# shimboard_revC_V5.net
KiCad netlist of a schematic drawn in EAGLE
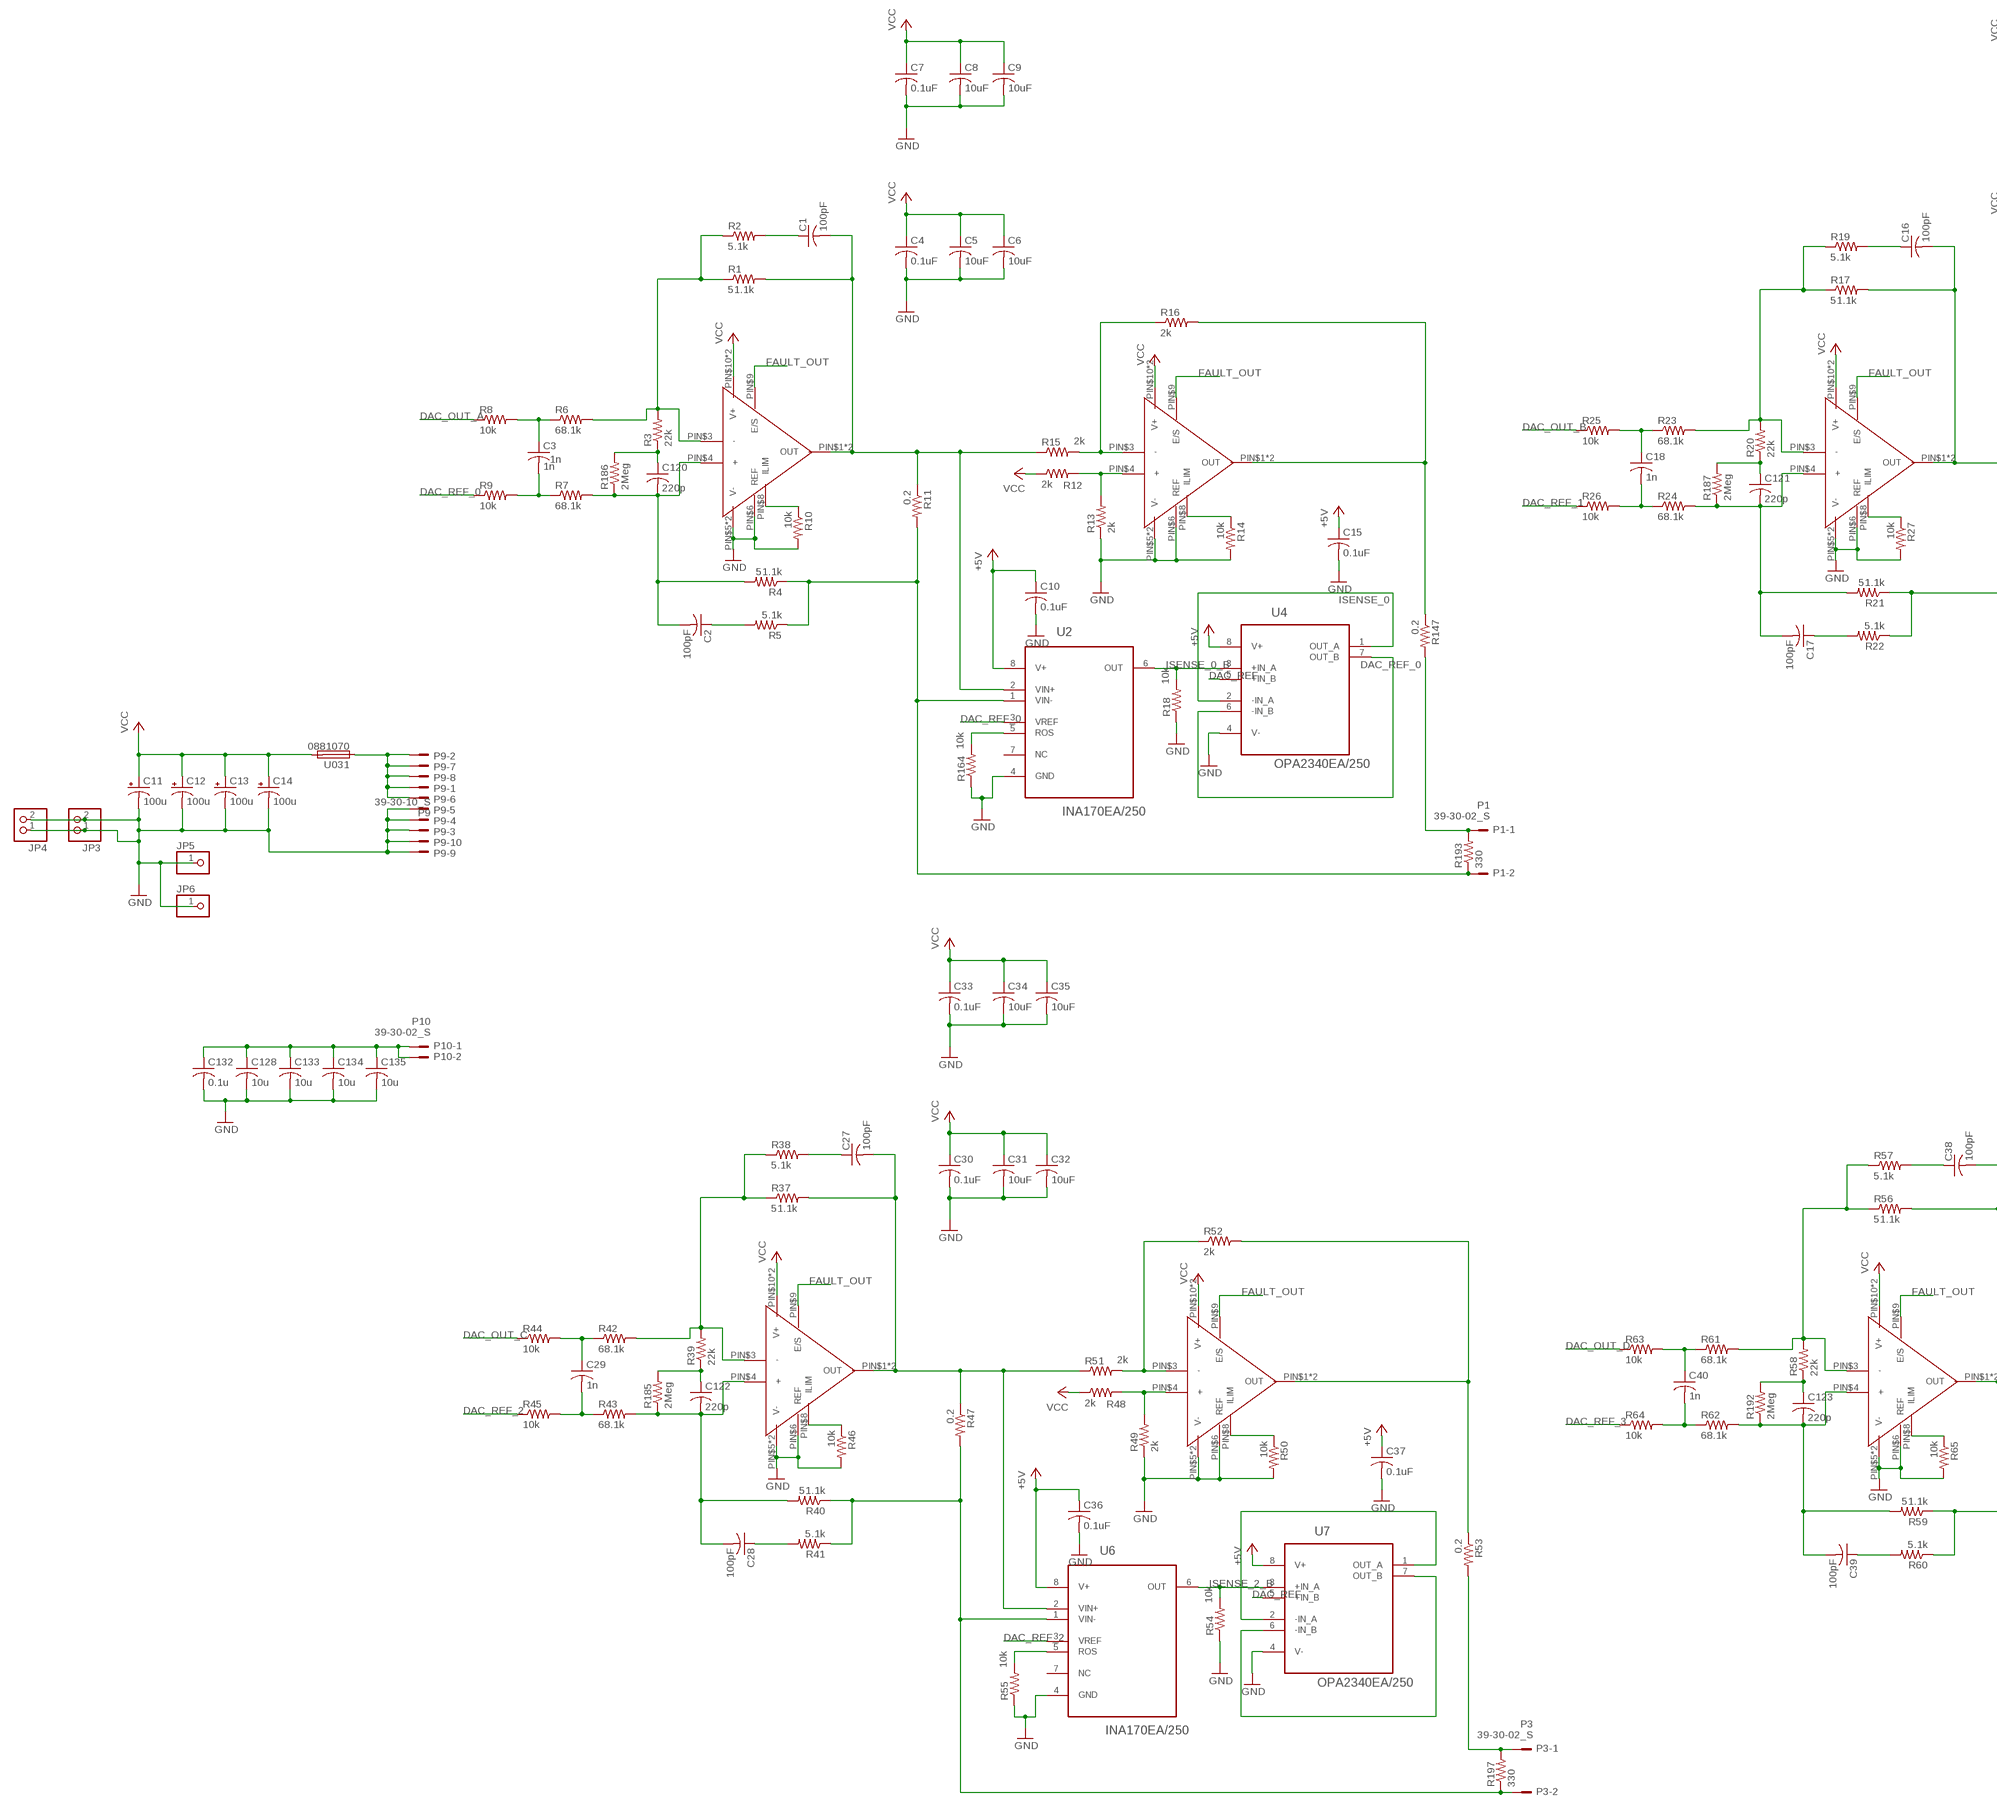
[diagram p0: schematic, sheet 1, part 1 of 3]
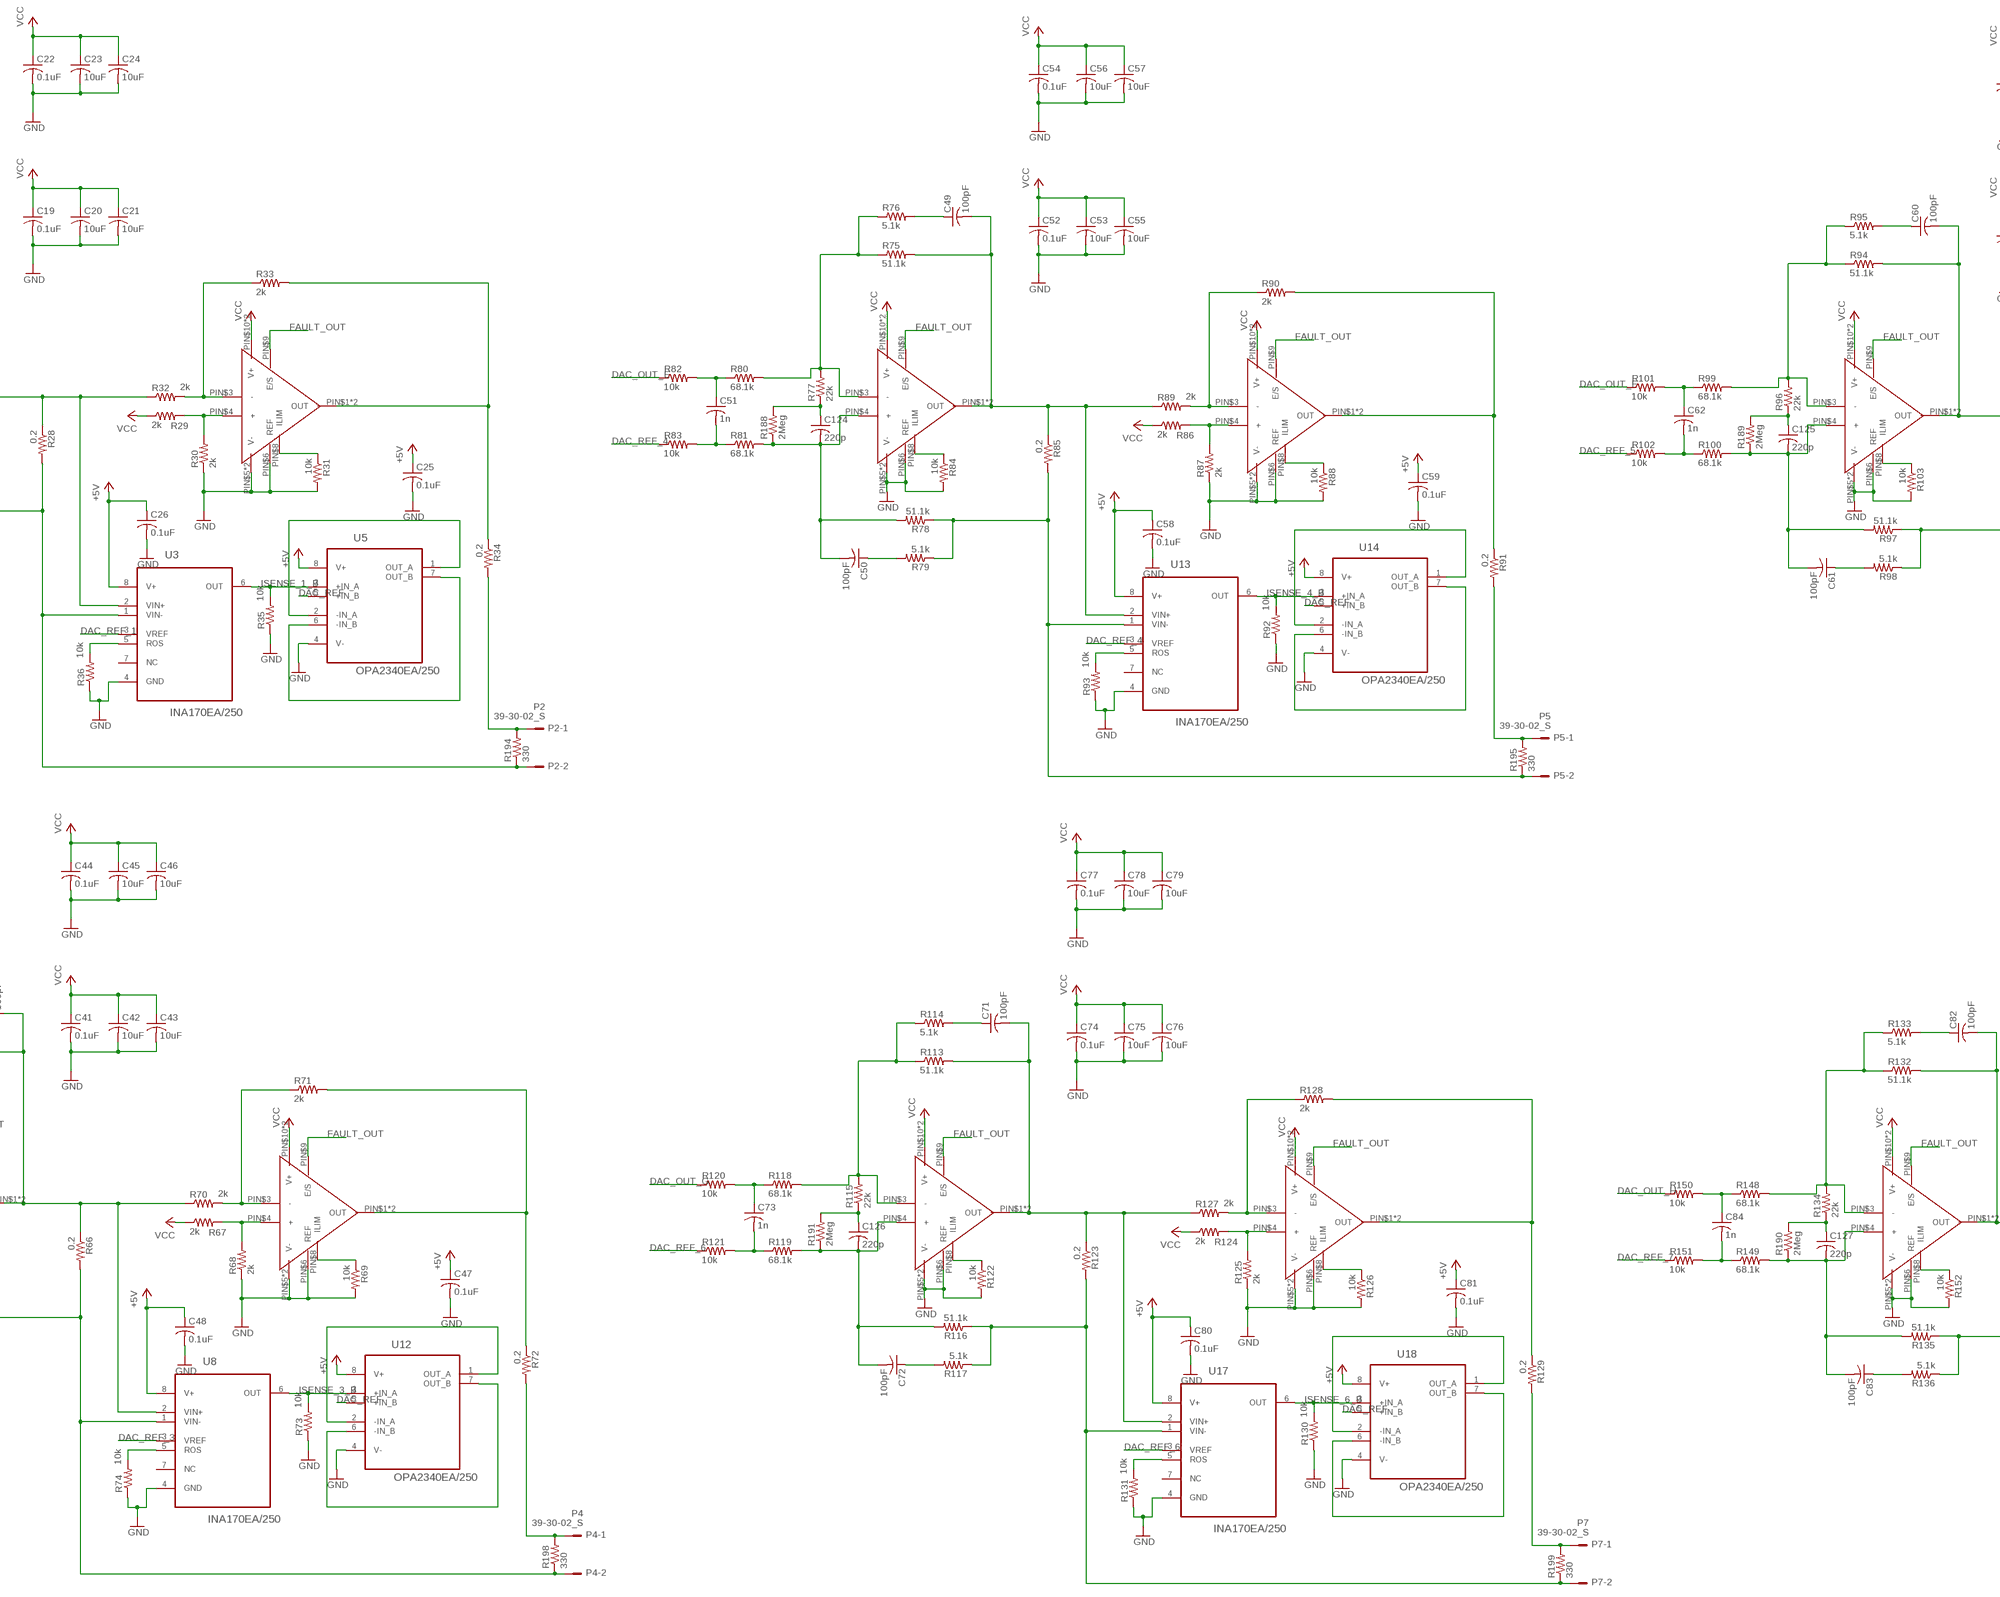
[diagram p1: schematic, sheet 1, part 2 of 3]
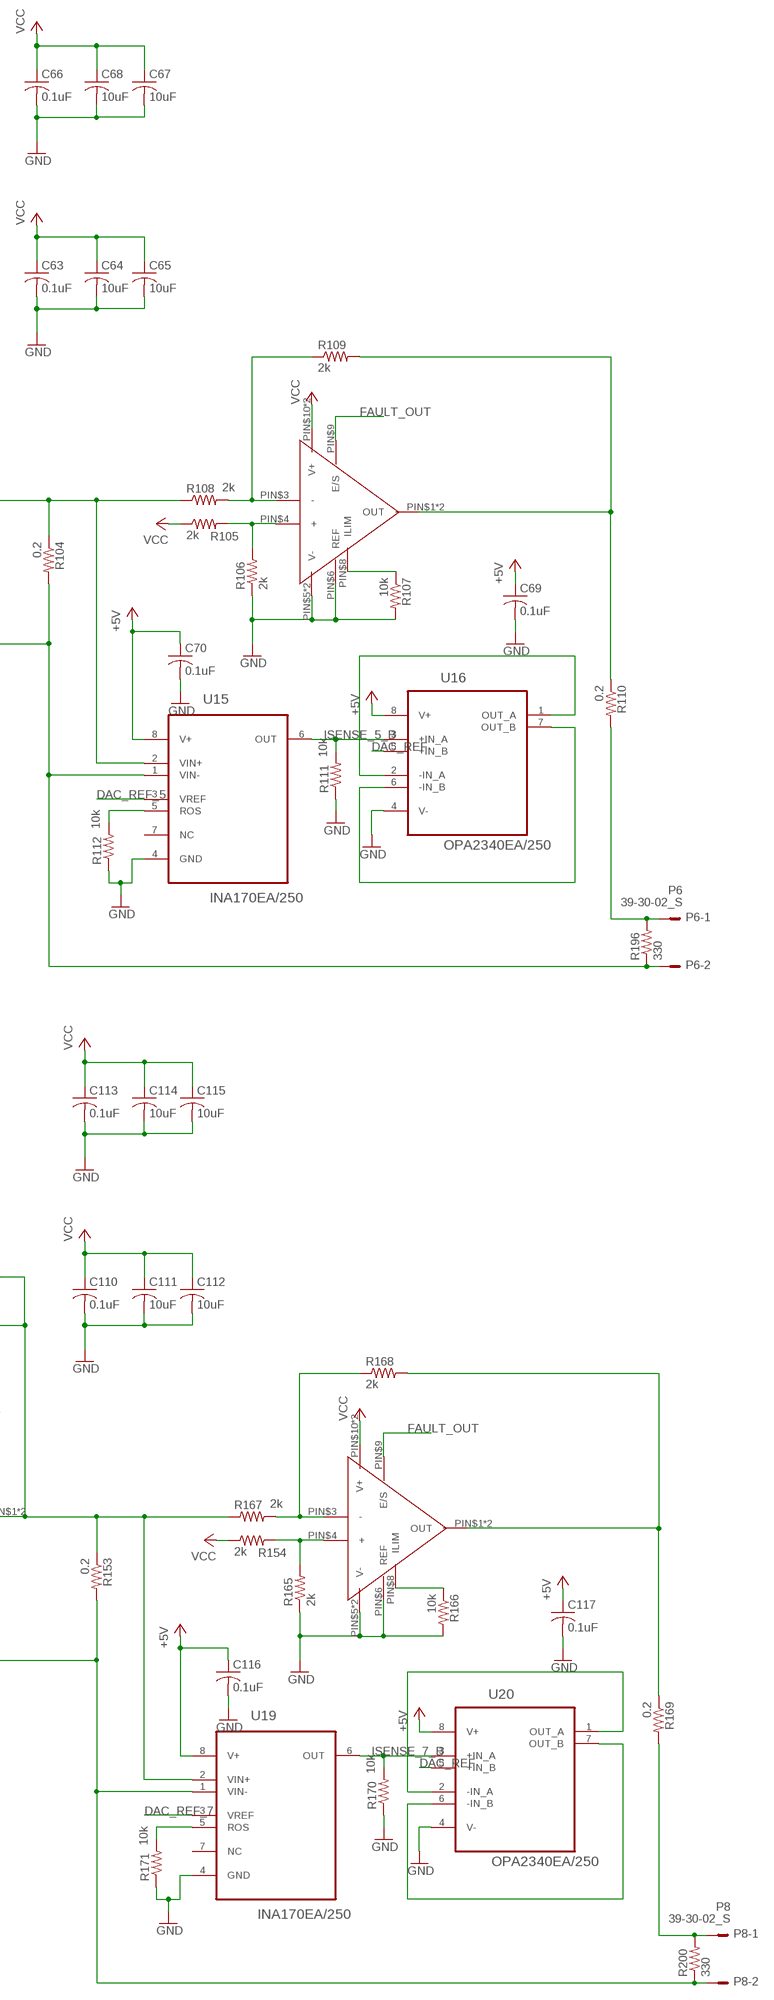
[diagram p2: schematic, sheet 1, part 3 of 3]
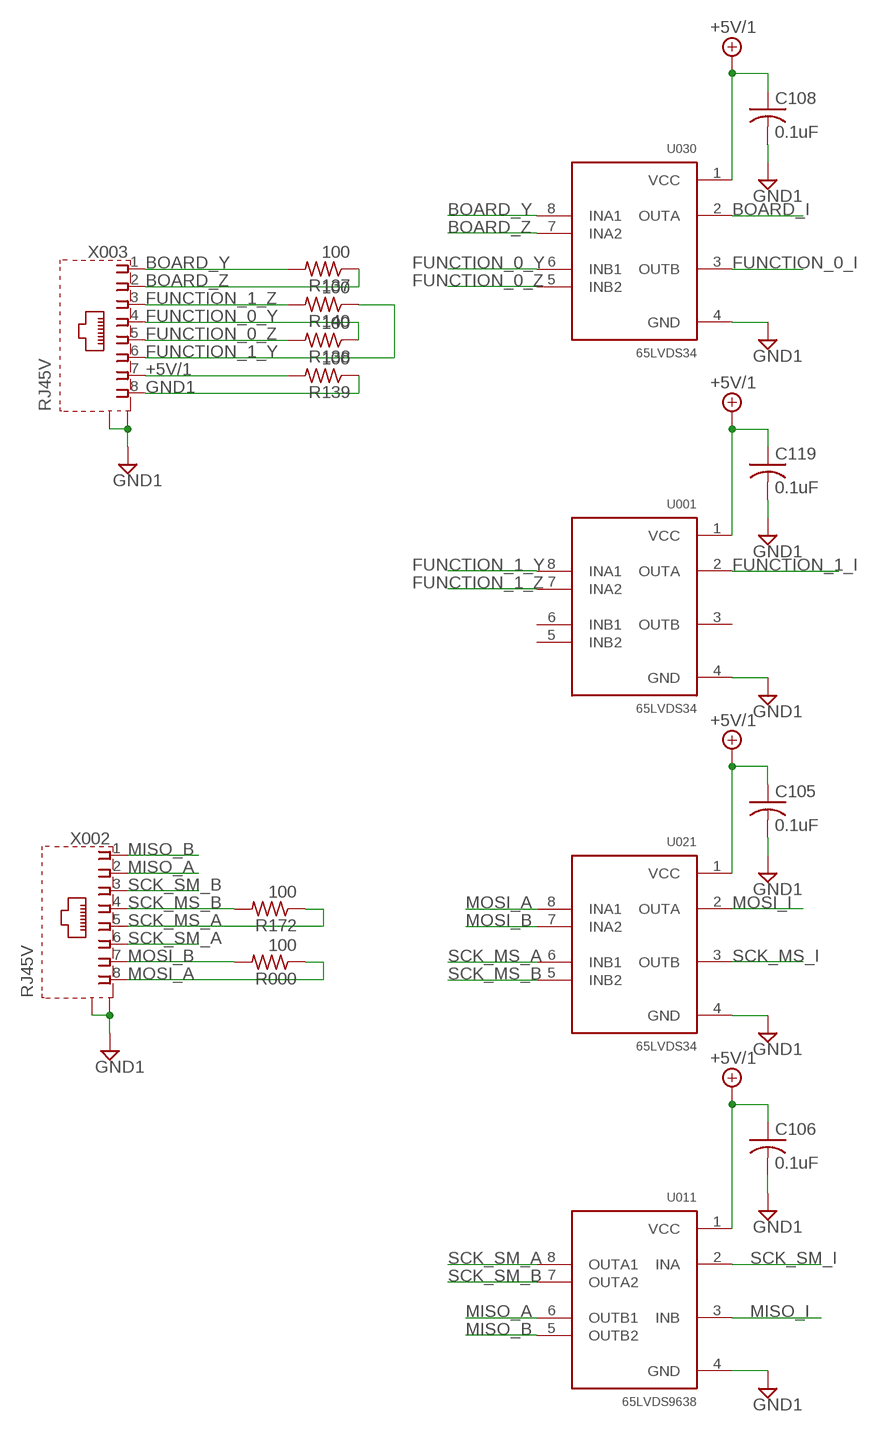
[diagram p3: schematic, sheet 2, part 1 of 2]
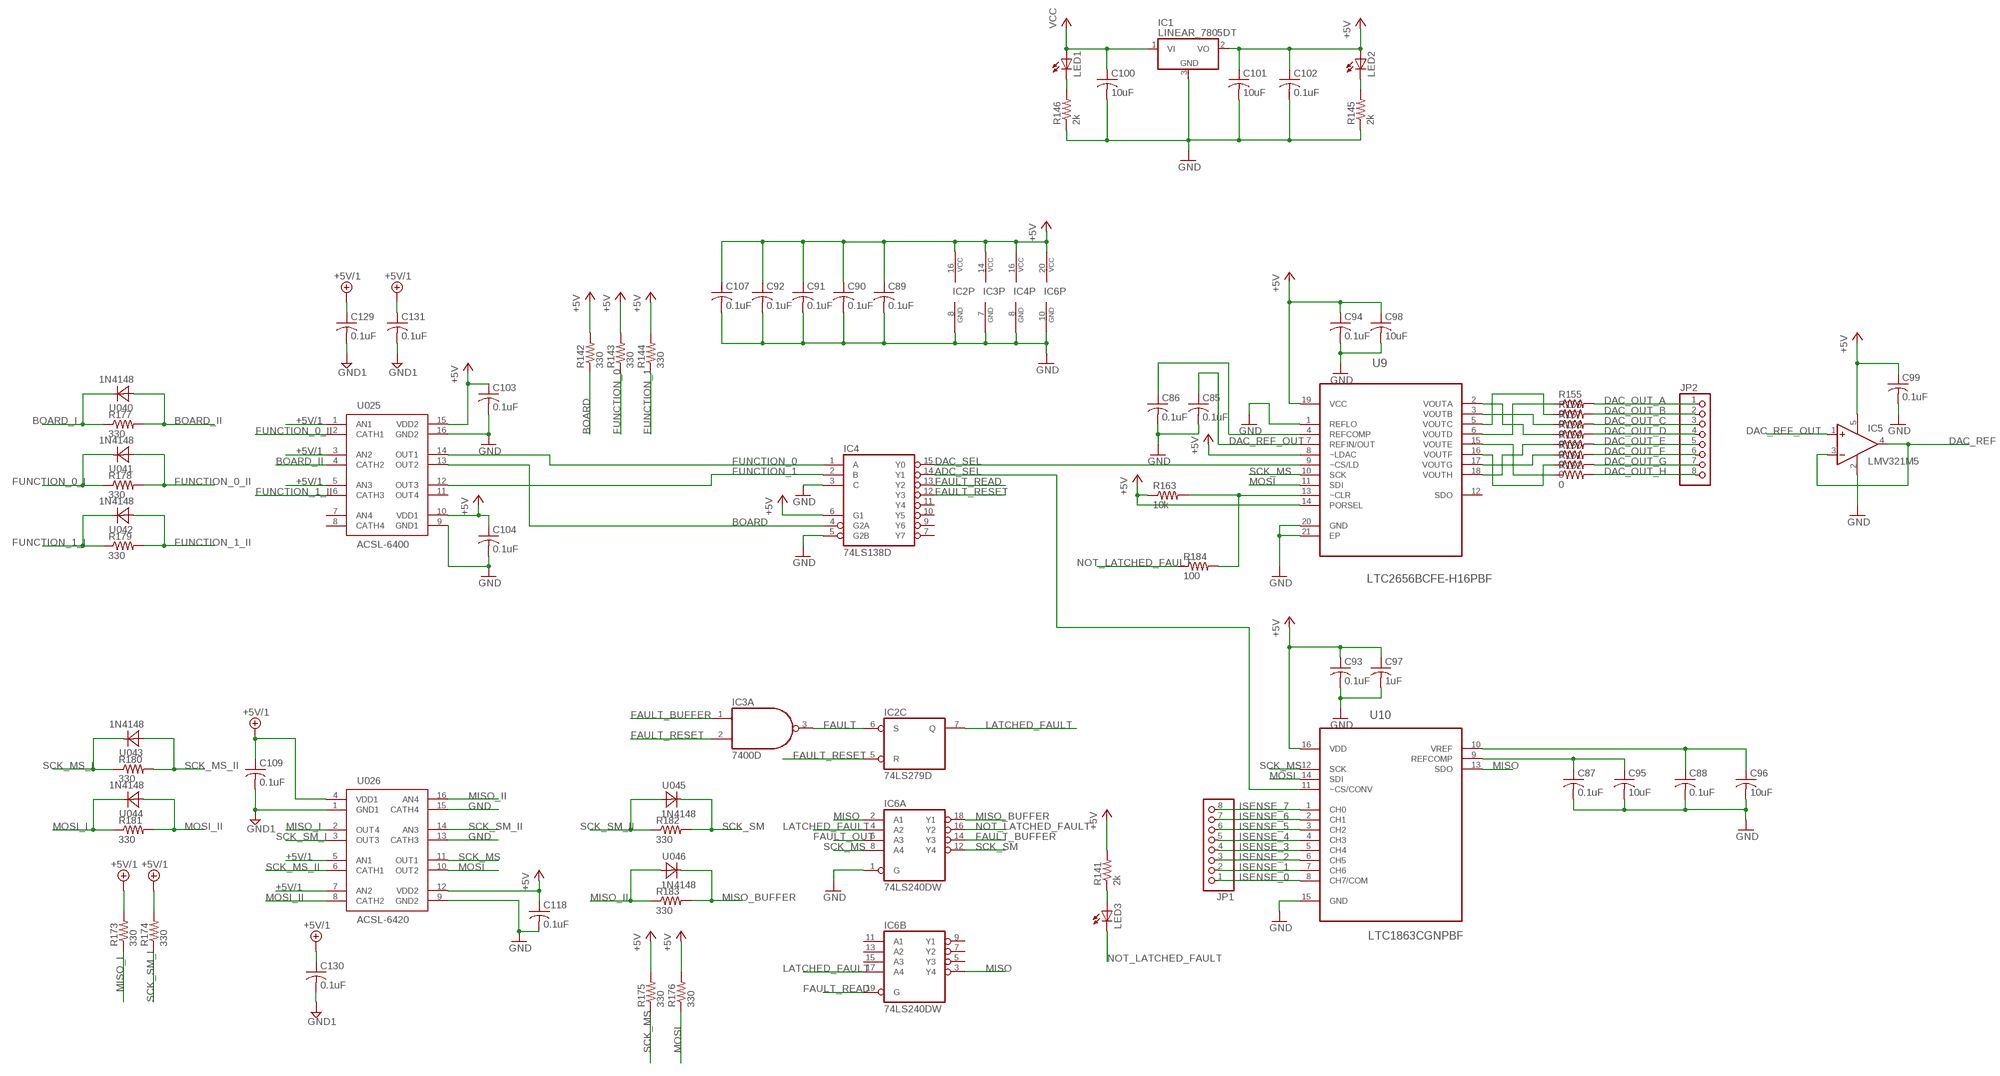
[diagram p4: schematic, sheet 2, part 2 of 2]

(export (version "E")
  (design (tool "Eeschema 10.0.6"))
  (components
    (comp (ref "C1")
      (value "100pF")
      (footprint "eagle-import:C0805")
      (libsource (lib "eagle-import") (part "C-USC0805"))
    )
    (comp (ref "C2")
      (value "100pF")
      (footprint "eagle-import:C0805")
      (libsource (lib "eagle-import") (part "C-USC0805"))
    )
    (comp (ref "C3")
      (value "1n")
      (footprint "eagle-import:C0805")
      (fields (field (name "SPICEPREFIX") "C") (field (name "SPICEPREFIX_1") "1n"))
      (libsource (lib "eagle-import") (part "C-USC0805"))
    )
    (comp (ref "C4")
      (value "0.1uF")
      (footprint "eagle-import:C0805")
      (libsource (lib "eagle-import") (part "C-USC0805"))
    )
    (comp (ref "C5")
      (value "10uF")
      (footprint "eagle-import:C1206")
      (libsource (lib "eagle-import") (part "C-USC1206"))
    )
    (comp (ref "C6")
      (value "10uF")
      (footprint "eagle-import:C1206")
      (libsource (lib "eagle-import") (part "C-USC1206"))
    )
    (comp (ref "C7")
      (value "0.1uF")
      (footprint "eagle-import:C0805")
      (libsource (lib "eagle-import") (part "C-USC0805"))
    )
    (comp (ref "C8")
      (value "10uF")
      (footprint "eagle-import:C1206")
      (libsource (lib "eagle-import") (part "C-USC1206"))
    )
    (comp (ref "C9")
      (value "10uF")
      (footprint "eagle-import:C1206")
      (libsource (lib "eagle-import") (part "C-USC1206"))
    )
    (comp (ref "C10")
      (value "0.1uF")
      (footprint "eagle-import:C0805")
      (libsource (lib "eagle-import") (part "C-USC0805"))
    )
    (comp (ref "C11")
      (value "100u")
      (footprint "eagle-import:D_7343-31W")
      (libsource (lib "eagle-import") (part "CPOL-USD/7343-31W"))
    )
    (comp (ref "C12")
      (value "100u")
      (footprint "eagle-import:D_7343-31W")
      (libsource (lib "eagle-import") (part "CPOL-USD/7343-31W"))
    )
    (comp (ref "C13")
      (value "100u")
      (footprint "eagle-import:D_7343-31W")
      (libsource (lib "eagle-import") (part "CPOL-USD/7343-31W"))
    )
    (comp (ref "C14")
      (value "100u")
      (footprint "eagle-import:D_7343-31W")
      (libsource (lib "eagle-import") (part "CPOL-USD/7343-31W"))
    )
    (comp (ref "C15")
      (value "0.1uF")
      (footprint "eagle-import:C0805")
      (libsource (lib "eagle-import") (part "C-USC0805"))
    )
    (comp (ref "C16")
      (value "100pF")
      (footprint "eagle-import:C0805")
      (libsource (lib "eagle-import") (part "C-USC0805"))
    )
    (comp (ref "C17")
      (value "100pF")
      (footprint "eagle-import:C0805")
      (libsource (lib "eagle-import") (part "C-USC0805"))
    )
    (comp (ref "C18")
      (value "1n")
      (footprint "eagle-import:C0805")
      (libsource (lib "eagle-import") (part "C-USC0805"))
    )
    (comp (ref "C19")
      (value "0.1uF")
      (footprint "eagle-import:C0805")
      (libsource (lib "eagle-import") (part "C-USC0805"))
    )
    (comp (ref "C20")
      (value "10uF")
      (footprint "eagle-import:C1206")
      (libsource (lib "eagle-import") (part "C-USC1206"))
    )
    (comp (ref "C21")
      (value "10uF")
      (footprint "eagle-import:C1206")
      (libsource (lib "eagle-import") (part "C-USC1206"))
    )
    (comp (ref "C22")
      (value "0.1uF")
      (footprint "eagle-import:C0805")
      (libsource (lib "eagle-import") (part "C-USC0805"))
    )
    (comp (ref "C23")
      (value "10uF")
      (footprint "eagle-import:C1206")
      (libsource (lib "eagle-import") (part "C-USC1206"))
    )
    (comp (ref "C24")
      (value "10uF")
      (footprint "eagle-import:C1206")
      (libsource (lib "eagle-import") (part "C-USC1206"))
    )
    (comp (ref "C25")
      (value "0.1uF")
      (footprint "eagle-import:C0805")
      (libsource (lib "eagle-import") (part "C-USC0805"))
    )
    (comp (ref "C26")
      (value "0.1uF")
      (footprint "eagle-import:C0805")
      (libsource (lib "eagle-import") (part "C-USC0805"))
    )
    (comp (ref "C27")
      (value "100pF")
      (footprint "eagle-import:C0805")
      (libsource (lib "eagle-import") (part "C-USC0805"))
    )
    (comp (ref "C28")
      (value "100pF")
      (footprint "eagle-import:C0805")
      (libsource (lib "eagle-import") (part "C-USC0805"))
    )
    (comp (ref "C29")
      (value "1n")
      (footprint "eagle-import:C0805")
      (libsource (lib "eagle-import") (part "C-USC0805"))
    )
    (comp (ref "C30")
      (value "0.1uF")
      (footprint "eagle-import:C0805")
      (libsource (lib "eagle-import") (part "C-USC0805"))
    )
    (comp (ref "C31")
      (value "10uF")
      (footprint "eagle-import:C1206")
      (libsource (lib "eagle-import") (part "C-USC1206"))
    )
    (comp (ref "C32")
      (value "10uF")
      (footprint "eagle-import:C1206")
      (libsource (lib "eagle-import") (part "C-USC1206"))
    )
    (comp (ref "C33")
      (value "0.1uF")
      (footprint "eagle-import:C0805")
      (libsource (lib "eagle-import") (part "C-USC0805"))
    )
    (comp (ref "C34")
      (value "10uF")
      (footprint "eagle-import:C1206")
      (libsource (lib "eagle-import") (part "C-USC1206"))
    )
    (comp (ref "C35")
      (value "10uF")
      (footprint "eagle-import:C1206")
      (libsource (lib "eagle-import") (part "C-USC1206"))
    )
    (comp (ref "C36")
      (value "0.1uF")
      (footprint "eagle-import:C0805")
      (libsource (lib "eagle-import") (part "C-USC0805"))
    )
    (comp (ref "C37")
      (value "0.1uF")
      (footprint "eagle-import:C0805")
      (libsource (lib "eagle-import") (part "C-USC0805"))
    )
    (comp (ref "C38")
      (value "100pF")
      (footprint "eagle-import:C0805")
      (libsource (lib "eagle-import") (part "C-USC0805"))
    )
    (comp (ref "C39")
      (value "100pF")
      (footprint "eagle-import:C0805")
      (libsource (lib "eagle-import") (part "C-USC0805"))
    )
    (comp (ref "C40")
      (value "1n")
      (footprint "eagle-import:C0805")
      (libsource (lib "eagle-import") (part "C-USC0805"))
    )
    (comp (ref "C41")
      (value "0.1uF")
      (footprint "eagle-import:C0805")
      (libsource (lib "eagle-import") (part "C-USC0805"))
    )
    (comp (ref "C42")
      (value "10uF")
      (footprint "eagle-import:C1206")
      (libsource (lib "eagle-import") (part "C-USC1206"))
    )
    (comp (ref "C43")
      (value "10uF")
      (footprint "eagle-import:C1206")
      (libsource (lib "eagle-import") (part "C-USC1206"))
    )
    (comp (ref "C44")
      (value "0.1uF")
      (footprint "eagle-import:C0805")
      (libsource (lib "eagle-import") (part "C-USC0805"))
    )
    (comp (ref "C45")
      (value "10uF")
      (footprint "eagle-import:C1206")
      (libsource (lib "eagle-import") (part "C-USC1206"))
    )
    (comp (ref "C46")
      (value "10uF")
      (footprint "eagle-import:C1206")
      (libsource (lib "eagle-import") (part "C-USC1206"))
    )
    (comp (ref "C47")
      (value "0.1uF")
      (footprint "eagle-import:C0805")
      (libsource (lib "eagle-import") (part "C-USC0805"))
    )
    (comp (ref "C48")
      (value "0.1uF")
      (footprint "eagle-import:C0805")
      (libsource (lib "eagle-import") (part "C-USC0805"))
    )
    (comp (ref "C49")
      (value "100pF")
      (footprint "eagle-import:C0805")
      (libsource (lib "eagle-import") (part "C-USC0805"))
    )
    (comp (ref "C50")
      (value "100pF")
      (footprint "eagle-import:C0805")
      (libsource (lib "eagle-import") (part "C-USC0805"))
    )
    (comp (ref "C51")
      (value "1n")
      (footprint "eagle-import:C0805")
      (libsource (lib "eagle-import") (part "C-USC0805"))
    )
    (comp (ref "C52")
      (value "0.1uF")
      (footprint "eagle-import:C0805")
      (libsource (lib "eagle-import") (part "C-USC0805"))
    )
    (comp (ref "C53")
      (value "10uF")
      (footprint "eagle-import:C1206")
      (libsource (lib "eagle-import") (part "C-USC1206"))
    )
    (comp (ref "C54")
      (value "0.1uF")
      (footprint "eagle-import:C0805")
      (libsource (lib "eagle-import") (part "C-USC0805"))
    )
    (comp (ref "C55")
      (value "10uF")
      (footprint "eagle-import:C1206")
      (libsource (lib "eagle-import") (part "C-USC1206"))
    )
    (comp (ref "C56")
      (value "10uF")
      (footprint "eagle-import:C1206")
      (libsource (lib "eagle-import") (part "C-USC1206"))
    )
    (comp (ref "C57")
      (value "10uF")
      (footprint "eagle-import:C1206")
      (libsource (lib "eagle-import") (part "C-USC1206"))
    )
    (comp (ref "C58")
      (value "0.1uF")
      (footprint "eagle-import:C0805")
      (libsource (lib "eagle-import") (part "C-USC0805"))
    )
    (comp (ref "C59")
      (value "0.1uF")
      (footprint "eagle-import:C0805")
      (libsource (lib "eagle-import") (part "C-USC0805"))
    )
    (comp (ref "C60")
      (value "100pF")
      (footprint "eagle-import:C0805")
      (libsource (lib "eagle-import") (part "C-USC0805"))
    )
    (comp (ref "C61")
      (value "100pF")
      (footprint "eagle-import:C0805")
      (libsource (lib "eagle-import") (part "C-USC0805"))
    )
    (comp (ref "C62")
      (value "1n")
      (footprint "eagle-import:C0805")
      (libsource (lib "eagle-import") (part "C-USC0805"))
    )
    (comp (ref "C63")
      (value "0.1uF")
      (footprint "eagle-import:C0805")
      (libsource (lib "eagle-import") (part "C-USC0805"))
    )
    (comp (ref "C64")
      (value "10uF")
      (footprint "eagle-import:C1206")
      (libsource (lib "eagle-import") (part "C-USC1206"))
    )
    (comp (ref "C65")
      (value "10uF")
      (footprint "eagle-import:C1206")
      (libsource (lib "eagle-import") (part "C-USC1206"))
    )
    (comp (ref "C66")
      (value "0.1uF")
      (footprint "eagle-import:C0805")
      (libsource (lib "eagle-import") (part "C-USC0805"))
    )
    (comp (ref "C67")
      (value "10uF")
      (footprint "eagle-import:C1206")
      (libsource (lib "eagle-import") (part "C-USC1206"))
    )
    (comp (ref "C68")
      (value "10uF")
      (footprint "eagle-import:C1206")
      (libsource (lib "eagle-import") (part "C-USC1206"))
    )
    (comp (ref "C69")
      (value "0.1uF")
      (footprint "eagle-import:C0805")
      (libsource (lib "eagle-import") (part "C-USC0805"))
    )
    (comp (ref "C70")
      (value "0.1uF")
      (footprint "eagle-import:C0805")
      (libsource (lib "eagle-import") (part "C-USC0805"))
    )
    (comp (ref "C71")
      (value "100pF")
      (footprint "eagle-import:C0805")
      (libsource (lib "eagle-import") (part "C-USC0805"))
    )
    (comp (ref "C72")
      (value "100pF")
      (footprint "eagle-import:C0805")
      (libsource (lib "eagle-import") (part "C-USC0805"))
    )
    (comp (ref "C73")
      (value "1n")
      (footprint "eagle-import:C0805")
      (libsource (lib "eagle-import") (part "C-USC0805"))
    )
    (comp (ref "C74")
      (value "0.1uF")
      (footprint "eagle-import:C0805")
      (libsource (lib "eagle-import") (part "C-USC0805"))
    )
    (comp (ref "C75")
      (value "10uF")
      (footprint "eagle-import:C1206")
      (libsource (lib "eagle-import") (part "C-USC1206"))
    )
    (comp (ref "C76")
      (value "10uF")
      (footprint "eagle-import:C1206")
      (libsource (lib "eagle-import") (part "C-USC1206"))
    )
    (comp (ref "C77")
      (value "0.1uF")
      (footprint "eagle-import:C0805")
      (libsource (lib "eagle-import") (part "C-USC0805"))
    )
    (comp (ref "C78")
      (value "10uF")
      (footprint "eagle-import:C1206")
      (libsource (lib "eagle-import") (part "C-USC1206"))
    )
    (comp (ref "C79")
      (value "10uF")
      (footprint "eagle-import:C1206")
      (libsource (lib "eagle-import") (part "C-USC1206"))
    )
    (comp (ref "C80")
      (value "0.1uF")
      (footprint "eagle-import:C0805")
      (libsource (lib "eagle-import") (part "C-USC0805"))
    )
    (comp (ref "C81")
      (value "0.1uF")
      (footprint "eagle-import:C0805")
      (libsource (lib "eagle-import") (part "C-USC0805"))
    )
    (comp (ref "C82")
      (value "100pF")
      (footprint "eagle-import:C0805")
      (libsource (lib "eagle-import") (part "C-USC0805"))
    )
    (comp (ref "C83")
      (value "100pF")
      (footprint "eagle-import:C0805")
      (libsource (lib "eagle-import") (part "C-USC0805"))
    )
    (comp (ref "C84")
      (value "1n")
      (footprint "eagle-import:C0805")
      (libsource (lib "eagle-import") (part "C-USC0805"))
    )
    (comp (ref "C110")
      (value "0.1uF")
      (footprint "eagle-import:C0805")
      (libsource (lib "eagle-import") (part "C-USC0805"))
    )
    (comp (ref "C111")
      (value "10uF")
      (footprint "eagle-import:C1206")
      (libsource (lib "eagle-import") (part "C-USC1206"))
    )
    (comp (ref "C112")
      (value "10uF")
      (footprint "eagle-import:C1206")
      (libsource (lib "eagle-import") (part "C-USC1206"))
    )
    (comp (ref "C113")
      (value "0.1uF")
      (footprint "eagle-import:C0805")
      (libsource (lib "eagle-import") (part "C-USC0805"))
    )
    (comp (ref "C114")
      (value "10uF")
      (footprint "eagle-import:C1206")
      (libsource (lib "eagle-import") (part "C-USC1206"))
    )
    (comp (ref "C115")
      (value "10uF")
      (footprint "eagle-import:C1206")
      (libsource (lib "eagle-import") (part "C-USC1206"))
    )
    (comp (ref "C116")
      (value "0.1uF")
      (footprint "eagle-import:C0805")
      (libsource (lib "eagle-import") (part "C-USC0805"))
    )
    (comp (ref "C117")
      (value "0.1uF")
      (footprint "eagle-import:C0805")
      (libsource (lib "eagle-import") (part "C-USC0805"))
    )
    (comp (ref "C120")
      (value "220p")
      (footprint "eagle-import:C0805")
      (libsource (lib "eagle-import") (part "C-USC0805"))
    )
    (comp (ref "C121")
      (value "220p")
      (footprint "eagle-import:C0805")
      (libsource (lib "eagle-import") (part "C-USC0805"))
    )
    (comp (ref "C122")
      (value "220p")
      (footprint "eagle-import:C0805")
      (libsource (lib "eagle-import") (part "C-USC0805"))
    )
    (comp (ref "C123")
      (value "220p")
      (footprint "eagle-import:C0805")
      (libsource (lib "eagle-import") (part "C-USC0805"))
    )
    (comp (ref "C124")
      (value "220p")
      (footprint "eagle-import:C0805")
      (libsource (lib "eagle-import") (part "C-USC0805"))
    )
    (comp (ref "C125")
      (value "220p")
      (footprint "eagle-import:C0805")
      (libsource (lib "eagle-import") (part "C-USC0805"))
    )
    (comp (ref "C126")
      (value "220p")
      (footprint "eagle-import:C0805")
      (libsource (lib "eagle-import") (part "C-USC0805"))
    )
    (comp (ref "C127")
      (value "220p")
      (footprint "eagle-import:C0805")
      (libsource (lib "eagle-import") (part "C-USC0805"))
    )
    (comp (ref "C128")
      (value "10u")
      (footprint "eagle-import:C1206")
      (libsource (lib "eagle-import") (part "C-USC1206"))
    )
    (comp (ref "C132")
      (value "0.1u")
      (footprint "eagle-import:C0805")
      (libsource (lib "eagle-import") (part "C-USC0805"))
    )
    (comp (ref "C133")
      (value "10u")
      (footprint "eagle-import:C1206")
      (libsource (lib "eagle-import") (part "C-USC1206"))
    )
    (comp (ref "C134")
      (value "10u")
      (footprint "eagle-import:C1206")
      (libsource (lib "eagle-import") (part "C-USC1206"))
    )
    (comp (ref "C135")
      (value "10u")
      (footprint "eagle-import:C1206")
      (libsource (lib "eagle-import") (part "C-USC1206"))
    )
    (comp (ref "JP3")
      (value "PINHD-1X2")
      (footprint "eagle-import:1X02")
      (libsource (lib "eagle-import") (part "PINHD-1X2"))
    )
    (comp (ref "JP4")
      (value "PINHD-1X2")
      (footprint "eagle-import:1X02")
      (libsource (lib "eagle-import") (part "PINHD-1X2"))
    )
    (comp (ref "JP5")
      (value "PINHD-1X1")
      (footprint "eagle-import:1X01")
      (libsource (lib "eagle-import") (part "PINHD-1X1"))
    )
    (comp (ref "JP6")
      (value "PINHD-1X1")
      (footprint "eagle-import:1X01")
      (libsource (lib "eagle-import") (part "PINHD-1X1"))
    )
    (comp (ref "P1")
      (value "39-30-02_S")
      (footprint "eagle-import:39-30-_02_")
      (libsource (lib "eagle-import") (part "39-30-?02?_S"))
    )
    (comp (ref "P2")
      (value "39-30-02_S")
      (footprint "eagle-import:39-30-_02_")
      (libsource (lib "eagle-import") (part "39-30-?02?_S"))
    )
    (comp (ref "P3")
      (value "39-30-02_S")
      (footprint "eagle-import:39-30-_02_")
      (libsource (lib "eagle-import") (part "39-30-?02?_S"))
    )
    (comp (ref "P4")
      (value "39-30-02_S")
      (footprint "eagle-import:39-30-_02_")
      (libsource (lib "eagle-import") (part "39-30-?02?_S"))
    )
    (comp (ref "P5")
      (value "39-30-02_S")
      (footprint "eagle-import:39-30-_02_")
      (libsource (lib "eagle-import") (part "39-30-?02?_S"))
    )
    (comp (ref "P6")
      (value "39-30-02_S")
      (footprint "eagle-import:39-30-_02_")
      (libsource (lib "eagle-import") (part "39-30-?02?_S"))
    )
    (comp (ref "P7")
      (value "39-30-02_S")
      (footprint "eagle-import:39-30-_02_")
      (libsource (lib "eagle-import") (part "39-30-?02?_S"))
    )
    (comp (ref "P8")
      (value "39-30-02_S")
      (footprint "eagle-import:39-30-_02_")
      (libsource (lib "eagle-import") (part "39-30-?02?_S"))
    )
    (comp (ref "P9")
      (value "39-30-10_S")
      (footprint "eagle-import:39-30-_10_")
      (libsource (lib "eagle-import") (part "39-30-?10?_S"))
    )
    (comp (ref "P10")
      (value "39-30-02_S")
      (footprint "eagle-import:39-30-_02_")
      (libsource (lib "eagle-import") (part "39-30-?02?_S"))
    )
    (comp (ref "R1")
      (value "51.1k")
      (footprint "eagle-import:R0805")
      (libsource (lib "eagle-import") (part "R-US_R0805"))
    )
    (comp (ref "R2")
      (value "5.1k")
      (footprint "eagle-import:R0805")
      (libsource (lib "eagle-import") (part "R-US_R0805"))
    )
    (comp (ref "R3")
      (value "22k")
      (footprint "eagle-import:R0805")
      (libsource (lib "eagle-import") (part "R-US_R0805"))
    )
    (comp (ref "R4")
      (value "51.1k")
      (footprint "eagle-import:R0805")
      (libsource (lib "eagle-import") (part "R-US_R0805"))
    )
    (comp (ref "R5")
      (value "5.1k")
      (footprint "eagle-import:R0805")
      (libsource (lib "eagle-import") (part "R-US_R0805"))
    )
    (comp (ref "R6")
      (value "68.1k")
      (footprint "eagle-import:R0805")
      (libsource (lib "eagle-import") (part "R-US_R0805"))
    )
    (comp (ref "R7")
      (value "68.1k")
      (footprint "eagle-import:R0805")
      (libsource (lib "eagle-import") (part "R-US_R0805"))
    )
    (comp (ref "R8")
      (value "10k")
      (footprint "eagle-import:R0805")
      (libsource (lib "eagle-import") (part "R-US_R0805"))
    )
    (comp (ref "R9")
      (value "10k")
      (footprint "eagle-import:R0805")
      (libsource (lib "eagle-import") (part "R-US_R0805"))
    )
    (comp (ref "R10")
      (value "10k")
      (footprint "eagle-import:R0805")
      (libsource (lib "eagle-import") (part "R-US_R0805"))
    )
    (comp (ref "R11")
      (value "0.2")
      (footprint "eagle-import:R4527")
      (libsource (lib "eagle-import") (part "R-US_R4527"))
    )
    (comp (ref "R12")
      (value "2k")
      (footprint "eagle-import:M0805")
      (libsource (lib "eagle-import") (part "R-US_M0805"))
    )
    (comp (ref "R13")
      (value "2k")
      (footprint "eagle-import:R0805")
      (libsource (lib "eagle-import") (part "R-US_R0805"))
    )
    (comp (ref "R14")
      (value "10k")
      (footprint "eagle-import:R0805")
      (libsource (lib "eagle-import") (part "R-US_R0805"))
    )
    (comp (ref "R15")
      (value "2k")
      (footprint "eagle-import:R0805")
      (libsource (lib "eagle-import") (part "R-US_R0805"))
    )
    (comp (ref "R16")
      (value "2k")
      (footprint "eagle-import:R0805")
      (libsource (lib "eagle-import") (part "R-US_R0805"))
    )
    (comp (ref "R17")
      (value "51.1k")
      (footprint "eagle-import:R0805")
      (libsource (lib "eagle-import") (part "R-US_R0805"))
    )
    (comp (ref "R18")
      (value "10k")
      (footprint "eagle-import:R0805")
      (libsource (lib "eagle-import") (part "R-US_R0805"))
    )
    (comp (ref "R19")
      (value "5.1k")
      (footprint "eagle-import:R0805")
      (libsource (lib "eagle-import") (part "R-US_R0805"))
    )
    (comp (ref "R20")
      (value "22k")
      (footprint "eagle-import:R0805")
      (libsource (lib "eagle-import") (part "R-US_R0805"))
    )
    (comp (ref "R21")
      (value "51.1k")
      (footprint "eagle-import:R0805")
      (libsource (lib "eagle-import") (part "R-US_R0805"))
    )
    (comp (ref "R22")
      (value "5.1k")
      (footprint "eagle-import:R0805")
      (libsource (lib "eagle-import") (part "R-US_R0805"))
    )
    (comp (ref "R23")
      (value "68.1k")
      (footprint "eagle-import:R0805")
      (libsource (lib "eagle-import") (part "R-US_R0805"))
    )
    (comp (ref "R24")
      (value "68.1k")
      (footprint "eagle-import:R0805")
      (libsource (lib "eagle-import") (part "R-US_R0805"))
    )
    (comp (ref "R25")
      (value "10k")
      (footprint "eagle-import:R0805")
      (libsource (lib "eagle-import") (part "R-US_R0805"))
    )
    (comp (ref "R26")
      (value "10k")
      (footprint "eagle-import:R0805")
      (libsource (lib "eagle-import") (part "R-US_R0805"))
    )
    (comp (ref "R27")
      (value "10k")
      (footprint "eagle-import:R0805")
      (libsource (lib "eagle-import") (part "R-US_R0805"))
    )
    (comp (ref "R28")
      (value "0.2")
      (footprint "eagle-import:R4527")
      (libsource (lib "eagle-import") (part "R-US_R4527"))
    )
    (comp (ref "R29")
      (value "2k")
      (footprint "eagle-import:M0805")
      (libsource (lib "eagle-import") (part "R-US_M0805"))
    )
    (comp (ref "R30")
      (value "2k")
      (footprint "eagle-import:R0805")
      (libsource (lib "eagle-import") (part "R-US_R0805"))
    )
    (comp (ref "R31")
      (value "10k")
      (footprint "eagle-import:R0805")
      (libsource (lib "eagle-import") (part "R-US_R0805"))
    )
    (comp (ref "R32")
      (value "2k")
      (footprint "eagle-import:R0805")
      (libsource (lib "eagle-import") (part "R-US_R0805"))
    )
    (comp (ref "R33")
      (value "2k")
      (footprint "eagle-import:R0805")
      (libsource (lib "eagle-import") (part "R-US_R0805"))
    )
    (comp (ref "R34")
      (value "0.2")
      (footprint "eagle-import:R4527")
      (libsource (lib "eagle-import") (part "R-US_R4527"))
    )
    (comp (ref "R35")
      (value "10k")
      (footprint "eagle-import:R0805")
      (libsource (lib "eagle-import") (part "R-US_R0805"))
    )
    (comp (ref "R36")
      (value "10k")
      (footprint "eagle-import:R0805")
      (libsource (lib "eagle-import") (part "R-US_R0805"))
    )
    (comp (ref "R37")
      (value "51.1k")
      (footprint "eagle-import:R0805")
      (libsource (lib "eagle-import") (part "R-US_R0805"))
    )
    (comp (ref "R38")
      (value "5.1k")
      (footprint "eagle-import:R0805")
      (libsource (lib "eagle-import") (part "R-US_R0805"))
    )
    (comp (ref "R39")
      (value "22k")
      (footprint "eagle-import:R0805")
      (libsource (lib "eagle-import") (part "R-US_R0805"))
    )
    (comp (ref "R40")
      (value "51.1k")
      (footprint "eagle-import:R0805")
      (libsource (lib "eagle-import") (part "R-US_R0805"))
    )
    (comp (ref "R41")
      (value "5.1k")
      (footprint "eagle-import:R0805")
      (libsource (lib "eagle-import") (part "R-US_R0805"))
    )
    (comp (ref "R42")
      (value "68.1k")
      (footprint "eagle-import:R0805")
      (libsource (lib "eagle-import") (part "R-US_R0805"))
    )
    (comp (ref "R43")
      (value "68.1k")
      (footprint "eagle-import:R0805")
      (libsource (lib "eagle-import") (part "R-US_R0805"))
    )
    (comp (ref "R44")
      (value "10k")
      (footprint "eagle-import:R0805")
      (libsource (lib "eagle-import") (part "R-US_R0805"))
    )
    (comp (ref "R45")
      (value "10k")
      (footprint "eagle-import:R0805")
      (libsource (lib "eagle-import") (part "R-US_R0805"))
    )
    (comp (ref "R46")
      (value "10k")
      (footprint "eagle-import:R0805")
      (libsource (lib "eagle-import") (part "R-US_R0805"))
    )
    (comp (ref "R47")
      (value "0.2")
      (footprint "eagle-import:R4527")
      (libsource (lib "eagle-import") (part "R-US_R4527"))
    )
    (comp (ref "R48")
      (value "2k")
      (footprint "eagle-import:M0805")
      (libsource (lib "eagle-import") (part "R-US_M0805"))
    )
    (comp (ref "R49")
      (value "2k")
      (footprint "eagle-import:R0805")
      (libsource (lib "eagle-import") (part "R-US_R0805"))
    )
    (comp (ref "R50")
      (value "10k")
      (footprint "eagle-import:R0805")
      (libsource (lib "eagle-import") (part "R-US_R0805"))
    )
    (comp (ref "R51")
      (value "2k")
      (footprint "eagle-import:R0805")
      (libsource (lib "eagle-import") (part "R-US_R0805"))
    )
    (comp (ref "R52")
      (value "2k")
      (footprint "eagle-import:R0805")
      (libsource (lib "eagle-import") (part "R-US_R0805"))
    )
    (comp (ref "R53")
      (value "0.2")
      (footprint "eagle-import:R4527")
      (libsource (lib "eagle-import") (part "R-US_R4527"))
    )
    (comp (ref "R54")
      (value "10k")
      (footprint "eagle-import:R0805")
      (libsource (lib "eagle-import") (part "R-US_R0805"))
    )
    (comp (ref "R55")
      (value "10k")
      (footprint "eagle-import:R0805")
      (libsource (lib "eagle-import") (part "R-US_R0805"))
    )
    (comp (ref "R56")
      (value "51.1k")
      (footprint "eagle-import:R0805")
      (libsource (lib "eagle-import") (part "R-US_R0805"))
    )
    (comp (ref "R57")
      (value "5.1k")
      (footprint "eagle-import:R0805")
      (libsource (lib "eagle-import") (part "R-US_R0805"))
    )
    (comp (ref "R58")
      (value "22k")
      (footprint "eagle-import:R0805")
      (libsource (lib "eagle-import") (part "R-US_R0805"))
    )
    (comp (ref "R59")
      (value "51.1k")
      (footprint "eagle-import:R0805")
      (libsource (lib "eagle-import") (part "R-US_R0805"))
    )
    (comp (ref "R60")
      (value "5.1k")
      (footprint "eagle-import:R0805")
      (libsource (lib "eagle-import") (part "R-US_R0805"))
    )
    (comp (ref "R61")
      (value "68.1k")
      (footprint "eagle-import:R0805")
      (libsource (lib "eagle-import") (part "R-US_R0805"))
    )
    (comp (ref "R62")
      (value "68.1k")
      (footprint "eagle-import:R0805")
      (libsource (lib "eagle-import") (part "R-US_R0805"))
    )
    (comp (ref "R63")
      (value "10k")
      (footprint "eagle-import:R0805")
      (libsource (lib "eagle-import") (part "R-US_R0805"))
    )
    (comp (ref "R64")
      (value "10k")
      (footprint "eagle-import:R0805")
      (libsource (lib "eagle-import") (part "R-US_R0805"))
    )
    (comp (ref "R65")
      (value "10k")
      (footprint "eagle-import:R0805")
      (libsource (lib "eagle-import") (part "R-US_R0805"))
    )
    (comp (ref "R66")
      (value "0.2")
      (footprint "eagle-import:R4527")
      (libsource (lib "eagle-import") (part "R-US_R4527"))
    )
    (comp (ref "R67")
      (value "2k")
      (footprint "eagle-import:M0805")
      (libsource (lib "eagle-import") (part "R-US_M0805"))
    )
    (comp (ref "R68")
      (value "2k")
      (footprint "eagle-import:R0805")
      (libsource (lib "eagle-import") (part "R-US_R0805"))
    )
    (comp (ref "R69")
      (value "10k")
      (footprint "eagle-import:R0805")
      (libsource (lib "eagle-import") (part "R-US_R0805"))
    )
    (comp (ref "R70")
      (value "2k")
      (footprint "eagle-import:R0805")
      (libsource (lib "eagle-import") (part "R-US_R0805"))
    )
    (comp (ref "R71")
      (value "2k")
      (footprint "eagle-import:R0805")
      (libsource (lib "eagle-import") (part "R-US_R0805"))
    )
    (comp (ref "R72")
      (value "0.2")
      (footprint "eagle-import:R4527")
      (libsource (lib "eagle-import") (part "R-US_R4527"))
    )
    (comp (ref "R73")
      (value "10k")
      (footprint "eagle-import:R0805")
      (libsource (lib "eagle-import") (part "R-US_R0805"))
    )
    (comp (ref "R74")
      (value "10k")
      (footprint "eagle-import:R0805")
      (libsource (lib "eagle-import") (part "R-US_R0805"))
    )
    (comp (ref "R75")
      (value "51.1k")
      (footprint "eagle-import:R0805")
      (libsource (lib "eagle-import") (part "R-US_R0805"))
    )
    (comp (ref "R76")
      (value "5.1k")
      (footprint "eagle-import:R0805")
      (libsource (lib "eagle-import") (part "R-US_R0805"))
    )
    (comp (ref "R77")
      (value "22k")
      (footprint "eagle-import:R0805")
      (libsource (lib "eagle-import") (part "R-US_R0805"))
    )
    (comp (ref "R78")
      (value "51.1k")
      (footprint "eagle-import:R0805")
      (libsource (lib "eagle-import") (part "R-US_R0805"))
    )
    (comp (ref "R79")
      (value "5.1k")
      (footprint "eagle-import:R0805")
      (libsource (lib "eagle-import") (part "R-US_R0805"))
    )
    (comp (ref "R80")
      (value "68.1k")
      (footprint "eagle-import:R0805")
      (libsource (lib "eagle-import") (part "R-US_R0805"))
    )
    (comp (ref "R81")
      (value "68.1k")
      (footprint "eagle-import:R0805")
      (libsource (lib "eagle-import") (part "R-US_R0805"))
    )
    (comp (ref "R82")
      (value "10k")
      (footprint "eagle-import:R0805")
      (libsource (lib "eagle-import") (part "R-US_R0805"))
    )
    (comp (ref "R83")
      (value "10k")
      (footprint "eagle-import:R0805")
      (libsource (lib "eagle-import") (part "R-US_R0805"))
    )
    (comp (ref "R84")
      (value "10k")
      (footprint "eagle-import:R0805")
      (libsource (lib "eagle-import") (part "R-US_R0805"))
    )
    (comp (ref "R85")
      (value "0.2")
      (footprint "eagle-import:R4527")
      (libsource (lib "eagle-import") (part "R-US_R4527"))
    )
    (comp (ref "R86")
      (value "2k")
      (footprint "eagle-import:M0805")
      (libsource (lib "eagle-import") (part "R-US_M0805"))
    )
    (comp (ref "R87")
      (value "2k")
      (footprint "eagle-import:R0805")
      (libsource (lib "eagle-import") (part "R-US_R0805"))
    )
    (comp (ref "R88")
      (value "10k")
      (footprint "eagle-import:R0805")
      (libsource (lib "eagle-import") (part "R-US_R0805"))
    )
    (comp (ref "R89")
      (value "2k")
      (footprint "eagle-import:R0805")
      (libsource (lib "eagle-import") (part "R-US_R0805"))
    )
    (comp (ref "R90")
      (value "2k")
      (footprint "eagle-import:R0805")
      (libsource (lib "eagle-import") (part "R-US_R0805"))
    )
    (comp (ref "R91")
      (value "0.2")
      (footprint "eagle-import:R4527")
      (libsource (lib "eagle-import") (part "R-US_R4527"))
    )
    (comp (ref "R92")
      (value "10k")
      (footprint "eagle-import:R0805")
      (libsource (lib "eagle-import") (part "R-US_R0805"))
    )
    (comp (ref "R93")
      (value "10k")
      (footprint "eagle-import:R0805")
      (libsource (lib "eagle-import") (part "R-US_R0805"))
    )
    (comp (ref "R94")
      (value "51.1k")
      (footprint "eagle-import:R0805")
      (libsource (lib "eagle-import") (part "R-US_R0805"))
    )
    (comp (ref "R95")
      (value "5.1k")
      (footprint "eagle-import:R0805")
      (libsource (lib "eagle-import") (part "R-US_R0805"))
    )
    (comp (ref "R96")
      (value "22k")
      (footprint "eagle-import:R0805")
      (libsource (lib "eagle-import") (part "R-US_R0805"))
    )
    (comp (ref "R97")
      (value "51.1k")
      (footprint "eagle-import:R0805")
      (libsource (lib "eagle-import") (part "R-US_R0805"))
    )
    (comp (ref "R98")
      (value "5.1k")
      (footprint "eagle-import:R0805")
      (libsource (lib "eagle-import") (part "R-US_R0805"))
    )
    (comp (ref "R99")
      (value "68.1k")
      (footprint "eagle-import:R0805")
      (libsource (lib "eagle-import") (part "R-US_R0805"))
    )
    (comp (ref "R100")
      (value "68.1k")
      (footprint "eagle-import:R0805")
      (libsource (lib "eagle-import") (part "R-US_R0805"))
    )
    (comp (ref "R101")
      (value "10k")
      (footprint "eagle-import:R0805")
      (libsource (lib "eagle-import") (part "R-US_R0805"))
    )
    (comp (ref "R102")
      (value "10k")
      (footprint "eagle-import:R0805")
      (libsource (lib "eagle-import") (part "R-US_R0805"))
    )
    (comp (ref "R103")
      (value "10k")
      (footprint "eagle-import:R0805")
      (libsource (lib "eagle-import") (part "R-US_R0805"))
    )
    (comp (ref "R104")
      (value "0.2")
      (footprint "eagle-import:R4527")
      (libsource (lib "eagle-import") (part "R-US_R4527"))
    )
    (comp (ref "R105")
      (value "2k")
      (footprint "eagle-import:M0805")
      (libsource (lib "eagle-import") (part "R-US_M0805"))
    )
    (comp (ref "R106")
      (value "2k")
      (footprint "eagle-import:R0805")
      (libsource (lib "eagle-import") (part "R-US_R0805"))
    )
    (comp (ref "R107")
      (value "10k")
      (footprint "eagle-import:R0805")
      (libsource (lib "eagle-import") (part "R-US_R0805"))
    )
    (comp (ref "R108")
      (value "2k")
      (footprint "eagle-import:R0805")
      (libsource (lib "eagle-import") (part "R-US_R0805"))
    )
    (comp (ref "R109")
      (value "2k")
      (footprint "eagle-import:R0805")
      (libsource (lib "eagle-import") (part "R-US_R0805"))
    )
    (comp (ref "R110")
      (value "0.2")
      (footprint "eagle-import:R4527")
      (libsource (lib "eagle-import") (part "R-US_R4527"))
    )
    (comp (ref "R111")
      (value "10k")
      (footprint "eagle-import:R0805")
      (libsource (lib "eagle-import") (part "R-US_R0805"))
    )
    (comp (ref "R112")
      (value "10k")
      (footprint "eagle-import:R0805")
      (libsource (lib "eagle-import") (part "R-US_R0805"))
    )
    (comp (ref "R113")
      (value "51.1k")
      (footprint "eagle-import:R0805")
      (libsource (lib "eagle-import") (part "R-US_R0805"))
    )
    (comp (ref "R114")
      (value "5.1k")
      (footprint "eagle-import:R0805")
      (libsource (lib "eagle-import") (part "R-US_R0805"))
    )
    (comp (ref "R115")
      (value "22k")
      (footprint "eagle-import:R0805")
      (libsource (lib "eagle-import") (part "R-US_R0805"))
    )
    (comp (ref "R116")
      (value "51.1k")
      (footprint "eagle-import:R0805")
      (libsource (lib "eagle-import") (part "R-US_R0805"))
    )
    (comp (ref "R117")
      (value "5.1k")
      (footprint "eagle-import:R0805")
      (libsource (lib "eagle-import") (part "R-US_R0805"))
    )
    (comp (ref "R118")
      (value "68.1k")
      (footprint "eagle-import:R0805")
      (libsource (lib "eagle-import") (part "R-US_R0805"))
    )
    (comp (ref "R119")
      (value "68.1k")
      (footprint "eagle-import:R0805")
      (libsource (lib "eagle-import") (part "R-US_R0805"))
    )
    (comp (ref "R120")
      (value "10k")
      (footprint "eagle-import:R0805")
      (libsource (lib "eagle-import") (part "R-US_R0805"))
    )
    (comp (ref "R121")
      (value "10k")
      (footprint "eagle-import:R0805")
      (libsource (lib "eagle-import") (part "R-US_R0805"))
    )
    (comp (ref "R122")
      (value "10k")
      (footprint "eagle-import:R0805")
      (libsource (lib "eagle-import") (part "R-US_R0805"))
    )
    (comp (ref "R123")
      (value "0.2")
      (footprint "eagle-import:R4527")
      (libsource (lib "eagle-import") (part "R-US_R4527"))
    )
    (comp (ref "R124")
      (value "2k")
      (footprint "eagle-import:M0805")
      (libsource (lib "eagle-import") (part "R-US_M0805"))
    )
    (comp (ref "R125")
      (value "2k")
      (footprint "eagle-import:R0805")
      (libsource (lib "eagle-import") (part "R-US_R0805"))
    )
    (comp (ref "R126")
      (value "10k")
      (footprint "eagle-import:R0805")
      (libsource (lib "eagle-import") (part "R-US_R0805"))
    )
    (comp (ref "R127")
      (value "2k")
      (footprint "eagle-import:R0805")
      (libsource (lib "eagle-import") (part "R-US_R0805"))
    )
    (comp (ref "R128")
      (value "2k")
      (footprint "eagle-import:R0805")
      (libsource (lib "eagle-import") (part "R-US_R0805"))
    )
    (comp (ref "R129")
      (value "0.2")
      (footprint "eagle-import:R4527")
      (libsource (lib "eagle-import") (part "R-US_R4527"))
    )
    (comp (ref "R130")
      (value "10k")
      (footprint "eagle-import:R0805")
      (libsource (lib "eagle-import") (part "R-US_R0805"))
    )
    (comp (ref "R131")
      (value "10k")
      (footprint "eagle-import:R0805")
      (libsource (lib "eagle-import") (part "R-US_R0805"))
    )
    (comp (ref "R132")
      (value "51.1k")
      (footprint "eagle-import:R0805")
      (libsource (lib "eagle-import") (part "R-US_R0805"))
    )
    (comp (ref "R133")
      (value "5.1k")
      (footprint "eagle-import:R0805")
      (libsource (lib "eagle-import") (part "R-US_R0805"))
    )
    (comp (ref "R134")
      (value "22k")
      (footprint "eagle-import:R0805")
      (libsource (lib "eagle-import") (part "R-US_R0805"))
    )
    (comp (ref "R135")
      (value "51.1k")
      (footprint "eagle-import:R0805")
      (libsource (lib "eagle-import") (part "R-US_R0805"))
    )
    (comp (ref "R136")
      (value "5.1k")
      (footprint "eagle-import:R0805")
      (libsource (lib "eagle-import") (part "R-US_R0805"))
    )
    (comp (ref "R147")
      (value "0.2")
      (footprint "eagle-import:R4527")
      (libsource (lib "eagle-import") (part "R-US_R4527"))
    )
    (comp (ref "R148")
      (value "68.1k")
      (footprint "eagle-import:R0805")
      (libsource (lib "eagle-import") (part "R-US_R0805"))
    )
    (comp (ref "R149")
      (value "68.1k")
      (footprint "eagle-import:R0805")
      (libsource (lib "eagle-import") (part "R-US_R0805"))
    )
    (comp (ref "R150")
      (value "10k")
      (footprint "eagle-import:R0805")
      (libsource (lib "eagle-import") (part "R-US_R0805"))
    )
    (comp (ref "R151")
      (value "10k")
      (footprint "eagle-import:R0805")
      (libsource (lib "eagle-import") (part "R-US_R0805"))
    )
    (comp (ref "R152")
      (value "10k")
      (footprint "eagle-import:R0805")
      (libsource (lib "eagle-import") (part "R-US_R0805"))
    )
    (comp (ref "R153")
      (value "0.2")
      (footprint "eagle-import:R4527")
      (libsource (lib "eagle-import") (part "R-US_R4527"))
    )
    (comp (ref "R154")
      (value "2k")
      (footprint "eagle-import:M0805")
      (libsource (lib "eagle-import") (part "R-US_M0805"))
    )
    (comp (ref "R164")
      (value "10k")
      (footprint "eagle-import:R0805")
      (libsource (lib "eagle-import") (part "R-US_R0805"))
    )
    (comp (ref "R165")
      (value "2k")
      (footprint "eagle-import:R0805")
      (libsource (lib "eagle-import") (part "R-US_R0805"))
    )
    (comp (ref "R166")
      (value "10k")
      (footprint "eagle-import:R0805")
      (libsource (lib "eagle-import") (part "R-US_R0805"))
    )
    (comp (ref "R167")
      (value "2k")
      (footprint "eagle-import:R0805")
      (libsource (lib "eagle-import") (part "R-US_R0805"))
    )
    (comp (ref "R168")
      (value "2k")
      (footprint "eagle-import:R0805")
      (libsource (lib "eagle-import") (part "R-US_R0805"))
    )
    (comp (ref "R169")
      (value "0.2")
      (footprint "eagle-import:R4527")
      (libsource (lib "eagle-import") (part "R-US_R4527"))
    )
    (comp (ref "R170")
      (value "10k")
      (footprint "eagle-import:R0805")
      (libsource (lib "eagle-import") (part "R-US_R0805"))
    )
    (comp (ref "R171")
      (value "10k")
      (footprint "eagle-import:R0805")
      (libsource (lib "eagle-import") (part "R-US_R0805"))
    )
    (comp (ref "R185")
      (value "2Meg")
      (footprint "eagle-import:R0805")
      (libsource (lib "eagle-import") (part "R-US_R0805"))
    )
    (comp (ref "R186")
      (value "2Meg")
      (footprint "eagle-import:R0805")
      (libsource (lib "eagle-import") (part "R-US_R0805"))
    )
    (comp (ref "R187")
      (value "2Meg")
      (footprint "eagle-import:R0805")
      (libsource (lib "eagle-import") (part "R-US_R0805"))
    )
    (comp (ref "R188")
      (value "2Meg")
      (footprint "eagle-import:R0805")
      (libsource (lib "eagle-import") (part "R-US_R0805"))
    )
    (comp (ref "R189")
      (value "2Meg")
      (footprint "eagle-import:R0805")
      (libsource (lib "eagle-import") (part "R-US_R0805"))
    )
    (comp (ref "R190")
      (value "2Meg")
      (footprint "eagle-import:R0805")
      (libsource (lib "eagle-import") (part "R-US_R0805"))
    )
    (comp (ref "R191")
      (value "2Meg")
      (footprint "eagle-import:R0805")
      (libsource (lib "eagle-import") (part "R-US_R0805"))
    )
    (comp (ref "R192")
      (value "2Meg")
      (footprint "eagle-import:R0805")
      (libsource (lib "eagle-import") (part "R-US_R0805"))
    )
    (comp (ref "R193")
      (value "330")
      (footprint "eagle-import:R2512")
      (libsource (lib "eagle-import") (part "R-US_R2512"))
    )
    (comp (ref "R194")
      (value "330")
      (footprint "eagle-import:R2512")
      (libsource (lib "eagle-import") (part "R-US_R2512"))
    )
    (comp (ref "R195")
      (value "330")
      (footprint "eagle-import:R2512")
      (libsource (lib "eagle-import") (part "R-US_R2512"))
    )
    (comp (ref "R196")
      (value "330")
      (footprint "eagle-import:R2512")
      (libsource (lib "eagle-import") (part "R-US_R2512"))
    )
    (comp (ref "R197")
      (value "330")
      (footprint "eagle-import:R2512")
      (libsource (lib "eagle-import") (part "R-US_R2512"))
    )
    (comp (ref "R198")
      (value "330")
      (footprint "eagle-import:R2512")
      (libsource (lib "eagle-import") (part "R-US_R2512"))
    )
    (comp (ref "R199")
      (value "330")
      (footprint "eagle-import:R2512")
      (libsource (lib "eagle-import") (part "R-US_R2512"))
    )
    (comp (ref "R200")
      (value "330")
      (footprint "eagle-import:R2512")
      (libsource (lib "eagle-import") (part "R-US_R2512"))
    )
    (comp (ref "U$1")
      (value "OPA549_HS677NOHS")
      (footprint "eagle-import:OPA549")
      (libsource (lib "eagle-import") (part "OPA549_HS677NOHS"))
    )
    (comp (ref "U$2")
      (value "OPA549_HS677NOHS")
      (footprint "eagle-import:OPA549")
      (libsource (lib "eagle-import") (part "OPA549_HS677NOHS"))
    )
    (comp (ref "U$3")
      (value "OPA549_HS677NOHS")
      (footprint "eagle-import:OPA549")
      (libsource (lib "eagle-import") (part "OPA549_HS677NOHS"))
    )
    (comp (ref "U$4")
      (value "OPA549_HS677NOHS")
      (footprint "eagle-import:OPA549")
      (libsource (lib "eagle-import") (part "OPA549_HS677NOHS"))
    )
    (comp (ref "U$5")
      (value "OPA549_HS677NOHS")
      (footprint "eagle-import:OPA549")
      (libsource (lib "eagle-import") (part "OPA549_HS677NOHS"))
    )
    (comp (ref "U$6")
      (value "OPA549_HS677NOHS")
      (footprint "eagle-import:OPA549")
      (libsource (lib "eagle-import") (part "OPA549_HS677NOHS"))
    )
    (comp (ref "U$7")
      (value "OPA549_HS677NOHS")
      (footprint "eagle-import:OPA549")
      (libsource (lib "eagle-import") (part "OPA549_HS677NOHS"))
    )
    (comp (ref "U$8")
      (value "OPA549_HS677NOHS")
      (footprint "eagle-import:OPA549")
      (libsource (lib "eagle-import") (part "OPA549_HS677NOHS"))
    )
    (comp (ref "U$9")
      (value "OPA549_HS677NOHS")
      (footprint "eagle-import:OPA549")
      (libsource (lib "eagle-import") (part "OPA549_HS677NOHS"))
    )
    (comp (ref "U$10")
      (value "OPA549_HS677NOHS")
      (footprint "eagle-import:OPA549")
      (libsource (lib "eagle-import") (part "OPA549_HS677NOHS"))
    )
    (comp (ref "U$11")
      (value "OPA549_HS677NOHS")
      (footprint "eagle-import:OPA549")
      (libsource (lib "eagle-import") (part "OPA549_HS677NOHS"))
    )
    (comp (ref "U$12")
      (value "OPA549_HS677NOHS")
      (footprint "eagle-import:OPA549")
      (libsource (lib "eagle-import") (part "OPA549_HS677NOHS"))
    )
    (comp (ref "U$13")
      (value "OPA549_HS677NOHS")
      (footprint "eagle-import:OPA549")
      (libsource (lib "eagle-import") (part "OPA549_HS677NOHS"))
    )
    (comp (ref "U$14")
      (value "OPA549_HS677NOHS")
      (footprint "eagle-import:OPA549")
      (libsource (lib "eagle-import") (part "OPA549_HS677NOHS"))
    )
    (comp (ref "U$15")
      (value "OPA549_HS677NOHS")
      (footprint "eagle-import:OPA549")
      (libsource (lib "eagle-import") (part "OPA549_HS677NOHS"))
    )
    (comp (ref "U$16")
      (value "OPA549_HS677NOHS")
      (footprint "eagle-import:OPA549")
      (libsource (lib "eagle-import") (part "OPA549_HS677NOHS"))
    )
    (comp (ref "U2")
      (value "INA170EA/250")
      (footprint "eagle-import:SOP65P490X110-8N")
      (libsource (lib "eagle-import") (part "INA170EA/250"))
    )
    (comp (ref "U3")
      (value "INA170EA/250")
      (footprint "eagle-import:SOP65P490X110-8N")
      (libsource (lib "eagle-import") (part "INA170EA/250"))
    )
    (comp (ref "U4")
      (value "OPA2340EA/250")
      (footprint "eagle-import:SOP65P490X110-8N")
      (libsource (lib "eagle-import") (part "OPA2340EA/250"))
    )
    (comp (ref "U5")
      (value "OPA2340EA/250")
      (footprint "eagle-import:SOP65P490X110-8N")
      (libsource (lib "eagle-import") (part "OPA2340EA/250"))
    )
    (comp (ref "U6")
      (value "INA170EA/250")
      (footprint "eagle-import:SOP65P490X110-8N")
      (libsource (lib "eagle-import") (part "INA170EA/250"))
    )
    (comp (ref "U7")
      (value "OPA2340EA/250")
      (footprint "eagle-import:SOP65P490X110-8N")
      (libsource (lib "eagle-import") (part "OPA2340EA/250"))
    )
    (comp (ref "U8")
      (value "INA170EA/250")
      (footprint "eagle-import:SOP65P490X110-8N")
      (libsource (lib "eagle-import") (part "INA170EA/250"))
    )
    (comp (ref "U12")
      (value "OPA2340EA/250")
      (footprint "eagle-import:SOP65P490X110-8N")
      (libsource (lib "eagle-import") (part "OPA2340EA/250"))
    )
    (comp (ref "U13")
      (value "INA170EA/250")
      (footprint "eagle-import:SOP65P490X110-8N")
      (libsource (lib "eagle-import") (part "INA170EA/250"))
    )
    (comp (ref "U14")
      (value "OPA2340EA/250")
      (footprint "eagle-import:SOP65P490X110-8N")
      (libsource (lib "eagle-import") (part "OPA2340EA/250"))
    )
    (comp (ref "U15")
      (value "INA170EA/250")
      (footprint "eagle-import:SOP65P490X110-8N")
      (libsource (lib "eagle-import") (part "INA170EA/250"))
    )
    (comp (ref "U16")
      (value "OPA2340EA/250")
      (footprint "eagle-import:SOP65P490X110-8N")
      (libsource (lib "eagle-import") (part "OPA2340EA/250"))
    )
    (comp (ref "U17")
      (value "INA170EA/250")
      (footprint "eagle-import:SOP65P490X110-8N")
      (libsource (lib "eagle-import") (part "INA170EA/250"))
    )
    (comp (ref "U18")
      (value "OPA2340EA/250")
      (footprint "eagle-import:SOP65P490X110-8N")
      (libsource (lib "eagle-import") (part "OPA2340EA/250"))
    )
    (comp (ref "U19")
      (value "INA170EA/250")
      (footprint "eagle-import:SOP65P490X110-8N")
      (libsource (lib "eagle-import") (part "INA170EA/250"))
    )
    (comp (ref "U20")
      (value "OPA2340EA/250")
      (footprint "eagle-import:SOP65P490X110-8N")
      (libsource (lib "eagle-import") (part "OPA2340EA/250"))
    )
    (comp (ref "U031")
      (value "0881070")
      (footprint "eagle-import:881")
      (libsource (lib "eagle-import") (part "0881070"))
    )
    (comp (ref "C85")
      (value "0.1uF")
      (footprint "eagle-import:C0603")
      (libsource (lib "eagle-import") (part "C-USC0603"))
    )
    (comp (ref "C86")
      (value "0.1uF")
      (footprint "eagle-import:C0603")
      (libsource (lib "eagle-import") (part "C-USC0603"))
    )
    (comp (ref "C87")
      (value "0.1uF")
      (footprint "eagle-import:C0603")
      (libsource (lib "eagle-import") (part "C-USC0603"))
    )
    (comp (ref "C88")
      (value "0.1uF")
      (footprint "eagle-import:C0603")
      (libsource (lib "eagle-import") (part "C-USC0603"))
    )
    (comp (ref "C89")
      (value "0.1uF")
      (footprint "eagle-import:C0603")
      (libsource (lib "eagle-import") (part "C-USC0603"))
    )
    (comp (ref "C90")
      (value "0.1uF")
      (footprint "eagle-import:C0603")
      (libsource (lib "eagle-import") (part "C-USC0603"))
    )
    (comp (ref "C91")
      (value "0.1uF")
      (footprint "eagle-import:C0603")
      (libsource (lib "eagle-import") (part "C-USC0603"))
    )
    (comp (ref "C92")
      (value "0.1uF")
      (footprint "eagle-import:C0603")
      (libsource (lib "eagle-import") (part "C-USC0603"))
    )
    (comp (ref "C93")
      (value "0.1uF")
      (footprint "eagle-import:C0603")
      (libsource (lib "eagle-import") (part "C-USC0603"))
    )
    (comp (ref "C94")
      (value "0.1uF")
      (footprint "eagle-import:C0603")
      (libsource (lib "eagle-import") (part "C-USC0603"))
    )
    (comp (ref "C95")
      (value "10uF")
      (footprint "eagle-import:C1206")
      (libsource (lib "eagle-import") (part "C-USC1206"))
    )
    (comp (ref "C96")
      (value "10uF")
      (footprint "eagle-import:C1206")
      (libsource (lib "eagle-import") (part "C-USC1206"))
    )
    (comp (ref "C97")
      (value "1uF")
      (footprint "eagle-import:C0603")
      (libsource (lib "eagle-import") (part "C-USC0603"))
    )
    (comp (ref "C98")
      (value "10uF")
      (footprint "eagle-import:C1206")
      (libsource (lib "eagle-import") (part "C-USC1206"))
    )
    (comp (ref "C99")
      (value "0.1uF")
      (footprint "eagle-import:C0603")
      (libsource (lib "eagle-import") (part "C-USC0603"))
    )
    (comp (ref "C100")
      (value "10uF")
      (footprint "eagle-import:C1206")
      (libsource (lib "eagle-import") (part "C-USC1206"))
    )
    (comp (ref "C101")
      (value "10uF")
      (footprint "eagle-import:C1206")
      (libsource (lib "eagle-import") (part "C-USC1206"))
    )
    (comp (ref "C102")
      (value "0.1uF")
      (footprint "eagle-import:C0603")
      (libsource (lib "eagle-import") (part "C-USC0603"))
    )
    (comp (ref "C103")
      (value "0.1uF")
      (footprint "eagle-import:C0603")
      (libsource (lib "eagle-import") (part "C-USC0603"))
    )
    (comp (ref "C104")
      (value "0.1uF")
      (footprint "eagle-import:C0603")
      (libsource (lib "eagle-import") (part "C-USC0603"))
    )
    (comp (ref "C105")
      (value "0.1uF")
      (footprint "eagle-import:C0603")
      (libsource (lib "eagle-import") (part "C-USC0603"))
    )
    (comp (ref "C106")
      (value "0.1uF")
      (footprint "eagle-import:C0603")
      (libsource (lib "eagle-import") (part "C-USC0603"))
    )
    (comp (ref "C107")
      (value "0.1uF")
      (footprint "eagle-import:C0603")
      (libsource (lib "eagle-import") (part "C-USC0603"))
    )
    (comp (ref "C108")
      (value "0.1uF")
      (footprint "eagle-import:C0603")
      (libsource (lib "eagle-import") (part "C-USC0603"))
    )
    (comp (ref "C109")
      (value "0.1uF")
      (footprint "eagle-import:C0603")
      (libsource (lib "eagle-import") (part "C-USC0603"))
    )
    (comp (ref "C118")
      (value "0.1uF")
      (footprint "eagle-import:C0603")
      (libsource (lib "eagle-import") (part "C-USC0603"))
    )
    (comp (ref "C119")
      (value "0.1uF")
      (footprint "eagle-import:C0603")
      (libsource (lib "eagle-import") (part "C-USC0603"))
    )
    (comp (ref "C129")
      (value "0.1uF")
      (footprint "eagle-import:C0603")
      (libsource (lib "eagle-import") (part "C-USC0603"))
    )
    (comp (ref "C130")
      (value "0.1uF")
      (footprint "eagle-import:C0603")
      (libsource (lib "eagle-import") (part "C-USC0603"))
    )
    (comp (ref "C131")
      (value "0.1uF")
      (footprint "eagle-import:C0603")
      (libsource (lib "eagle-import") (part "C-USC0603"))
    )
    (comp (ref "IC1")
      (value "LINEAR_7805DT")
      (footprint "eagle-import:LINEAR_TO252")
      (libsource (lib "eagle-import") (part "LINEAR_78DT05"))
    )
    (comp (ref "IC2")
      (value "74LS279D")
      (footprint "eagle-import:SO16")
      (libsource (lib "eagle-import") (part "74279DLS"))
    )
    (comp (ref "IC3")
      (value "7400D")
      (footprint "eagle-import:SO14")
      (libsource (lib "eagle-import") (part "7400D"))
    )
    (comp (ref "IC4")
      (value "74LS138D")
      (footprint "eagle-import:SO16")
      (libsource (lib "eagle-import") (part "74138DLS"))
    )
    (comp (ref "IC5")
      (value "LMV321M5")
      (footprint "eagle-import:SOT23-5")
      (libsource (lib "eagle-import") (part "LMV321?M5"))
    )
    (comp (ref "IC6")
      (value "74LS240DW")
      (footprint "eagle-import:SO20W")
      (libsource (lib "eagle-import") (part "74240DWLS"))
    )
    (comp (ref "JP1")
      (value "PINHD-1X8")
      (footprint "eagle-import:1X08")
      (libsource (lib "eagle-import") (part "PINHD-1X8"))
    )
    (comp (ref "JP2")
      (value "PINHD-1X8")
      (footprint "eagle-import:1X08")
      (libsource (lib "eagle-import") (part "PINHD-1X8"))
    )
    (comp (ref "LED1")
      (value "LEDCHIPLED_0805")
      (footprint "eagle-import:CHIPLED_0805")
      (libsource (lib "eagle-import") (part "LEDCHIPLED_0805"))
    )
    (comp (ref "LED2")
      (value "LEDCHIPLED_0805")
      (footprint "eagle-import:CHIPLED_0805")
      (libsource (lib "eagle-import") (part "LEDCHIPLED_0805"))
    )
    (comp (ref "LED3")
      (value "LEDCHIPLED_0805")
      (footprint "eagle-import:CHIPLED_0805")
      (libsource (lib "eagle-import") (part "LEDCHIPLED_0805"))
    )
    (comp (ref "R000")
      (value "100")
      (footprint "eagle-import:R0805")
      (fields (field (name "SPICEPREFIX") "100"))
      (libsource (lib "eagle-import") (part "R-US_R0805"))
    )
    (comp (ref "R137")
      (value "100")
      (footprint "eagle-import:R0805")
      (fields (field (name "SPICEPREFIX") "100"))
      (libsource (lib "eagle-import") (part "R-US_R0805"))
    )
    (comp (ref "R138")
      (value "100")
      (footprint "eagle-import:R0805")
      (fields (field (name "SPICEPREFIX") "100"))
      (libsource (lib "eagle-import") (part "R-US_R0805"))
    )
    (comp (ref "R139")
      (value "100")
      (footprint "eagle-import:R0805")
      (fields (field (name "SPICEPREFIX") "100"))
      (libsource (lib "eagle-import") (part "R-US_R0805"))
    )
    (comp (ref "R140")
      (value "100")
      (footprint "eagle-import:R0805")
      (fields (field (name "SPICEPREFIX") "100"))
      (libsource (lib "eagle-import") (part "R-US_R0805"))
    )
    (comp (ref "R141")
      (value "2k")
      (footprint "eagle-import:R0805")
      (fields (field (name "SPICEPREFIX") "2k"))
      (libsource (lib "eagle-import") (part "R-US_R0805"))
    )
    (comp (ref "R142")
      (value "330")
      (footprint "eagle-import:R0805")
      (fields (field (name "SPICEPREFIX") "330"))
      (libsource (lib "eagle-import") (part "R-US_R0805"))
    )
    (comp (ref "R143")
      (value "330")
      (footprint "eagle-import:R0805")
      (fields (field (name "SPICEPREFIX") "330"))
      (libsource (lib "eagle-import") (part "R-US_R0805"))
    )
    (comp (ref "R144")
      (value "330")
      (footprint "eagle-import:R0805")
      (fields (field (name "SPICEPREFIX") "330"))
      (libsource (lib "eagle-import") (part "R-US_R0805"))
    )
    (comp (ref "R145")
      (value "2k")
      (footprint "eagle-import:R0805")
      (libsource (lib "eagle-import") (part "R-US_R0805"))
    )
    (comp (ref "R146")
      (value "2k")
      (footprint "eagle-import:R0805")
      (libsource (lib "eagle-import") (part "R-US_R0805"))
    )
    (comp (ref "R155")
      (value "0")
      (footprint "eagle-import:R0603")
      (libsource (lib "eagle-import") (part "R-US_R0603"))
    )
    (comp (ref "R156")
      (value "0")
      (footprint "eagle-import:R0603")
      (libsource (lib "eagle-import") (part "R-US_R0603"))
    )
    (comp (ref "R157")
      (value "0")
      (footprint "eagle-import:R0603")
      (libsource (lib "eagle-import") (part "R-US_R0603"))
    )
    (comp (ref "R158")
      (value "0")
      (footprint "eagle-import:R0603")
      (libsource (lib "eagle-import") (part "R-US_R0603"))
    )
    (comp (ref "R159")
      (value "0")
      (footprint "eagle-import:R0603")
      (libsource (lib "eagle-import") (part "R-US_R0603"))
    )
    (comp (ref "R160")
      (value "0")
      (footprint "eagle-import:R0603")
      (libsource (lib "eagle-import") (part "R-US_R0603"))
    )
    (comp (ref "R161")
      (value "0")
      (footprint "eagle-import:R0603")
      (libsource (lib "eagle-import") (part "R-US_R0603"))
    )
    (comp (ref "R162")
      (value "0")
      (footprint "eagle-import:R0603")
      (libsource (lib "eagle-import") (part "R-US_R0603"))
    )
    (comp (ref "R163")
      (value "10k")
      (footprint "eagle-import:R0603")
      (libsource (lib "eagle-import") (part "R-US_R0603"))
    )
    (comp (ref "R172")
      (value "100")
      (footprint "eagle-import:R0805")
      (fields (field (name "SPICEPREFIX") "100"))
      (libsource (lib "eagle-import") (part "R-US_R0805"))
    )
    (comp (ref "R173")
      (value "330")
      (footprint "eagle-import:R0805")
      (fields (field (name "SPICEPREFIX") "330"))
      (libsource (lib "eagle-import") (part "R-US_R0805"))
    )
    (comp (ref "R174")
      (value "330")
      (footprint "eagle-import:R0805")
      (fields (field (name "SPICEPREFIX") "330"))
      (libsource (lib "eagle-import") (part "R-US_R0805"))
    )
    (comp (ref "R175")
      (value "330")
      (footprint "eagle-import:R0805")
      (fields (field (name "SPICEPREFIX") "330"))
      (libsource (lib "eagle-import") (part "R-US_R0805"))
    )
    (comp (ref "R176")
      (value "330")
      (footprint "eagle-import:R0805")
      (fields (field (name "SPICEPREFIX") "330"))
      (libsource (lib "eagle-import") (part "R-US_R0805"))
    )
    (comp (ref "R177")
      (value "330")
      (footprint "eagle-import:R0805")
      (fields (field (name "SPICEPREFIX") "330"))
      (libsource (lib "eagle-import") (part "R-US_R0805"))
    )
    (comp (ref "R178")
      (value "330")
      (footprint "eagle-import:R0805")
      (fields (field (name "SPICEPREFIX") "330"))
      (libsource (lib "eagle-import") (part "R-US_R0805"))
    )
    (comp (ref "R179")
      (value "330")
      (footprint "eagle-import:R0805")
      (fields (field (name "SPICEPREFIX") "330"))
      (libsource (lib "eagle-import") (part "R-US_R0805"))
    )
    (comp (ref "R180")
      (value "330")
      (footprint "eagle-import:R0805")
      (fields (field (name "SPICEPREFIX") "330"))
      (libsource (lib "eagle-import") (part "R-US_R0805"))
    )
    (comp (ref "R181")
      (value "330")
      (footprint "eagle-import:R0805")
      (fields (field (name "SPICEPREFIX") "330"))
      (libsource (lib "eagle-import") (part "R-US_R0805"))
    )
    (comp (ref "R182")
      (value "330")
      (footprint "eagle-import:R0805")
      (fields (field (name "SPICEPREFIX") "330"))
      (libsource (lib "eagle-import") (part "R-US_R0805"))
    )
    (comp (ref "R183")
      (value "330")
      (footprint "eagle-import:R0805")
      (fields (field (name "SPICEPREFIX") "330"))
      (libsource (lib "eagle-import") (part "R-US_R0805"))
    )
    (comp (ref "R184")
      (value "100")
      (footprint "eagle-import:R0805")
      (fields (field (name "SPICEPREFIX") "100"))
      (libsource (lib "eagle-import") (part "R-US_R0805"))
    )
    (comp (ref "U001")
      (value "65LVDS34")
      (footprint "eagle-import:SO08-1")
      (libsource (lib "eagle-import") (part "DS9637A"))
    )
    (comp (ref "U9")
      (value "LTC2656BCFE-H16PBF")
      (footprint "eagle-import:SOP65P640X120-21N")
      (fields (field (name "MPN") "LTC2656BCFE-H16#PBF"))
      (libsource (lib "eagle-import") (part "LTC2656BCFE-H16PBF"))
    )
    (comp (ref "U10")
      (value "LTC1863CGNPBF")
      (footprint "eagle-import:SOP63P600X175-16N")
      (fields (field (name "MPN") "LTC1863CGN#PBF"))
      (libsource (lib "eagle-import") (part "LTC1863CGNPBF"))
    )
    (comp (ref "U011")
      (value "65LVDS9638")
      (footprint "eagle-import:SO08-1")
      (libsource (lib "eagle-import") (part "DS9638"))
    )
    (comp (ref "U021")
      (value "65LVDS34")
      (footprint "eagle-import:SO08-1")
      (libsource (lib "eagle-import") (part "DS9637A"))
    )
    (comp (ref "U025")
      (value "ACSL-6400")
      (footprint "eagle-import:ACSL-SO16")
      (libsource (lib "eagle-import") (part "ACSL-6400"))
    )
    (comp (ref "U026")
      (value "ACSL-6420")
      (footprint "eagle-import:ACSL-SO16")
      (libsource (lib "eagle-import") (part "ACSL-6420"))
    )
    (comp (ref "U030")
      (value "65LVDS34")
      (footprint "eagle-import:SO08-1")
      (libsource (lib "eagle-import") (part "DS9637A"))
    )
    (comp (ref "U040")
      (value "1N4148")
      (footprint "eagle-import:1N4148")
      (libsource (lib "eagle-import") (part "1N4148"))
    )
    (comp (ref "U041")
      (value "1N4148")
      (footprint "eagle-import:1N4148")
      (libsource (lib "eagle-import") (part "1N4148"))
    )
    (comp (ref "U042")
      (value "1N4148")
      (footprint "eagle-import:1N4148")
      (libsource (lib "eagle-import") (part "1N4148"))
    )
    (comp (ref "U043")
      (value "1N4148")
      (footprint "eagle-import:1N4148")
      (libsource (lib "eagle-import") (part "1N4148"))
    )
    (comp (ref "U044")
      (value "1N4148")
      (footprint "eagle-import:1N4148")
      (libsource (lib "eagle-import") (part "1N4148"))
    )
    (comp (ref "U045")
      (value "1N4148")
      (footprint "eagle-import:1N4148")
      (libsource (lib "eagle-import") (part "1N4148"))
    )
    (comp (ref "U046")
      (value "1N4148")
      (footprint "eagle-import:1N4148")
      (libsource (lib "eagle-import") (part "1N4148"))
    )
    (comp (ref "X002")
      (value "RJ45V")
      (footprint "eagle-import:RJ45-VERTICAL")
      (libsource (lib "eagle-import") (part "RJ45V"))
    )
    (comp (ref "X003")
      (value "RJ45V")
      (footprint "eagle-import:RJ45-VERTICAL")
      (libsource (lib "eagle-import") (part "RJ45V"))
    )
  )
  (nets
    (net (code "1") (name "+5V") (class "Default")
      (node (ref "C10") (pin "1") (pinfunction "1_1") (pintype "passive"))
      (node (ref "C101") (pin "1") (pinfunction "1_1") (pintype "passive"))
      (node (ref "C102") (pin "1") (pinfunction "1_1") (pintype "passive"))
      (node (ref "C103") (pin "1") (pinfunction "1_1") (pintype "passive"))
      (node (ref "C104") (pin "1") (pinfunction "1_1") (pintype "passive"))
      (node (ref "C107") (pin "1") (pinfunction "1_1") (pintype "passive"))
      (node (ref "C116") (pin "1") (pinfunction "1_1") (pintype "passive"))
      (node (ref "C117") (pin "1") (pinfunction "1_1") (pintype "passive"))
      (node (ref "C118") (pin "1") (pinfunction "1_1") (pintype "passive"))
      (node (ref "C15") (pin "1") (pinfunction "1_1") (pintype "passive"))
      (node (ref "C25") (pin "1") (pinfunction "1_1") (pintype "passive"))
      (node (ref "C26") (pin "1") (pinfunction "1_1") (pintype "passive"))
      (node (ref "C36") (pin "1") (pinfunction "1_1") (pintype "passive"))
      (node (ref "C37") (pin "1") (pinfunction "1_1") (pintype "passive"))
      (node (ref "C47") (pin "1") (pinfunction "1_1") (pintype "passive"))
      (node (ref "C48") (pin "1") (pinfunction "1_1") (pintype "passive"))
      (node (ref "C58") (pin "1") (pinfunction "1_1") (pintype "passive"))
      (node (ref "C59") (pin "1") (pinfunction "1_1") (pintype "passive"))
      (node (ref "C69") (pin "1") (pinfunction "1_1") (pintype "passive"))
      (node (ref "C70") (pin "1") (pinfunction "1_1") (pintype "passive"))
      (node (ref "C80") (pin "1") (pinfunction "1_1") (pintype "passive"))
      (node (ref "C81") (pin "1") (pinfunction "1_1") (pintype "passive"))
      (node (ref "C89") (pin "1") (pinfunction "1_1") (pintype "passive"))
      (node (ref "C90") (pin "1") (pinfunction "1_1") (pintype "passive"))
      (node (ref "C91") (pin "1") (pinfunction "1_1") (pintype "passive"))
      (node (ref "C92") (pin "1") (pinfunction "1_1") (pintype "passive"))
      (node (ref "C93") (pin "1") (pinfunction "1_1") (pintype "passive"))
      (node (ref "C94") (pin "1") (pinfunction "1_1") (pintype "passive"))
      (node (ref "C97") (pin "1") (pinfunction "1_1") (pintype "passive"))
      (node (ref "C98") (pin "1") (pinfunction "1_1") (pintype "passive"))
      (node (ref "C99") (pin "1") (pinfunction "1_1") (pintype "passive"))
      (node (ref "IC1") (pin "2") (pinfunction "VO_2") (pintype "passive"))
      (node (ref "IC2") (pin "16") (pinfunction "VCC_16") (pintype "power_in"))
      (node (ref "IC3") (pin "14") (pinfunction "VCC_14") (pintype "power_in"))
      (node (ref "IC4") (pin "16") (pinfunction "VCC_16") (pintype "power_in"))
      (node (ref "IC4") (pin "6") (pinfunction "G1_6") (pintype "input"))
      (node (ref "IC5") (pin "5") (pinfunction "V+_5") (pintype "power_in"))
      (node (ref "IC6") (pin "20") (pinfunction "VCC_20") (pintype "power_in"))
      (node (ref "LED2") (pin "A") (pinfunction "A_A") (pintype "passive"))
      (node (ref "R141") (pin "2") (pinfunction "2_2") (pintype "passive"))
      (node (ref "R142") (pin "2") (pinfunction "2_2") (pintype "passive"))
      (node (ref "R143") (pin "2") (pinfunction "2_2") (pintype "passive"))
      (node (ref "R144") (pin "2") (pinfunction "2_2") (pintype "passive"))
      (node (ref "R163") (pin "1") (pinfunction "1_1") (pintype "passive"))
      (node (ref "R175") (pin "2") (pinfunction "2_2") (pintype "passive"))
      (node (ref "R176") (pin "2") (pinfunction "2_2") (pintype "passive"))
      (node (ref "U025") (pin "10") (pinfunction "VDD1_10") (pintype "bidirectional"))
      (node (ref "U025") (pin "15") (pinfunction "VDD2_15") (pintype "bidirectional"))
      (node (ref "U026") (pin "12") (pinfunction "VDD2_12") (pintype "bidirectional"))
      (node (ref "U10") (pin "16") (pinfunction "VDD_16") (pintype "power_in"))
      (node (ref "U12") (pin "8") (pinfunction "V+_8") (pintype "power_in"))
      (node (ref "U13") (pin "8") (pinfunction "V+_8") (pintype "power_in"))
      (node (ref "U14") (pin "8") (pinfunction "V+_8") (pintype "power_in"))
      (node (ref "U15") (pin "8") (pinfunction "V+_8") (pintype "power_in"))
      (node (ref "U16") (pin "8") (pinfunction "V+_8") (pintype "power_in"))
      (node (ref "U17") (pin "8") (pinfunction "V+_8") (pintype "power_in"))
      (node (ref "U18") (pin "8") (pinfunction "V+_8") (pintype "power_in"))
      (node (ref "U19") (pin "8") (pinfunction "V+_8") (pintype "power_in"))
      (node (ref "U2") (pin "8") (pinfunction "V+_8") (pintype "power_in"))
      (node (ref "U20") (pin "8") (pinfunction "V+_8") (pintype "power_in"))
      (node (ref "U3") (pin "8") (pinfunction "V+_8") (pintype "power_in"))
      (node (ref "U4") (pin "8") (pinfunction "V+_8") (pintype "power_in"))
      (node (ref "U5") (pin "8") (pinfunction "V+_8") (pintype "power_in"))
      (node (ref "U6") (pin "8") (pinfunction "V+_8") (pintype "power_in"))
      (node (ref "U7") (pin "8") (pinfunction "V+_8") (pintype "power_in"))
      (node (ref "U8") (pin "8") (pinfunction "V+_8") (pintype "power_in"))
      (node (ref "U9") (pin "14") (pinfunction "PORSEL_14") (pintype "input"))
      (node (ref "U9") (pin "19") (pinfunction "VCC_19") (pintype "power_in"))
      (node (ref "U9") (pin "8") (pinfunction "~{LDAC}_8") (pintype "input"))
    )
    (net (code "2") (name "+5V{slash}1") (class "Default")
      (node (ref "C105") (pin "1") (pinfunction "1_1") (pintype "passive"))
      (node (ref "C106") (pin "1") (pinfunction "1_1") (pintype "passive"))
      (node (ref "C108") (pin "1") (pinfunction "1_1") (pintype "passive"))
      (node (ref "C109") (pin "1") (pinfunction "1_1") (pintype "passive"))
      (node (ref "C119") (pin "1") (pinfunction "1_1") (pintype "passive"))
      (node (ref "C129") (pin "1") (pinfunction "1_1") (pintype "passive"))
      (node (ref "C130") (pin "1") (pinfunction "1_1") (pintype "passive"))
      (node (ref "C131") (pin "1") (pinfunction "1_1") (pintype "passive"))
      (node (ref "R139") (pin "2") (pinfunction "2_2") (pintype "passive"))
      (node (ref "R173") (pin "2") (pinfunction "2_2") (pintype "passive"))
      (node (ref "R174") (pin "2") (pinfunction "2_2") (pintype "passive"))
      (node (ref "U001") (pin "1") (pinfunction "VCC_1") (pintype "bidirectional"))
      (node (ref "U011") (pin "1") (pinfunction "VCC_1") (pintype "bidirectional"))
      (node (ref "U021") (pin "1") (pinfunction "VCC_1") (pintype "bidirectional"))
      (node (ref "U025") (pin "1") (pinfunction "AN1_1") (pintype "bidirectional"))
      (node (ref "U025") (pin "3") (pinfunction "AN2_3") (pintype "bidirectional"))
      (node (ref "U025") (pin "5") (pinfunction "AN3_5") (pintype "bidirectional"))
      (node (ref "U026") (pin "4") (pinfunction "VDD1_4") (pintype "bidirectional"))
      (node (ref "U026") (pin "5") (pinfunction "AN1_5") (pintype "bidirectional"))
      (node (ref "U026") (pin "7") (pinfunction "AN2_7") (pintype "bidirectional"))
      (node (ref "U030") (pin "1") (pinfunction "VCC_1") (pintype "bidirectional"))
      (node (ref "X003") (pin "7") (pinfunction "7_7") (pintype "passive"))
    )
    (net (code "3") (name "ADC_SEL") (class "Default")
      (node (ref "IC4") (pin "14") (pinfunction "Y1_14") (pintype "output"))
      (node (ref "U10") (pin "11") (pinfunction "~{CS/CONV}_11") (pintype "input"))
    )
    (net (code "4") (name "BOARD") (class "Default")
      (node (ref "IC4") (pin "4") (pinfunction "G2A_4") (pintype "input"))
      (node (ref "R142") (pin "1") (pinfunction "1_1") (pintype "passive"))
      (node (ref "U025") (pin "13") (pinfunction "OUT2_13") (pintype "bidirectional"))
    )
    (net (code "5") (name "BOARD_I") (class "Default")
      (node (ref "R177") (pin "1") (pinfunction "1_1") (pintype "passive"))
      (node (ref "U030") (pin "2") (pinfunction "OUTA_2") (pintype "bidirectional"))
      (node (ref "U040") (pin "2") (pinfunction "C_2") (pintype "passive"))
    )
    (net (code "6") (name "BOARD_II") (class "Default")
      (node (ref "R177") (pin "2") (pinfunction "2_2") (pintype "passive"))
      (node (ref "U025") (pin "4") (pinfunction "CATH2_4") (pintype "bidirectional"))
      (node (ref "U040") (pin "1") (pinfunction "A_1") (pintype "passive"))
    )
    (net (code "7") (name "BOARD_Y") (class "Default")
      (node (ref "R137") (pin "2") (pinfunction "2_2") (pintype "passive"))
      (node (ref "U030") (pin "8") (pinfunction "INA1_8") (pintype "bidirectional"))
      (node (ref "X003") (pin "1") (pinfunction "1_1") (pintype "passive"))
    )
    (net (code "8") (name "BOARD_Z") (class "Default")
      (node (ref "R137") (pin "1") (pinfunction "1_1") (pintype "passive"))
      (node (ref "U030") (pin "7") (pinfunction "INA2_7") (pintype "bidirectional"))
      (node (ref "X003") (pin "2") (pinfunction "2_2") (pintype "passive"))
    )
    (net (code "9") (name "DAC_OUT_A") (class "Default")
      (node (ref "JP2") (pin "1") (pinfunction "1_1") (pintype "passive"))
      (node (ref "R155") (pin "2") (pinfunction "2_2") (pintype "passive"))
      (node (ref "R8") (pin "1") (pinfunction "1_1") (pintype "passive"))
    )
    (net (code "10") (name "DAC_OUT_B") (class "Default")
      (node (ref "JP2") (pin "2") (pinfunction "2_2") (pintype "passive"))
      (node (ref "R156") (pin "2") (pinfunction "2_2") (pintype "passive"))
      (node (ref "R25") (pin "1") (pinfunction "1_1") (pintype "passive"))
    )
    (net (code "11") (name "DAC_OUT_C") (class "Default")
      (node (ref "JP2") (pin "3") (pinfunction "3_3") (pintype "passive"))
      (node (ref "R157") (pin "2") (pinfunction "2_2") (pintype "passive"))
      (node (ref "R44") (pin "1") (pinfunction "1_1") (pintype "passive"))
    )
    (net (code "12") (name "DAC_OUT_D") (class "Default")
      (node (ref "JP2") (pin "4") (pinfunction "4_4") (pintype "passive"))
      (node (ref "R158") (pin "2") (pinfunction "2_2") (pintype "passive"))
      (node (ref "R63") (pin "1") (pinfunction "1_1") (pintype "passive"))
    )
    (net (code "13") (name "DAC_OUT_E") (class "Default")
      (node (ref "JP2") (pin "5") (pinfunction "5_5") (pintype "passive"))
      (node (ref "R159") (pin "2") (pinfunction "2_2") (pintype "passive"))
      (node (ref "R82") (pin "1") (pinfunction "1_1") (pintype "passive"))
    )
    (net (code "14") (name "DAC_OUT_F") (class "Default")
      (node (ref "JP2") (pin "6") (pinfunction "6_6") (pintype "passive"))
      (node (ref "R101") (pin "1") (pinfunction "1_1") (pintype "passive"))
      (node (ref "R160") (pin "2") (pinfunction "2_2") (pintype "passive"))
    )
    (net (code "15") (name "DAC_OUT_G") (class "Default")
      (node (ref "JP2") (pin "7") (pinfunction "7_7") (pintype "passive"))
      (node (ref "R120") (pin "1") (pinfunction "1_1") (pintype "passive"))
      (node (ref "R161") (pin "2") (pinfunction "2_2") (pintype "passive"))
    )
    (net (code "16") (name "DAC_OUT_H") (class "Default")
      (node (ref "JP2") (pin "8") (pinfunction "8_8") (pintype "passive"))
      (node (ref "R150") (pin "1") (pinfunction "1_1") (pintype "passive"))
      (node (ref "R162") (pin "2") (pinfunction "2_2") (pintype "passive"))
    )
    (net (code "17") (name "DAC_REF") (class "Default")
      (node (ref "IC5") (pin "3") (pinfunction "-IN_3") (pintype "input"))
      (node (ref "IC5") (pin "4") (pinfunction "OUT_4") (pintype "output"))
      (node (ref "U12") (pin "5") (pinfunction "+IN_B_5") (pintype "input"))
      (node (ref "U14") (pin "5") (pinfunction "+IN_B_5") (pintype "input"))
      (node (ref "U16") (pin "5") (pinfunction "+IN_B_5") (pintype "input"))
      (node (ref "U18") (pin "5") (pinfunction "+IN_B_5") (pintype "input"))
      (node (ref "U20") (pin "5") (pinfunction "+IN_B_5") (pintype "input"))
      (node (ref "U4") (pin "5") (pinfunction "+IN_B_5") (pintype "input"))
      (node (ref "U5") (pin "5") (pinfunction "+IN_B_5") (pintype "input"))
      (node (ref "U7") (pin "5") (pinfunction "+IN_B_5") (pintype "input"))
    )
    (net (code "18") (name "DAC_REF_0") (class "Default")
      (node (ref "R9") (pin "1") (pinfunction "1_1") (pintype "passive"))
      (node (ref "U2") (pin "3") (pinfunction "VREF_3") (pintype "input"))
      (node (ref "U4") (pin "6") (pinfunction "-IN_B_6") (pintype "input"))
      (node (ref "U4") (pin "7") (pinfunction "OUT_B_7") (pintype "output"))
    )
    (net (code "19") (name "DAC_REF_1") (class "Default")
      (node (ref "R26") (pin "1") (pinfunction "1_1") (pintype "passive"))
      (node (ref "U3") (pin "3") (pinfunction "VREF_3") (pintype "input"))
      (node (ref "U5") (pin "6") (pinfunction "-IN_B_6") (pintype "input"))
      (node (ref "U5") (pin "7") (pinfunction "OUT_B_7") (pintype "output"))
    )
    (net (code "20") (name "DAC_REF_2") (class "Default")
      (node (ref "R45") (pin "1") (pinfunction "1_1") (pintype "passive"))
      (node (ref "U6") (pin "3") (pinfunction "VREF_3") (pintype "input"))
      (node (ref "U7") (pin "6") (pinfunction "-IN_B_6") (pintype "input"))
      (node (ref "U7") (pin "7") (pinfunction "OUT_B_7") (pintype "output"))
    )
    (net (code "21") (name "DAC_REF_3") (class "Default")
      (node (ref "R64") (pin "1") (pinfunction "1_1") (pintype "passive"))
      (node (ref "U12") (pin "6") (pinfunction "-IN_B_6") (pintype "input"))
      (node (ref "U12") (pin "7") (pinfunction "OUT_B_7") (pintype "output"))
      (node (ref "U8") (pin "3") (pinfunction "VREF_3") (pintype "input"))
    )
    (net (code "22") (name "DAC_REF_4") (class "Default")
      (node (ref "R83") (pin "1") (pinfunction "1_1") (pintype "passive"))
      (node (ref "U13") (pin "3") (pinfunction "VREF_3") (pintype "input"))
      (node (ref "U14") (pin "6") (pinfunction "-IN_B_6") (pintype "input"))
      (node (ref "U14") (pin "7") (pinfunction "OUT_B_7") (pintype "output"))
    )
    (net (code "23") (name "DAC_REF_5") (class "Default")
      (node (ref "R102") (pin "1") (pinfunction "1_1") (pintype "passive"))
      (node (ref "U15") (pin "3") (pinfunction "VREF_3") (pintype "input"))
      (node (ref "U16") (pin "6") (pinfunction "-IN_B_6") (pintype "input"))
      (node (ref "U16") (pin "7") (pinfunction "OUT_B_7") (pintype "output"))
    )
    (net (code "24") (name "DAC_REF_6") (class "Default")
      (node (ref "R121") (pin "1") (pinfunction "1_1") (pintype "passive"))
      (node (ref "U17") (pin "3") (pinfunction "VREF_3") (pintype "input"))
      (node (ref "U18") (pin "6") (pinfunction "-IN_B_6") (pintype "input"))
      (node (ref "U18") (pin "7") (pinfunction "OUT_B_7") (pintype "output"))
    )
    (net (code "25") (name "DAC_REF_7") (class "Default")
      (node (ref "R151") (pin "1") (pinfunction "1_1") (pintype "passive"))
      (node (ref "U19") (pin "3") (pinfunction "VREF_3") (pintype "input"))
      (node (ref "U20") (pin "6") (pinfunction "-IN_B_6") (pintype "input"))
      (node (ref "U20") (pin "7") (pinfunction "OUT_B_7") (pintype "output"))
    )
    (net (code "26") (name "DAC_REF_OUT") (class "Default")
      (node (ref "C85") (pin "1") (pinfunction "1_1") (pintype "passive"))
      (node (ref "IC5") (pin "1") (pinfunction "+IN_1") (pintype "input"))
      (node (ref "U9") (pin "7") (pinfunction "REFIN/OUT_7") (pintype "bidirectional"))
    )
    (net (code "27") (name "DAC_SEL") (class "Default")
      (node (ref "IC4") (pin "15") (pinfunction "Y0_15") (pintype "output"))
      (node (ref "U9") (pin "9") (pinfunction "~{CS/LD}_9") (pintype "input"))
    )
    (net (code "28") (name "FAULT") (class "Default")
      (node (ref "IC2") (pin "6") (pinfunction "S_6") (pintype "input"))
      (node (ref "IC3") (pin "3") (pinfunction "O_3") (pintype "output"))
    )
    (net (code "29") (name "FAULT_BUFFER") (class "Default")
      (node (ref "IC3") (pin "1") (pinfunction "I0_1") (pintype "input"))
      (node (ref "IC6") (pin "14") (pinfunction "Y3_14") (pintype "tri_state"))
    )
    (net (code "30") (name "FAULT_OUT") (class "Default")
      (node (ref "IC6") (pin "6") (pinfunction "A3_6") (pintype "input"))
      (node (ref "U$1") (pin "PIN$9") (pinfunction "E/S_PIN$9") (pintype "bidirectional"))
      (node (ref "U$10") (pin "PIN$9") (pinfunction "E/S_PIN$9") (pintype "bidirectional"))
      (node (ref "U$11") (pin "PIN$9") (pinfunction "E/S_PIN$9") (pintype "bidirectional"))
      (node (ref "U$12") (pin "PIN$9") (pinfunction "E/S_PIN$9") (pintype "bidirectional"))
      (node (ref "U$13") (pin "PIN$9") (pinfunction "E/S_PIN$9") (pintype "bidirectional"))
      (node (ref "U$14") (pin "PIN$9") (pinfunction "E/S_PIN$9") (pintype "bidirectional"))
      (node (ref "U$15") (pin "PIN$9") (pinfunction "E/S_PIN$9") (pintype "bidirectional"))
      (node (ref "U$16") (pin "PIN$9") (pinfunction "E/S_PIN$9") (pintype "bidirectional"))
      (node (ref "U$2") (pin "PIN$9") (pinfunction "E/S_PIN$9") (pintype "bidirectional"))
      (node (ref "U$3") (pin "PIN$9") (pinfunction "E/S_PIN$9") (pintype "bidirectional"))
      (node (ref "U$4") (pin "PIN$9") (pinfunction "E/S_PIN$9") (pintype "bidirectional"))
      (node (ref "U$5") (pin "PIN$9") (pinfunction "E/S_PIN$9") (pintype "bidirectional"))
      (node (ref "U$6") (pin "PIN$9") (pinfunction "E/S_PIN$9") (pintype "bidirectional"))
      (node (ref "U$7") (pin "PIN$9") (pinfunction "E/S_PIN$9") (pintype "bidirectional"))
      (node (ref "U$8") (pin "PIN$9") (pinfunction "E/S_PIN$9") (pintype "bidirectional"))
      (node (ref "U$9") (pin "PIN$9") (pinfunction "E/S_PIN$9") (pintype "bidirectional"))
    )
    (net (code "31") (name "FAULT_READ") (class "Default")
      (node (ref "IC4") (pin "13") (pinfunction "Y2_13") (pintype "output"))
      (node (ref "IC6") (pin "19") (pinfunction "G_19") (pintype "input"))
    )
    (net (code "32") (name "FAULT_RESET") (class "Default")
      (node (ref "IC2") (pin "5") (pinfunction "R_5") (pintype "input"))
      (node (ref "IC3") (pin "2") (pinfunction "I1_2") (pintype "input"))
      (node (ref "IC4") (pin "12") (pinfunction "Y3_12") (pintype "output"))
    )
    (net (code "33") (name "FUNCTION_0") (class "Default")
      (node (ref "IC4") (pin "1") (pinfunction "A_1") (pintype "input"))
      (node (ref "R143") (pin "1") (pinfunction "1_1") (pintype "passive"))
      (node (ref "U025") (pin "14") (pinfunction "OUT1_14") (pintype "bidirectional"))
    )
    (net (code "34") (name "FUNCTION_0_I") (class "Default")
      (node (ref "R178") (pin "1") (pinfunction "1_1") (pintype "passive"))
      (node (ref "U030") (pin "3") (pinfunction "OUTB_3") (pintype "bidirectional"))
      (node (ref "U041") (pin "2") (pinfunction "C_2") (pintype "passive"))
    )
    (net (code "35") (name "FUNCTION_0_II") (class "Default")
      (node (ref "R178") (pin "2") (pinfunction "2_2") (pintype "passive"))
      (node (ref "U025") (pin "2") (pinfunction "CATH1_2") (pintype "bidirectional"))
      (node (ref "U041") (pin "1") (pinfunction "A_1") (pintype "passive"))
    )
    (net (code "36") (name "FUNCTION_0_Y") (class "Default")
      (node (ref "R138") (pin "1") (pinfunction "1_1") (pintype "passive"))
      (node (ref "U030") (pin "6") (pinfunction "INB1_6") (pintype "bidirectional"))
      (node (ref "X003") (pin "4") (pinfunction "4_4") (pintype "passive"))
    )
    (net (code "37") (name "FUNCTION_0_Z") (class "Default")
      (node (ref "R138") (pin "2") (pinfunction "2_2") (pintype "passive"))
      (node (ref "U030") (pin "5") (pinfunction "INB2_5") (pintype "bidirectional"))
      (node (ref "X003") (pin "5") (pinfunction "5_5") (pintype "passive"))
    )
    (net (code "38") (name "FUNCTION_1") (class "Default")
      (node (ref "IC4") (pin "2") (pinfunction "B_2") (pintype "input"))
      (node (ref "R144") (pin "1") (pinfunction "1_1") (pintype "passive"))
      (node (ref "U025") (pin "12") (pinfunction "OUT3_12") (pintype "bidirectional"))
    )
    (net (code "39") (name "FUNCTION_1_I") (class "Default")
      (node (ref "R179") (pin "1") (pinfunction "1_1") (pintype "passive"))
      (node (ref "U001") (pin "2") (pinfunction "OUTA_2") (pintype "bidirectional"))
      (node (ref "U042") (pin "2") (pinfunction "C_2") (pintype "passive"))
    )
    (net (code "40") (name "FUNCTION_1_II") (class "Default")
      (node (ref "R179") (pin "2") (pinfunction "2_2") (pintype "passive"))
      (node (ref "U025") (pin "6") (pinfunction "CATH3_6") (pintype "bidirectional"))
      (node (ref "U042") (pin "1") (pinfunction "A_1") (pintype "passive"))
    )
    (net (code "41") (name "FUNCTION_1_Y") (class "Default")
      (node (ref "R140") (pin "1") (pinfunction "1_1") (pintype "passive"))
      (node (ref "U001") (pin "8") (pinfunction "INA1_8") (pintype "bidirectional"))
      (node (ref "X003") (pin "6") (pinfunction "6_6") (pintype "passive"))
    )
    (net (code "42") (name "FUNCTION_1_Z") (class "Default")
      (node (ref "R140") (pin "2") (pinfunction "2_2") (pintype "passive"))
      (node (ref "U001") (pin "7") (pinfunction "INA2_7") (pintype "bidirectional"))
      (node (ref "X003") (pin "3") (pinfunction "3_3") (pintype "passive"))
    )
    (net (code "43") (name "GND") (class "Default")
      (node (ref "C10") (pin "2") (pinfunction "2_2") (pintype "passive"))
      (node (ref "C100") (pin "2") (pinfunction "2_2") (pintype "passive"))
      (node (ref "C101") (pin "2") (pinfunction "2_2") (pintype "passive"))
      (node (ref "C102") (pin "2") (pinfunction "2_2") (pintype "passive"))
      (node (ref "C103") (pin "2") (pinfunction "2_2") (pintype "passive"))
      (node (ref "C104") (pin "2") (pinfunction "2_2") (pintype "passive"))
      (node (ref "C107") (pin "2") (pinfunction "2_2") (pintype "passive"))
      (node (ref "C11") (pin "-") (pinfunction "-_-") (pintype "passive"))
      (node (ref "C110") (pin "2") (pinfunction "2_2") (pintype "passive"))
      (node (ref "C111") (pin "2") (pinfunction "2_2") (pintype "passive"))
      (node (ref "C112") (pin "2") (pinfunction "2_2") (pintype "passive"))
      (node (ref "C113") (pin "2") (pinfunction "2_2") (pintype "passive"))
      (node (ref "C114") (pin "2") (pinfunction "2_2") (pintype "passive"))
      (node (ref "C115") (pin "2") (pinfunction "2_2") (pintype "passive"))
      (node (ref "C116") (pin "2") (pinfunction "2_2") (pintype "passive"))
      (node (ref "C117") (pin "2") (pinfunction "2_2") (pintype "passive"))
      (node (ref "C118") (pin "2") (pinfunction "2_2") (pintype "passive"))
      (node (ref "C12") (pin "-") (pinfunction "-_-") (pintype "passive"))
      (node (ref "C128") (pin "2") (pinfunction "2_2") (pintype "passive"))
      (node (ref "C13") (pin "-") (pinfunction "-_-") (pintype "passive"))
      (node (ref "C132") (pin "2") (pinfunction "2_2") (pintype "passive"))
      (node (ref "C133") (pin "2") (pinfunction "2_2") (pintype "passive"))
      (node (ref "C134") (pin "2") (pinfunction "2_2") (pintype "passive"))
      (node (ref "C135") (pin "2") (pinfunction "2_2") (pintype "passive"))
      (node (ref "C14") (pin "-") (pinfunction "-_-") (pintype "passive"))
      (node (ref "C15") (pin "2") (pinfunction "2_2") (pintype "passive"))
      (node (ref "C19") (pin "2") (pinfunction "2_2") (pintype "passive"))
      (node (ref "C20") (pin "2") (pinfunction "2_2") (pintype "passive"))
      (node (ref "C21") (pin "2") (pinfunction "2_2") (pintype "passive"))
      (node (ref "C22") (pin "2") (pinfunction "2_2") (pintype "passive"))
      (node (ref "C23") (pin "2") (pinfunction "2_2") (pintype "passive"))
      (node (ref "C24") (pin "2") (pinfunction "2_2") (pintype "passive"))
      (node (ref "C25") (pin "2") (pinfunction "2_2") (pintype "passive"))
      (node (ref "C26") (pin "2") (pinfunction "2_2") (pintype "passive"))
      (node (ref "C30") (pin "2") (pinfunction "2_2") (pintype "passive"))
      (node (ref "C31") (pin "2") (pinfunction "2_2") (pintype "passive"))
      (node (ref "C32") (pin "2") (pinfunction "2_2") (pintype "passive"))
      (node (ref "C33") (pin "2") (pinfunction "2_2") (pintype "passive"))
      (node (ref "C34") (pin "2") (pinfunction "2_2") (pintype "passive"))
      (node (ref "C35") (pin "2") (pinfunction "2_2") (pintype "passive"))
      (node (ref "C36") (pin "2") (pinfunction "2_2") (pintype "passive"))
      (node (ref "C37") (pin "2") (pinfunction "2_2") (pintype "passive"))
      (node (ref "C4") (pin "2") (pinfunction "2_2") (pintype "passive"))
      (node (ref "C41") (pin "2") (pinfunction "2_2") (pintype "passive"))
      (node (ref "C42") (pin "2") (pinfunction "2_2") (pintype "passive"))
      (node (ref "C43") (pin "2") (pinfunction "2_2") (pintype "passive"))
      (node (ref "C44") (pin "2") (pinfunction "2_2") (pintype "passive"))
      (node (ref "C45") (pin "2") (pinfunction "2_2") (pintype "passive"))
      (node (ref "C46") (pin "2") (pinfunction "2_2") (pintype "passive"))
      (node (ref "C47") (pin "2") (pinfunction "2_2") (pintype "passive"))
      (node (ref "C48") (pin "2") (pinfunction "2_2") (pintype "passive"))
      (node (ref "C5") (pin "2") (pinfunction "2_2") (pintype "passive"))
      (node (ref "C52") (pin "2") (pinfunction "2_2") (pintype "passive"))
      (node (ref "C53") (pin "2") (pinfunction "2_2") (pintype "passive"))
      (node (ref "C54") (pin "2") (pinfunction "2_2") (pintype "passive"))
      (node (ref "C55") (pin "2") (pinfunction "2_2") (pintype "passive"))
      (node (ref "C56") (pin "2") (pinfunction "2_2") (pintype "passive"))
      (node (ref "C57") (pin "2") (pinfunction "2_2") (pintype "passive"))
      (node (ref "C58") (pin "2") (pinfunction "2_2") (pintype "passive"))
      (node (ref "C59") (pin "2") (pinfunction "2_2") (pintype "passive"))
      (node (ref "C6") (pin "2") (pinfunction "2_2") (pintype "passive"))
      (node (ref "C63") (pin "2") (pinfunction "2_2") (pintype "passive"))
      (node (ref "C64") (pin "2") (pinfunction "2_2") (pintype "passive"))
      (node (ref "C65") (pin "2") (pinfunction "2_2") (pintype "passive"))
      (node (ref "C66") (pin "2") (pinfunction "2_2") (pintype "passive"))
      (node (ref "C67") (pin "2") (pinfunction "2_2") (pintype "passive"))
      (node (ref "C68") (pin "2") (pinfunction "2_2") (pintype "passive"))
      (node (ref "C69") (pin "2") (pinfunction "2_2") (pintype "passive"))
      (node (ref "C7") (pin "2") (pinfunction "2_2") (pintype "passive"))
      (node (ref "C70") (pin "2") (pinfunction "2_2") (pintype "passive"))
      (node (ref "C74") (pin "2") (pinfunction "2_2") (pintype "passive"))
      (node (ref "C75") (pin "2") (pinfunction "2_2") (pintype "passive"))
      (node (ref "C76") (pin "2") (pinfunction "2_2") (pintype "passive"))
      (node (ref "C77") (pin "2") (pinfunction "2_2") (pintype "passive"))
      (node (ref "C78") (pin "2") (pinfunction "2_2") (pintype "passive"))
      (node (ref "C79") (pin "2") (pinfunction "2_2") (pintype "passive"))
      (node (ref "C8") (pin "2") (pinfunction "2_2") (pintype "passive"))
      (node (ref "C80") (pin "2") (pinfunction "2_2") (pintype "passive"))
      (node (ref "C81") (pin "2") (pinfunction "2_2") (pintype "passive"))
      (node (ref "C85") (pin "2") (pinfunction "2_2") (pintype "passive"))
      (node (ref "C86") (pin "2") (pinfunction "2_2") (pintype "passive"))
      (node (ref "C87") (pin "2") (pinfunction "2_2") (pintype "passive"))
      (node (ref "C88") (pin "2") (pinfunction "2_2") (pintype "passive"))
      (node (ref "C89") (pin "2") (pinfunction "2_2") (pintype "passive"))
      (node (ref "C9") (pin "2") (pinfunction "2_2") (pintype "passive"))
      (node (ref "C90") (pin "2") (pinfunction "2_2") (pintype "passive"))
      (node (ref "C91") (pin "2") (pinfunction "2_2") (pintype "passive"))
      (node (ref "C92") (pin "2") (pinfunction "2_2") (pintype "passive"))
      (node (ref "C93") (pin "2") (pinfunction "2_2") (pintype "passive"))
      (node (ref "C94") (pin "2") (pinfunction "2_2") (pintype "passive"))
      (node (ref "C95") (pin "2") (pinfunction "2_2") (pintype "passive"))
      (node (ref "C96") (pin "2") (pinfunction "2_2") (pintype "passive"))
      (node (ref "C97") (pin "2") (pinfunction "2_2") (pintype "passive"))
      (node (ref "C98") (pin "2") (pinfunction "2_2") (pintype "passive"))
      (node (ref "C99") (pin "2") (pinfunction "2_2") (pintype "passive"))
      (node (ref "IC1") (pin "3") (pinfunction "GND_3") (pintype "passive"))
      (node (ref "IC2") (pin "8") (pinfunction "GND_8") (pintype "power_in"))
      (node (ref "IC3") (pin "7") (pinfunction "GND_7") (pintype "power_in"))
      (node (ref "IC4") (pin "3") (pinfunction "C_3") (pintype "input"))
      (node (ref "IC4") (pin "5") (pinfunction "G2B_5") (pintype "input"))
      (node (ref "IC4") (pin "8") (pinfunction "GND_8") (pintype "power_in"))
      (node (ref "IC5") (pin "2") (pinfunction "V-_2") (pintype "power_in"))
      (node (ref "IC6") (pin "1") (pinfunction "G_1") (pintype "input"))
      (node (ref "IC6") (pin "10") (pinfunction "GND_10") (pintype "power_in"))
      (node (ref "JP3") (pin "1") (pinfunction "1_1") (pintype "passive"))
      (node (ref "JP3") (pin "2") (pinfunction "2_2") (pintype "passive"))
      (node (ref "JP4") (pin "1") (pinfunction "1_1") (pintype "passive"))
      (node (ref "JP4") (pin "2") (pinfunction "2_2") (pintype "passive"))
      (node (ref "JP5") (pin "1") (pinfunction "1_1") (pintype "passive"))
      (node (ref "JP6") (pin "1") (pinfunction "1_1") (pintype "passive"))
      (node (ref "P9") (pin "10") (pinfunction "P_10") (pintype "passive"))
      (node (ref "P9") (pin "3") (pinfunction "P_3") (pintype "passive"))
      (node (ref "P9") (pin "4") (pinfunction "P_4") (pintype "passive"))
      (node (ref "P9") (pin "5") (pinfunction "P_5") (pintype "passive"))
      (node (ref "P9") (pin "9") (pinfunction "P_9") (pintype "passive"))
      (node (ref "R10") (pin "2") (pinfunction "2_2") (pintype "passive"))
      (node (ref "R103") (pin "2") (pinfunction "2_2") (pintype "passive"))
      (node (ref "R106") (pin "1") (pinfunction "1_1") (pintype "passive"))
      (node (ref "R107") (pin "2") (pinfunction "2_2") (pintype "passive"))
      (node (ref "R111") (pin "1") (pinfunction "1_1") (pintype "passive"))
      (node (ref "R112") (pin "1") (pinfunction "1_1") (pintype "passive"))
      (node (ref "R122") (pin "2") (pinfunction "2_2") (pintype "passive"))
      (node (ref "R125") (pin "1") (pinfunction "1_1") (pintype "passive"))
      (node (ref "R126") (pin "2") (pinfunction "2_2") (pintype "passive"))
      (node (ref "R13") (pin "1") (pinfunction "1_1") (pintype "passive"))
      (node (ref "R130") (pin "1") (pinfunction "1_1") (pintype "passive"))
      (node (ref "R131") (pin "1") (pinfunction "1_1") (pintype "passive"))
      (node (ref "R14") (pin "2") (pinfunction "2_2") (pintype "passive"))
      (node (ref "R145") (pin "1") (pinfunction "1_1") (pintype "passive"))
      (node (ref "R146") (pin "1") (pinfunction "1_1") (pintype "passive"))
      (node (ref "R152") (pin "2") (pinfunction "2_2") (pintype "passive"))
      (node (ref "R164") (pin "1") (pinfunction "1_1") (pintype "passive"))
      (node (ref "R165") (pin "1") (pinfunction "1_1") (pintype "passive"))
      (node (ref "R166") (pin "2") (pinfunction "2_2") (pintype "passive"))
      (node (ref "R170") (pin "1") (pinfunction "1_1") (pintype "passive"))
      (node (ref "R171") (pin "1") (pinfunction "1_1") (pintype "passive"))
      (node (ref "R18") (pin "1") (pinfunction "1_1") (pintype "passive"))
      (node (ref "R27") (pin "2") (pinfunction "2_2") (pintype "passive"))
      (node (ref "R30") (pin "1") (pinfunction "1_1") (pintype "passive"))
      (node (ref "R31") (pin "2") (pinfunction "2_2") (pintype "passive"))
      (node (ref "R35") (pin "1") (pinfunction "1_1") (pintype "passive"))
      (node (ref "R36") (pin "1") (pinfunction "1_1") (pintype "passive"))
      (node (ref "R46") (pin "2") (pinfunction "2_2") (pintype "passive"))
      (node (ref "R49") (pin "1") (pinfunction "1_1") (pintype "passive"))
      (node (ref "R50") (pin "2") (pinfunction "2_2") (pintype "passive"))
      (node (ref "R54") (pin "1") (pinfunction "1_1") (pintype "passive"))
      (node (ref "R55") (pin "1") (pinfunction "1_1") (pintype "passive"))
      (node (ref "R65") (pin "2") (pinfunction "2_2") (pintype "passive"))
      (node (ref "R68") (pin "1") (pinfunction "1_1") (pintype "passive"))
      (node (ref "R69") (pin "2") (pinfunction "2_2") (pintype "passive"))
      (node (ref "R73") (pin "1") (pinfunction "1_1") (pintype "passive"))
      (node (ref "R74") (pin "1") (pinfunction "1_1") (pintype "passive"))
      (node (ref "R84") (pin "2") (pinfunction "2_2") (pintype "passive"))
      (node (ref "R87") (pin "1") (pinfunction "1_1") (pintype "passive"))
      (node (ref "R88") (pin "2") (pinfunction "2_2") (pintype "passive"))
      (node (ref "R92") (pin "1") (pinfunction "1_1") (pintype "passive"))
      (node (ref "R93") (pin "1") (pinfunction "1_1") (pintype "passive"))
      (node (ref "U$1") (pin "PIN$5") (pinfunction "V-_PIN$5") (pintype "bidirectional"))
      (node (ref "U$1") (pin "PIN$6") (pinfunction "REF_PIN$6") (pintype "bidirectional"))
      (node (ref "U$1") (pin "PIN$7") (pinfunction "V-_PIN$7") (pintype "bidirectional"))
      (node (ref "U$10") (pin "PIN$5") (pinfunction "V-_PIN$5") (pintype "bidirectional"))
      (node (ref "U$10") (pin "PIN$6") (pinfunction "REF_PIN$6") (pintype "bidirectional"))
      (node (ref "U$10") (pin "PIN$7") (pinfunction "V-_PIN$7") (pintype "bidirectional"))
      (node (ref "U$11") (pin "PIN$5") (pinfunction "V-_PIN$5") (pintype "bidirectional"))
      (node (ref "U$11") (pin "PIN$6") (pinfunction "REF_PIN$6") (pintype "bidirectional"))
      (node (ref "U$11") (pin "PIN$7") (pinfunction "V-_PIN$7") (pintype "bidirectional"))
      (node (ref "U$12") (pin "PIN$5") (pinfunction "V-_PIN$5") (pintype "bidirectional"))
      (node (ref "U$12") (pin "PIN$6") (pinfunction "REF_PIN$6") (pintype "bidirectional"))
      (node (ref "U$12") (pin "PIN$7") (pinfunction "V-_PIN$7") (pintype "bidirectional"))
      (node (ref "U$13") (pin "PIN$5") (pinfunction "V-_PIN$5") (pintype "bidirectional"))
      (node (ref "U$13") (pin "PIN$6") (pinfunction "REF_PIN$6") (pintype "bidirectional"))
      (node (ref "U$13") (pin "PIN$7") (pinfunction "V-_PIN$7") (pintype "bidirectional"))
      (node (ref "U$14") (pin "PIN$5") (pinfunction "V-_PIN$5") (pintype "bidirectional"))
      (node (ref "U$14") (pin "PIN$6") (pinfunction "REF_PIN$6") (pintype "bidirectional"))
      (node (ref "U$14") (pin "PIN$7") (pinfunction "V-_PIN$7") (pintype "bidirectional"))
      (node (ref "U$15") (pin "PIN$5") (pinfunction "V-_PIN$5") (pintype "bidirectional"))
      (node (ref "U$15") (pin "PIN$6") (pinfunction "REF_PIN$6") (pintype "bidirectional"))
      (node (ref "U$15") (pin "PIN$7") (pinfunction "V-_PIN$7") (pintype "bidirectional"))
      (node (ref "U$16") (pin "PIN$5") (pinfunction "V-_PIN$5") (pintype "bidirectional"))
      (node (ref "U$16") (pin "PIN$6") (pinfunction "REF_PIN$6") (pintype "bidirectional"))
      (node (ref "U$16") (pin "PIN$7") (pinfunction "V-_PIN$7") (pintype "bidirectional"))
      (node (ref "U$2") (pin "PIN$5") (pinfunction "V-_PIN$5") (pintype "bidirectional"))
      (node (ref "U$2") (pin "PIN$6") (pinfunction "REF_PIN$6") (pintype "bidirectional"))
      (node (ref "U$2") (pin "PIN$7") (pinfunction "V-_PIN$7") (pintype "bidirectional"))
      (node (ref "U$3") (pin "PIN$5") (pinfunction "V-_PIN$5") (pintype "bidirectional"))
      (node (ref "U$3") (pin "PIN$6") (pinfunction "REF_PIN$6") (pintype "bidirectional"))
      (node (ref "U$3") (pin "PIN$7") (pinfunction "V-_PIN$7") (pintype "bidirectional"))
      (node (ref "U$4") (pin "PIN$5") (pinfunction "V-_PIN$5") (pintype "bidirectional"))
      (node (ref "U$4") (pin "PIN$6") (pinfunction "REF_PIN$6") (pintype "bidirectional"))
      (node (ref "U$4") (pin "PIN$7") (pinfunction "V-_PIN$7") (pintype "bidirectional"))
      (node (ref "U$5") (pin "PIN$5") (pinfunction "V-_PIN$5") (pintype "bidirectional"))
      (node (ref "U$5") (pin "PIN$6") (pinfunction "REF_PIN$6") (pintype "bidirectional"))
      (node (ref "U$5") (pin "PIN$7") (pinfunction "V-_PIN$7") (pintype "bidirectional"))
      (node (ref "U$6") (pin "PIN$5") (pinfunction "V-_PIN$5") (pintype "bidirectional"))
      (node (ref "U$6") (pin "PIN$6") (pinfunction "REF_PIN$6") (pintype "bidirectional"))
      (node (ref "U$6") (pin "PIN$7") (pinfunction "V-_PIN$7") (pintype "bidirectional"))
      (node (ref "U$7") (pin "PIN$5") (pinfunction "V-_PIN$5") (pintype "bidirectional"))
      (node (ref "U$7") (pin "PIN$6") (pinfunction "REF_PIN$6") (pintype "bidirectional"))
      (node (ref "U$7") (pin "PIN$7") (pinfunction "V-_PIN$7") (pintype "bidirectional"))
      (node (ref "U$8") (pin "PIN$5") (pinfunction "V-_PIN$5") (pintype "bidirectional"))
      (node (ref "U$8") (pin "PIN$6") (pinfunction "REF_PIN$6") (pintype "bidirectional"))
      (node (ref "U$8") (pin "PIN$7") (pinfunction "V-_PIN$7") (pintype "bidirectional"))
      (node (ref "U$9") (pin "PIN$5") (pinfunction "V-_PIN$5") (pintype "bidirectional"))
      (node (ref "U$9") (pin "PIN$6") (pinfunction "REF_PIN$6") (pintype "bidirectional"))
      (node (ref "U$9") (pin "PIN$7") (pinfunction "V-_PIN$7") (pintype "bidirectional"))
      (node (ref "U025") (pin "16") (pinfunction "GND2_16") (pintype "bidirectional"))
      (node (ref "U025") (pin "9") (pinfunction "GND1_9") (pintype "bidirectional"))
      (node (ref "U026") (pin "13") (pinfunction "CATH3_13") (pintype "bidirectional"))
      (node (ref "U026") (pin "15") (pinfunction "CATH4_15") (pintype "bidirectional"))
      (node (ref "U026") (pin "9") (pinfunction "GND2_9") (pintype "bidirectional"))
      (node (ref "U10") (pin "15") (pinfunction "GND_15") (pintype "passive"))
      (node (ref "U12") (pin "4") (pinfunction "V-_4") (pintype "power_in"))
      (node (ref "U13") (pin "4") (pinfunction "GND_4") (pintype "passive"))
      (node (ref "U14") (pin "4") (pinfunction "V-_4") (pintype "power_in"))
      (node (ref "U15") (pin "4") (pinfunction "GND_4") (pintype "passive"))
      (node (ref "U16") (pin "4") (pinfunction "V-_4") (pintype "power_in"))
      (node (ref "U17") (pin "4") (pinfunction "GND_4") (pintype "passive"))
      (node (ref "U18") (pin "4") (pinfunction "V-_4") (pintype "power_in"))
      (node (ref "U19") (pin "4") (pinfunction "GND_4") (pintype "passive"))
      (node (ref "U2") (pin "4") (pinfunction "GND_4") (pintype "passive"))
      (node (ref "U20") (pin "4") (pinfunction "V-_4") (pintype "power_in"))
      (node (ref "U3") (pin "4") (pinfunction "GND_4") (pintype "passive"))
      (node (ref "U4") (pin "4") (pinfunction "V-_4") (pintype "power_in"))
      (node (ref "U5") (pin "4") (pinfunction "V-_4") (pintype "power_in"))
      (node (ref "U6") (pin "4") (pinfunction "GND_4") (pintype "passive"))
      (node (ref "U7") (pin "4") (pinfunction "V-_4") (pintype "power_in"))
      (node (ref "U8") (pin "4") (pinfunction "GND_4") (pintype "passive"))
      (node (ref "U9") (pin "1") (pinfunction "REFLO_1") (pintype "input"))
      (node (ref "U9") (pin "20") (pinfunction "GND_20") (pintype "passive"))
      (node (ref "U9") (pin "21") (pinfunction "EP_21") (pintype "passive"))
    )
    (net (code "44") (name "GND1") (class "Default")
      (node (ref "C105") (pin "2") (pinfunction "2_2") (pintype "passive"))
      (node (ref "C106") (pin "2") (pinfunction "2_2") (pintype "passive"))
      (node (ref "C108") (pin "2") (pinfunction "2_2") (pintype "passive"))
      (node (ref "C109") (pin "2") (pinfunction "2_2") (pintype "passive"))
      (node (ref "C119") (pin "2") (pinfunction "2_2") (pintype "passive"))
      (node (ref "C129") (pin "2") (pinfunction "2_2") (pintype "passive"))
      (node (ref "C130") (pin "2") (pinfunction "2_2") (pintype "passive"))
      (node (ref "C131") (pin "2") (pinfunction "2_2") (pintype "passive"))
      (node (ref "R139") (pin "1") (pinfunction "1_1") (pintype "passive"))
      (node (ref "U001") (pin "4") (pinfunction "GND_4") (pintype "bidirectional"))
      (node (ref "U011") (pin "4") (pinfunction "GND_4") (pintype "bidirectional"))
      (node (ref "U021") (pin "4") (pinfunction "GND_4") (pintype "bidirectional"))
      (node (ref "U026") (pin "1") (pinfunction "GND1_1") (pintype "bidirectional"))
      (node (ref "U030") (pin "4") (pinfunction "GND_4") (pintype "bidirectional"))
      (node (ref "X002") (pin "G1") (pinfunction "S_G1") (pintype "passive"))
      (node (ref "X002") (pin "G2") (pinfunction "S_G2") (pintype "passive"))
      (node (ref "X003") (pin "8") (pinfunction "8_8") (pintype "passive"))
      (node (ref "X003") (pin "G1") (pinfunction "S_G1") (pintype "passive"))
      (node (ref "X003") (pin "G2") (pinfunction "S_G2") (pintype "passive"))
    )
    (net (code "45") (name "ISENSE_0") (class "Default")
      (node (ref "JP1") (pin "1") (pinfunction "1_1") (pintype "passive"))
      (node (ref "U10") (pin "8") (pinfunction "CH7/COM_8") (pintype "input"))
      (node (ref "U4") (pin "1") (pinfunction "OUT_A_1") (pintype "output"))
      (node (ref "U4") (pin "2") (pinfunction "-IN_A_2") (pintype "input"))
    )
    (net (code "46") (name "ISENSE_0_B") (class "Default")
      (node (ref "R18") (pin "2") (pinfunction "2_2") (pintype "passive"))
      (node (ref "U2") (pin "6") (pinfunction "OUT_6") (pintype "output"))
      (node (ref "U4") (pin "3") (pinfunction "+IN_A_3") (pintype "input"))
    )
    (net (code "47") (name "ISENSE_1") (class "Default")
      (node (ref "JP1") (pin "2") (pinfunction "2_2") (pintype "passive"))
      (node (ref "U10") (pin "7") (pinfunction "CH6_7") (pintype "input"))
      (node (ref "U5") (pin "1") (pinfunction "OUT_A_1") (pintype "output"))
      (node (ref "U5") (pin "2") (pinfunction "-IN_A_2") (pintype "input"))
    )
    (net (code "48") (name "ISENSE_1_B") (class "Default")
      (node (ref "R35") (pin "2") (pinfunction "2_2") (pintype "passive"))
      (node (ref "U3") (pin "6") (pinfunction "OUT_6") (pintype "output"))
      (node (ref "U5") (pin "3") (pinfunction "+IN_A_3") (pintype "input"))
    )
    (net (code "49") (name "ISENSE_2") (class "Default")
      (node (ref "JP1") (pin "3") (pinfunction "3_3") (pintype "passive"))
      (node (ref "U10") (pin "6") (pinfunction "CH5_6") (pintype "input"))
      (node (ref "U7") (pin "1") (pinfunction "OUT_A_1") (pintype "output"))
      (node (ref "U7") (pin "2") (pinfunction "-IN_A_2") (pintype "input"))
    )
    (net (code "50") (name "ISENSE_2_B") (class "Default")
      (node (ref "R54") (pin "2") (pinfunction "2_2") (pintype "passive"))
      (node (ref "U6") (pin "6") (pinfunction "OUT_6") (pintype "output"))
      (node (ref "U7") (pin "3") (pinfunction "+IN_A_3") (pintype "input"))
    )
    (net (code "51") (name "ISENSE_3") (class "Default")
      (node (ref "JP1") (pin "4") (pinfunction "4_4") (pintype "passive"))
      (node (ref "U10") (pin "5") (pinfunction "CH4_5") (pintype "input"))
      (node (ref "U12") (pin "1") (pinfunction "OUT_A_1") (pintype "output"))
      (node (ref "U12") (pin "2") (pinfunction "-IN_A_2") (pintype "input"))
    )
    (net (code "52") (name "ISENSE_3_B") (class "Default")
      (node (ref "R73") (pin "2") (pinfunction "2_2") (pintype "passive"))
      (node (ref "U12") (pin "3") (pinfunction "+IN_A_3") (pintype "input"))
      (node (ref "U8") (pin "6") (pinfunction "OUT_6") (pintype "output"))
    )
    (net (code "53") (name "ISENSE_4") (class "Default")
      (node (ref "JP1") (pin "5") (pinfunction "5_5") (pintype "passive"))
      (node (ref "U10") (pin "4") (pinfunction "CH3_4") (pintype "input"))
      (node (ref "U14") (pin "1") (pinfunction "OUT_A_1") (pintype "output"))
      (node (ref "U14") (pin "2") (pinfunction "-IN_A_2") (pintype "input"))
    )
    (net (code "54") (name "ISENSE_4_B") (class "Default")
      (node (ref "R92") (pin "2") (pinfunction "2_2") (pintype "passive"))
      (node (ref "U13") (pin "6") (pinfunction "OUT_6") (pintype "output"))
      (node (ref "U14") (pin "3") (pinfunction "+IN_A_3") (pintype "input"))
    )
    (net (code "55") (name "ISENSE_5") (class "Default")
      (node (ref "JP1") (pin "6") (pinfunction "6_6") (pintype "passive"))
      (node (ref "U10") (pin "3") (pinfunction "CH2_3") (pintype "input"))
      (node (ref "U16") (pin "1") (pinfunction "OUT_A_1") (pintype "output"))
      (node (ref "U16") (pin "2") (pinfunction "-IN_A_2") (pintype "input"))
    )
    (net (code "56") (name "ISENSE_5_B") (class "Default")
      (node (ref "R111") (pin "2") (pinfunction "2_2") (pintype "passive"))
      (node (ref "U15") (pin "6") (pinfunction "OUT_6") (pintype "output"))
      (node (ref "U16") (pin "3") (pinfunction "+IN_A_3") (pintype "input"))
    )
    (net (code "57") (name "ISENSE_6") (class "Default")
      (node (ref "JP1") (pin "7") (pinfunction "7_7") (pintype "passive"))
      (node (ref "U10") (pin "2") (pinfunction "CH1_2") (pintype "input"))
      (node (ref "U18") (pin "1") (pinfunction "OUT_A_1") (pintype "output"))
      (node (ref "U18") (pin "2") (pinfunction "-IN_A_2") (pintype "input"))
    )
    (net (code "58") (name "ISENSE_6_B") (class "Default")
      (node (ref "R130") (pin "2") (pinfunction "2_2") (pintype "passive"))
      (node (ref "U17") (pin "6") (pinfunction "OUT_6") (pintype "output"))
      (node (ref "U18") (pin "3") (pinfunction "+IN_A_3") (pintype "input"))
    )
    (net (code "59") (name "ISENSE_7") (class "Default")
      (node (ref "JP1") (pin "8") (pinfunction "8_8") (pintype "passive"))
      (node (ref "U10") (pin "1") (pinfunction "CH0_1") (pintype "input"))
      (node (ref "U20") (pin "1") (pinfunction "OUT_A_1") (pintype "output"))
      (node (ref "U20") (pin "2") (pinfunction "-IN_A_2") (pintype "input"))
    )
    (net (code "60") (name "ISENSE_7_B") (class "Default")
      (node (ref "R170") (pin "2") (pinfunction "2_2") (pintype "passive"))
      (node (ref "U19") (pin "6") (pinfunction "OUT_6") (pintype "output"))
      (node (ref "U20") (pin "3") (pinfunction "+IN_A_3") (pintype "input"))
    )
    (net (code "61") (name "LATCHED_FAULT") (class "Default")
      (node (ref "IC2") (pin "7") (pinfunction "Q_7") (pintype "output"))
      (node (ref "IC6") (pin "17") (pinfunction "A4_17") (pintype "input"))
      (node (ref "IC6") (pin "4") (pinfunction "A2_4") (pintype "input"))
    )
    (net (code "62") (name "MISO") (class "Default")
      (node (ref "IC6") (pin "2") (pinfunction "A1_2") (pintype "input"))
      (node (ref "IC6") (pin "3") (pinfunction "Y4_3") (pintype "tri_state"))
      (node (ref "U10") (pin "13") (pinfunction "SDO_13") (pintype "output"))
    )
    (net (code "63") (name "MISO_A") (class "Default")
      (node (ref "U011") (pin "6") (pinfunction "OUTB1_6") (pintype "bidirectional"))
      (node (ref "X002") (pin "2") (pinfunction "2_2") (pintype "passive"))
    )
    (net (code "64") (name "MISO_B") (class "Default")
      (node (ref "U011") (pin "5") (pinfunction "OUTB2_5") (pintype "bidirectional"))
      (node (ref "X002") (pin "1") (pinfunction "1_1") (pintype "passive"))
    )
    (net (code "65") (name "MISO_BUFFER") (class "Default")
      (node (ref "IC6") (pin "18") (pinfunction "Y1_18") (pintype "tri_state"))
      (node (ref "R183") (pin "2") (pinfunction "2_2") (pintype "passive"))
      (node (ref "U046") (pin "2") (pinfunction "C_2") (pintype "passive"))
    )
    (net (code "66") (name "MISO_I") (class "Default")
      (node (ref "R173") (pin "1") (pinfunction "1_1") (pintype "passive"))
      (node (ref "U011") (pin "3") (pinfunction "INB_3") (pintype "bidirectional"))
      (node (ref "U026") (pin "2") (pinfunction "OUT4_2") (pintype "bidirectional"))
    )
    (net (code "67") (name "MISO_II") (class "Default")
      (node (ref "R183") (pin "1") (pinfunction "1_1") (pintype "passive"))
      (node (ref "U026") (pin "16") (pinfunction "AN4_16") (pintype "bidirectional"))
      (node (ref "U046") (pin "1") (pinfunction "A_1") (pintype "passive"))
    )
    (net (code "68") (name "MOSI") (class "Default")
      (node (ref "R176") (pin "1") (pinfunction "1_1") (pintype "passive"))
      (node (ref "U026") (pin "10") (pinfunction "OUT2_10") (pintype "bidirectional"))
      (node (ref "U10") (pin "14") (pinfunction "SDI_14") (pintype "input"))
      (node (ref "U9") (pin "11") (pinfunction "SDI_11") (pintype "input"))
    )
    (net (code "69") (name "MOSI_A") (class "Default")
      (node (ref "R000") (pin "1") (pinfunction "1_1") (pintype "passive"))
      (node (ref "U021") (pin "8") (pinfunction "INA1_8") (pintype "bidirectional"))
      (node (ref "X002") (pin "8") (pinfunction "8_8") (pintype "passive"))
    )
    (net (code "70") (name "MOSI_B") (class "Default")
      (node (ref "R000") (pin "2") (pinfunction "2_2") (pintype "passive"))
      (node (ref "U021") (pin "7") (pinfunction "INA2_7") (pintype "bidirectional"))
      (node (ref "X002") (pin "7") (pinfunction "7_7") (pintype "passive"))
    )
    (net (code "71") (name "MOSI_I") (class "Default")
      (node (ref "R181") (pin "1") (pinfunction "1_1") (pintype "passive"))
      (node (ref "U021") (pin "2") (pinfunction "OUTA_2") (pintype "bidirectional"))
      (node (ref "U044") (pin "2") (pinfunction "C_2") (pintype "passive"))
    )
    (net (code "72") (name "MOSI_II") (class "Default")
      (node (ref "R181") (pin "2") (pinfunction "2_2") (pintype "passive"))
      (node (ref "U026") (pin "8") (pinfunction "CATH2_8") (pintype "bidirectional"))
      (node (ref "U044") (pin "1") (pinfunction "A_1") (pintype "passive"))
    )
    (net (code "73") (name "NOT_LATCHED_FAULT") (class "Default")
      (node (ref "IC6") (pin "16") (pinfunction "Y2_16") (pintype "tri_state"))
      (node (ref "LED3") (pin "C") (pinfunction "C_C") (pintype "passive"))
      (node (ref "R184") (pin "1") (pinfunction "1_1") (pintype "passive"))
    )
    (net (code "74") (name "Net-(C1-Pad1)") (class "Default")
      (node (ref "C1") (pin "1") (pinfunction "1_1") (pintype "passive"))
      (node (ref "R2") (pin "2") (pinfunction "2_2") (pintype "passive"))
    )
    (net (code "75") (name "Net-(C2-Pad1)") (class "Default")
      (node (ref "C2") (pin "1") (pinfunction "1_1") (pintype "passive"))
      (node (ref "R5") (pin "2") (pinfunction "2_2") (pintype "passive"))
    )
    (net (code "76") (name "Net-(C3-Pad1)") (class "Default")
      (node (ref "C3") (pin "1") (pinfunction "1_1") (pintype "passive"))
      (node (ref "R6") (pin "1") (pinfunction "1_1") (pintype "passive"))
      (node (ref "R8") (pin "2") (pinfunction "2_2") (pintype "passive"))
    )
    (net (code "77") (name "Net-(C3-Pad2)") (class "Default")
      (node (ref "C3") (pin "2") (pinfunction "2_2") (pintype "passive"))
      (node (ref "R7") (pin "1") (pinfunction "1_1") (pintype "passive"))
      (node (ref "R9") (pin "2") (pinfunction "2_2") (pintype "passive"))
    )
    (net (code "78") (name "Net-(C16-Pad1)") (class "Default")
      (node (ref "C16") (pin "1") (pinfunction "1_1") (pintype "passive"))
      (node (ref "R19") (pin "2") (pinfunction "2_2") (pintype "passive"))
    )
    (net (code "79") (name "Net-(C17-Pad1)") (class "Default")
      (node (ref "C17") (pin "1") (pinfunction "1_1") (pintype "passive"))
      (node (ref "R22") (pin "2") (pinfunction "2_2") (pintype "passive"))
    )
    (net (code "80") (name "Net-(C18-Pad1)") (class "Default")
      (node (ref "C18") (pin "1") (pinfunction "1_1") (pintype "passive"))
      (node (ref "R23") (pin "1") (pinfunction "1_1") (pintype "passive"))
      (node (ref "R25") (pin "2") (pinfunction "2_2") (pintype "passive"))
    )
    (net (code "81") (name "Net-(C18-Pad2)") (class "Default")
      (node (ref "C18") (pin "2") (pinfunction "2_2") (pintype "passive"))
      (node (ref "R24") (pin "1") (pinfunction "1_1") (pintype "passive"))
      (node (ref "R26") (pin "2") (pinfunction "2_2") (pintype "passive"))
    )
    (net (code "82") (name "Net-(C27-Pad1)") (class "Default")
      (node (ref "C27") (pin "1") (pinfunction "1_1") (pintype "passive"))
      (node (ref "R38") (pin "2") (pinfunction "2_2") (pintype "passive"))
    )
    (net (code "83") (name "Net-(C28-Pad1)") (class "Default")
      (node (ref "C28") (pin "1") (pinfunction "1_1") (pintype "passive"))
      (node (ref "R41") (pin "2") (pinfunction "2_2") (pintype "passive"))
    )
    (net (code "84") (name "Net-(C29-Pad1)") (class "Default")
      (node (ref "C29") (pin "1") (pinfunction "1_1") (pintype "passive"))
      (node (ref "R42") (pin "1") (pinfunction "1_1") (pintype "passive"))
      (node (ref "R44") (pin "2") (pinfunction "2_2") (pintype "passive"))
    )
    (net (code "85") (name "Net-(C29-Pad2)") (class "Default")
      (node (ref "C29") (pin "2") (pinfunction "2_2") (pintype "passive"))
      (node (ref "R43") (pin "1") (pinfunction "1_1") (pintype "passive"))
      (node (ref "R45") (pin "2") (pinfunction "2_2") (pintype "passive"))
    )
    (net (code "86") (name "Net-(C38-Pad1)") (class "Default")
      (node (ref "C38") (pin "1") (pinfunction "1_1") (pintype "passive"))
      (node (ref "R57") (pin "2") (pinfunction "2_2") (pintype "passive"))
    )
    (net (code "87") (name "Net-(C39-Pad1)") (class "Default")
      (node (ref "C39") (pin "1") (pinfunction "1_1") (pintype "passive"))
      (node (ref "R60") (pin "2") (pinfunction "2_2") (pintype "passive"))
    )
    (net (code "88") (name "Net-(C40-Pad1)") (class "Default")
      (node (ref "C40") (pin "1") (pinfunction "1_1") (pintype "passive"))
      (node (ref "R61") (pin "1") (pinfunction "1_1") (pintype "passive"))
      (node (ref "R63") (pin "2") (pinfunction "2_2") (pintype "passive"))
    )
    (net (code "89") (name "Net-(C40-Pad2)") (class "Default")
      (node (ref "C40") (pin "2") (pinfunction "2_2") (pintype "passive"))
      (node (ref "R62") (pin "1") (pinfunction "1_1") (pintype "passive"))
      (node (ref "R64") (pin "2") (pinfunction "2_2") (pintype "passive"))
    )
    (net (code "90") (name "Net-(C49-Pad1)") (class "Default")
      (node (ref "C49") (pin "1") (pinfunction "1_1") (pintype "passive"))
      (node (ref "R76") (pin "2") (pinfunction "2_2") (pintype "passive"))
    )
    (net (code "91") (name "Net-(C50-Pad1)") (class "Default")
      (node (ref "C50") (pin "1") (pinfunction "1_1") (pintype "passive"))
      (node (ref "R79") (pin "2") (pinfunction "2_2") (pintype "passive"))
    )
    (net (code "92") (name "Net-(C51-Pad1)") (class "Default")
      (node (ref "C51") (pin "1") (pinfunction "1_1") (pintype "passive"))
      (node (ref "R80") (pin "1") (pinfunction "1_1") (pintype "passive"))
      (node (ref "R82") (pin "2") (pinfunction "2_2") (pintype "passive"))
    )
    (net (code "93") (name "Net-(C51-Pad2)") (class "Default")
      (node (ref "C51") (pin "2") (pinfunction "2_2") (pintype "passive"))
      (node (ref "R81") (pin "1") (pinfunction "1_1") (pintype "passive"))
      (node (ref "R83") (pin "2") (pinfunction "2_2") (pintype "passive"))
    )
    (net (code "94") (name "Net-(C60-Pad1)") (class "Default")
      (node (ref "C60") (pin "1") (pinfunction "1_1") (pintype "passive"))
      (node (ref "R95") (pin "2") (pinfunction "2_2") (pintype "passive"))
    )
    (net (code "95") (name "Net-(C61-Pad1)") (class "Default")
      (node (ref "C61") (pin "1") (pinfunction "1_1") (pintype "passive"))
      (node (ref "R98") (pin "2") (pinfunction "2_2") (pintype "passive"))
    )
    (net (code "96") (name "Net-(C62-Pad1)") (class "Default")
      (node (ref "C62") (pin "1") (pinfunction "1_1") (pintype "passive"))
      (node (ref "R101") (pin "2") (pinfunction "2_2") (pintype "passive"))
      (node (ref "R99") (pin "1") (pinfunction "1_1") (pintype "passive"))
    )
    (net (code "97") (name "Net-(C62-Pad2)") (class "Default")
      (node (ref "C62") (pin "2") (pinfunction "2_2") (pintype "passive"))
      (node (ref "R100") (pin "1") (pinfunction "1_1") (pintype "passive"))
      (node (ref "R102") (pin "2") (pinfunction "2_2") (pintype "passive"))
    )
    (net (code "98") (name "Net-(C71-Pad1)") (class "Default")
      (node (ref "C71") (pin "1") (pinfunction "1_1") (pintype "passive"))
      (node (ref "R114") (pin "2") (pinfunction "2_2") (pintype "passive"))
    )
    (net (code "99") (name "Net-(C72-Pad1)") (class "Default")
      (node (ref "C72") (pin "1") (pinfunction "1_1") (pintype "passive"))
      (node (ref "R117") (pin "2") (pinfunction "2_2") (pintype "passive"))
    )
    (net (code "100") (name "Net-(C73-Pad1)") (class "Default")
      (node (ref "C73") (pin "1") (pinfunction "1_1") (pintype "passive"))
      (node (ref "R118") (pin "1") (pinfunction "1_1") (pintype "passive"))
      (node (ref "R120") (pin "2") (pinfunction "2_2") (pintype "passive"))
    )
    (net (code "101") (name "Net-(C73-Pad2)") (class "Default")
      (node (ref "C73") (pin "2") (pinfunction "2_2") (pintype "passive"))
      (node (ref "R119") (pin "1") (pinfunction "1_1") (pintype "passive"))
      (node (ref "R121") (pin "2") (pinfunction "2_2") (pintype "passive"))
    )
    (net (code "102") (name "Net-(C82-Pad1)") (class "Default")
      (node (ref "C82") (pin "1") (pinfunction "1_1") (pintype "passive"))
      (node (ref "R133") (pin "2") (pinfunction "2_2") (pintype "passive"))
    )
    (net (code "103") (name "Net-(C83-Pad1)") (class "Default")
      (node (ref "C83") (pin "1") (pinfunction "1_1") (pintype "passive"))
      (node (ref "R136") (pin "2") (pinfunction "2_2") (pintype "passive"))
    )
    (net (code "104") (name "Net-(C84-Pad1)") (class "Default")
      (node (ref "C84") (pin "1") (pinfunction "1_1") (pintype "passive"))
      (node (ref "R148") (pin "1") (pinfunction "1_1") (pintype "passive"))
      (node (ref "R150") (pin "2") (pinfunction "2_2") (pintype "passive"))
    )
    (net (code "105") (name "Net-(C84-Pad2)") (class "Default")
      (node (ref "C84") (pin "2") (pinfunction "2_2") (pintype "passive"))
      (node (ref "R149") (pin "1") (pinfunction "1_1") (pintype "passive"))
      (node (ref "R151") (pin "2") (pinfunction "2_2") (pintype "passive"))
    )
    (net (code "106") (name "Net-(C120-Pad1)") (class "Default")
      (node (ref "C120") (pin "1") (pinfunction "1_1") (pintype "passive"))
      (node (ref "R186") (pin "2") (pinfunction "2_2") (pintype "passive"))
      (node (ref "R3") (pin "1") (pinfunction "1_1") (pintype "passive"))
    )
    (net (code "107") (name "Net-(C121-Pad1)") (class "Default")
      (node (ref "C121") (pin "1") (pinfunction "1_1") (pintype "passive"))
      (node (ref "R187") (pin "2") (pinfunction "2_2") (pintype "passive"))
      (node (ref "R20") (pin "1") (pinfunction "1_1") (pintype "passive"))
    )
    (net (code "108") (name "Net-(C122-Pad1)") (class "Default")
      (node (ref "C122") (pin "1") (pinfunction "1_1") (pintype "passive"))
      (node (ref "R185") (pin "2") (pinfunction "2_2") (pintype "passive"))
      (node (ref "R39") (pin "1") (pinfunction "1_1") (pintype "passive"))
    )
    (net (code "109") (name "Net-(C123-Pad1)") (class "Default")
      (node (ref "C123") (pin "1") (pinfunction "1_1") (pintype "passive"))
      (node (ref "R192") (pin "2") (pinfunction "2_2") (pintype "passive"))
      (node (ref "R58") (pin "1") (pinfunction "1_1") (pintype "passive"))
    )
    (net (code "110") (name "Net-(C124-Pad1)") (class "Default")
      (node (ref "C124") (pin "1") (pinfunction "1_1") (pintype "passive"))
      (node (ref "R188") (pin "2") (pinfunction "2_2") (pintype "passive"))
      (node (ref "R77") (pin "1") (pinfunction "1_1") (pintype "passive"))
    )
    (net (code "111") (name "Net-(C125-Pad1)") (class "Default")
      (node (ref "C125") (pin "1") (pinfunction "1_1") (pintype "passive"))
      (node (ref "R189") (pin "2") (pinfunction "2_2") (pintype "passive"))
      (node (ref "R96") (pin "1") (pinfunction "1_1") (pintype "passive"))
    )
    (net (code "112") (name "Net-(C126-Pad1)") (class "Default")
      (node (ref "C126") (pin "1") (pinfunction "1_1") (pintype "passive"))
      (node (ref "R115") (pin "1") (pinfunction "1_1") (pintype "passive"))
      (node (ref "R191") (pin "2") (pinfunction "2_2") (pintype "passive"))
    )
    (net (code "113") (name "Net-(C127-Pad1)") (class "Default")
      (node (ref "C127") (pin "1") (pinfunction "1_1") (pintype "passive"))
      (node (ref "R134") (pin "1") (pinfunction "1_1") (pintype "passive"))
      (node (ref "R190") (pin "2") (pinfunction "2_2") (pintype "passive"))
    )
    (net (code "114") (name "Net-(LED1-PadC)") (class "Default")
      (node (ref "LED1") (pin "C") (pinfunction "C_C") (pintype "passive"))
      (node (ref "R146") (pin "2") (pinfunction "2_2") (pintype "passive"))
    )
    (net (code "115") (name "Net-(LED2-PadC)") (class "Default")
      (node (ref "LED2") (pin "C") (pinfunction "C_C") (pintype "passive"))
      (node (ref "R145") (pin "2") (pinfunction "2_2") (pintype "passive"))
    )
    (net (code "116") (name "Net-(LED3-PadA)") (class "Default")
      (node (ref "LED3") (pin "A") (pinfunction "A_A") (pintype "passive"))
      (node (ref "R141") (pin "1") (pinfunction "1_1") (pintype "passive"))
    )
    (net (code "117") (name "Net-(P1A-P)") (class "Default")
      (node (ref "P1") (pin "1") (pinfunction "P_1") (pintype "passive"))
      (node (ref "R147") (pin "2") (pinfunction "2_2") (pintype "passive"))
      (node (ref "R193") (pin "2") (pinfunction "2_2") (pintype "passive"))
    )
    (net (code "118") (name "Net-(P1B-P)") (class "Default")
      (node (ref "P1") (pin "2") (pinfunction "P_2") (pintype "passive"))
      (node (ref "R11") (pin "2") (pinfunction "2_2") (pintype "passive"))
      (node (ref "R193") (pin "1") (pinfunction "1_1") (pintype "passive"))
      (node (ref "R4") (pin "1") (pinfunction "1_1") (pintype "passive"))
      (node (ref "R5") (pin "1") (pinfunction "1_1") (pintype "passive"))
      (node (ref "U2") (pin "1") (pinfunction "VIN-_1") (pintype "input"))
    )
    (net (code "119") (name "Net-(P2A-P)") (class "Default")
      (node (ref "P2") (pin "1") (pinfunction "P_1") (pintype "passive"))
      (node (ref "R194") (pin "2") (pinfunction "2_2") (pintype "passive"))
      (node (ref "R34") (pin "2") (pinfunction "2_2") (pintype "passive"))
    )
    (net (code "120") (name "Net-(P2B-P)") (class "Default")
      (node (ref "P2") (pin "2") (pinfunction "P_2") (pintype "passive"))
      (node (ref "R194") (pin "1") (pinfunction "1_1") (pintype "passive"))
      (node (ref "R21") (pin "1") (pinfunction "1_1") (pintype "passive"))
      (node (ref "R22") (pin "1") (pinfunction "1_1") (pintype "passive"))
      (node (ref "R28") (pin "2") (pinfunction "2_2") (pintype "passive"))
      (node (ref "U3") (pin "1") (pinfunction "VIN-_1") (pintype "input"))
    )
    (net (code "121") (name "Net-(P3A-P)") (class "Default")
      (node (ref "P3") (pin "1") (pinfunction "P_1") (pintype "passive"))
      (node (ref "R197") (pin "2") (pinfunction "2_2") (pintype "passive"))
      (node (ref "R53") (pin "2") (pinfunction "2_2") (pintype "passive"))
    )
    (net (code "122") (name "Net-(P3B-P)") (class "Default")
      (node (ref "P3") (pin "2") (pinfunction "P_2") (pintype "passive"))
      (node (ref "R197") (pin "1") (pinfunction "1_1") (pintype "passive"))
      (node (ref "R40") (pin "1") (pinfunction "1_1") (pintype "passive"))
      (node (ref "R41") (pin "1") (pinfunction "1_1") (pintype "passive"))
      (node (ref "R47") (pin "2") (pinfunction "2_2") (pintype "passive"))
      (node (ref "U6") (pin "1") (pinfunction "VIN-_1") (pintype "input"))
    )
    (net (code "123") (name "Net-(P4A-P)") (class "Default")
      (node (ref "P4") (pin "1") (pinfunction "P_1") (pintype "passive"))
      (node (ref "R198") (pin "2") (pinfunction "2_2") (pintype "passive"))
      (node (ref "R72") (pin "2") (pinfunction "2_2") (pintype "passive"))
    )
    (net (code "124") (name "Net-(P4B-P)") (class "Default")
      (node (ref "P4") (pin "2") (pinfunction "P_2") (pintype "passive"))
      (node (ref "R198") (pin "1") (pinfunction "1_1") (pintype "passive"))
      (node (ref "R59") (pin "1") (pinfunction "1_1") (pintype "passive"))
      (node (ref "R60") (pin "1") (pinfunction "1_1") (pintype "passive"))
      (node (ref "R66") (pin "2") (pinfunction "2_2") (pintype "passive"))
      (node (ref "U8") (pin "1") (pinfunction "VIN-_1") (pintype "input"))
    )
    (net (code "125") (name "Net-(P5A-P)") (class "Default")
      (node (ref "P5") (pin "1") (pinfunction "P_1") (pintype "passive"))
      (node (ref "R195") (pin "2") (pinfunction "2_2") (pintype "passive"))
      (node (ref "R91") (pin "2") (pinfunction "2_2") (pintype "passive"))
    )
    (net (code "126") (name "Net-(P5B-P)") (class "Default")
      (node (ref "P5") (pin "2") (pinfunction "P_2") (pintype "passive"))
      (node (ref "R195") (pin "1") (pinfunction "1_1") (pintype "passive"))
      (node (ref "R78") (pin "1") (pinfunction "1_1") (pintype "passive"))
      (node (ref "R79") (pin "1") (pinfunction "1_1") (pintype "passive"))
      (node (ref "R85") (pin "2") (pinfunction "2_2") (pintype "passive"))
      (node (ref "U13") (pin "1") (pinfunction "VIN-_1") (pintype "input"))
    )
    (net (code "127") (name "Net-(P6A-P)") (class "Default")
      (node (ref "P6") (pin "1") (pinfunction "P_1") (pintype "passive"))
      (node (ref "R110") (pin "2") (pinfunction "2_2") (pintype "passive"))
      (node (ref "R196") (pin "2") (pinfunction "2_2") (pintype "passive"))
    )
    (net (code "128") (name "Net-(P6B-P)") (class "Default")
      (node (ref "P6") (pin "2") (pinfunction "P_2") (pintype "passive"))
      (node (ref "R104") (pin "2") (pinfunction "2_2") (pintype "passive"))
      (node (ref "R196") (pin "1") (pinfunction "1_1") (pintype "passive"))
      (node (ref "R97") (pin "1") (pinfunction "1_1") (pintype "passive"))
      (node (ref "R98") (pin "1") (pinfunction "1_1") (pintype "passive"))
      (node (ref "U15") (pin "1") (pinfunction "VIN-_1") (pintype "input"))
    )
    (net (code "129") (name "Net-(P7A-P)") (class "Default")
      (node (ref "P7") (pin "1") (pinfunction "P_1") (pintype "passive"))
      (node (ref "R129") (pin "2") (pinfunction "2_2") (pintype "passive"))
      (node (ref "R199") (pin "2") (pinfunction "2_2") (pintype "passive"))
    )
    (net (code "130") (name "Net-(P7B-P)") (class "Default")
      (node (ref "P7") (pin "2") (pinfunction "P_2") (pintype "passive"))
      (node (ref "R116") (pin "1") (pinfunction "1_1") (pintype "passive"))
      (node (ref "R117") (pin "1") (pinfunction "1_1") (pintype "passive"))
      (node (ref "R123") (pin "2") (pinfunction "2_2") (pintype "passive"))
      (node (ref "R199") (pin "1") (pinfunction "1_1") (pintype "passive"))
      (node (ref "U17") (pin "1") (pinfunction "VIN-_1") (pintype "input"))
    )
    (net (code "131") (name "Net-(P8A-P)") (class "Default")
      (node (ref "P8") (pin "1") (pinfunction "P_1") (pintype "passive"))
      (node (ref "R169") (pin "2") (pinfunction "2_2") (pintype "passive"))
      (node (ref "R200") (pin "2") (pinfunction "2_2") (pintype "passive"))
    )
    (net (code "132") (name "Net-(P8B-P)") (class "Default")
      (node (ref "P8") (pin "2") (pinfunction "P_2") (pintype "passive"))
      (node (ref "R135") (pin "1") (pinfunction "1_1") (pintype "passive"))
      (node (ref "R136") (pin "1") (pinfunction "1_1") (pintype "passive"))
      (node (ref "R153") (pin "2") (pinfunction "2_2") (pintype "passive"))
      (node (ref "R200") (pin "1") (pinfunction "1_1") (pintype "passive"))
      (node (ref "U19") (pin "1") (pinfunction "VIN-_1") (pintype "input"))
    )
    (net (code "133") (name "Net-(P9A-P)") (class "Default")
      (node (ref "P9") (pin "1") (pinfunction "P_1") (pintype "passive"))
      (node (ref "P9") (pin "2") (pinfunction "P_2") (pintype "passive"))
      (node (ref "P9") (pin "6") (pinfunction "P_6") (pintype "passive"))
      (node (ref "P9") (pin "7") (pinfunction "P_7") (pintype "passive"))
      (node (ref "P9") (pin "8") (pinfunction "P_8") (pintype "passive"))
      (node (ref "U031") (pin "P$1") (pinfunction "1_P$1") (pintype "passive"))
    )
    (net (code "134") (name "Net-(P10A-P)") (class "Default")
      (node (ref "C128") (pin "1") (pinfunction "1_1") (pintype "passive"))
      (node (ref "C132") (pin "1") (pinfunction "1_1") (pintype "passive"))
      (node (ref "C133") (pin "1") (pinfunction "1_1") (pintype "passive"))
      (node (ref "C134") (pin "1") (pinfunction "1_1") (pintype "passive"))
      (node (ref "C135") (pin "1") (pinfunction "1_1") (pintype "passive"))
      (node (ref "P10") (pin "1") (pinfunction "P_1") (pintype "passive"))
      (node (ref "P10") (pin "2") (pinfunction "P_2") (pintype "passive"))
    )
    (net (code "135") (name "Net-(R33-Pad2)") (class "Default")
      (node (ref "R33") (pin "2") (pinfunction "2_2") (pintype "passive"))
      (node (ref "R34") (pin "1") (pinfunction "1_1") (pintype "passive"))
      (node (ref "U$4") (pin "PIN$1") (pinfunction "OUT_PIN$1") (pintype "bidirectional"))
      (node (ref "U$4") (pin "PIN$2") (pinfunction "OUT_PIN$2") (pintype "bidirectional"))
    )
    (net (code "136") (name "Net-(R52-Pad2)") (class "Default")
      (node (ref "R52") (pin "2") (pinfunction "2_2") (pintype "passive"))
      (node (ref "R53") (pin "1") (pinfunction "1_1") (pintype "passive"))
      (node (ref "U$6") (pin "PIN$1") (pinfunction "OUT_PIN$1") (pintype "bidirectional"))
      (node (ref "U$6") (pin "PIN$2") (pinfunction "OUT_PIN$2") (pintype "bidirectional"))
    )
    (net (code "137") (name "Net-(R71-Pad2)") (class "Default")
      (node (ref "R71") (pin "2") (pinfunction "2_2") (pintype "passive"))
      (node (ref "R72") (pin "1") (pinfunction "1_1") (pintype "passive"))
      (node (ref "U$8") (pin "PIN$1") (pinfunction "OUT_PIN$1") (pintype "bidirectional"))
      (node (ref "U$8") (pin "PIN$2") (pinfunction "OUT_PIN$2") (pintype "bidirectional"))
    )
    (net (code "138") (name "Net-(R90-Pad2)") (class "Default")
      (node (ref "R90") (pin "2") (pinfunction "2_2") (pintype "passive"))
      (node (ref "R91") (pin "1") (pinfunction "1_1") (pintype "passive"))
      (node (ref "U$10") (pin "PIN$1") (pinfunction "OUT_PIN$1") (pintype "bidirectional"))
      (node (ref "U$10") (pin "PIN$2") (pinfunction "OUT_PIN$2") (pintype "bidirectional"))
    )
    (net (code "139") (name "Net-(R109-Pad2)") (class "Default")
      (node (ref "R109") (pin "2") (pinfunction "2_2") (pintype "passive"))
      (node (ref "R110") (pin "1") (pinfunction "1_1") (pintype "passive"))
      (node (ref "U$12") (pin "PIN$1") (pinfunction "OUT_PIN$1") (pintype "bidirectional"))
      (node (ref "U$12") (pin "PIN$2") (pinfunction "OUT_PIN$2") (pintype "bidirectional"))
    )
    (net (code "140") (name "Net-(R128-Pad2)") (class "Default")
      (node (ref "R128") (pin "2") (pinfunction "2_2") (pintype "passive"))
      (node (ref "R129") (pin "1") (pinfunction "1_1") (pintype "passive"))
      (node (ref "U$14") (pin "PIN$1") (pinfunction "OUT_PIN$1") (pintype "bidirectional"))
      (node (ref "U$14") (pin "PIN$2") (pinfunction "OUT_PIN$2") (pintype "bidirectional"))
    )
    (net (code "141") (name "Net-(R147-Pad1)") (class "Default")
      (node (ref "R147") (pin "1") (pinfunction "1_1") (pintype "passive"))
      (node (ref "R16") (pin "2") (pinfunction "2_2") (pintype "passive"))
      (node (ref "U$2") (pin "PIN$1") (pinfunction "OUT_PIN$1") (pintype "bidirectional"))
      (node (ref "U$2") (pin "PIN$2") (pinfunction "OUT_PIN$2") (pintype "bidirectional"))
    )
    (net (code "142") (name "Net-(R168-Pad2)") (class "Default")
      (node (ref "R168") (pin "2") (pinfunction "2_2") (pintype "passive"))
      (node (ref "R169") (pin "1") (pinfunction "1_1") (pintype "passive"))
      (node (ref "U$16") (pin "PIN$1") (pinfunction "OUT_PIN$1") (pintype "bidirectional"))
      (node (ref "U$16") (pin "PIN$2") (pinfunction "OUT_PIN$2") (pintype "bidirectional"))
    )
    (net (code "143") (name "Net-(U$1-+)") (class "Default")
      (node (ref "C120") (pin "2") (pinfunction "2_2") (pintype "passive"))
      (node (ref "C2") (pin "2") (pinfunction "2_2") (pintype "passive"))
      (node (ref "R186") (pin "1") (pinfunction "1_1") (pintype "passive"))
      (node (ref "R4") (pin "2") (pinfunction "2_2") (pintype "passive"))
      (node (ref "R7") (pin "2") (pinfunction "2_2") (pintype "passive"))
      (node (ref "U$1") (pin "PIN$4") (pinfunction "+_PIN$4") (pintype "bidirectional"))
    )
    (net (code "144") (name "Net-(U$1--)") (class "Default")
      (node (ref "R1") (pin "1") (pinfunction "1_1") (pintype "passive"))
      (node (ref "R2") (pin "1") (pinfunction "1_1") (pintype "passive"))
      (node (ref "R3") (pin "2") (pinfunction "2_2") (pintype "passive"))
      (node (ref "R6") (pin "2") (pinfunction "2_2") (pintype "passive"))
      (node (ref "U$1") (pin "PIN$3") (pinfunction "-_PIN$3") (pintype "bidirectional"))
    )
    (net (code "145") (name "Net-(U$1-ILIM)") (class "Default")
      (node (ref "R10") (pin "1") (pinfunction "1_1") (pintype "passive"))
      (node (ref "U$1") (pin "PIN$8") (pinfunction "ILIM_PIN$8") (pintype "bidirectional"))
    )
    (net (code "146") (name "Net-(U$2-+)") (class "Default")
      (node (ref "R12") (pin "2") (pinfunction "2_2") (pintype "passive"))
      (node (ref "R13") (pin "2") (pinfunction "2_2") (pintype "passive"))
      (node (ref "U$2") (pin "PIN$4") (pinfunction "+_PIN$4") (pintype "bidirectional"))
    )
    (net (code "147") (name "Net-(U$2--)") (class "Default")
      (node (ref "R15") (pin "2") (pinfunction "2_2") (pintype "passive"))
      (node (ref "R16") (pin "1") (pinfunction "1_1") (pintype "passive"))
      (node (ref "U$2") (pin "PIN$3") (pinfunction "-_PIN$3") (pintype "bidirectional"))
    )
    (net (code "148") (name "Net-(U$2-ILIM)") (class "Default")
      (node (ref "R14") (pin "1") (pinfunction "1_1") (pintype "passive"))
      (node (ref "U$2") (pin "PIN$8") (pinfunction "ILIM_PIN$8") (pintype "bidirectional"))
    )
    (net (code "149") (name "Net-(U$3-+)") (class "Default")
      (node (ref "C121") (pin "2") (pinfunction "2_2") (pintype "passive"))
      (node (ref "C17") (pin "2") (pinfunction "2_2") (pintype "passive"))
      (node (ref "R187") (pin "1") (pinfunction "1_1") (pintype "passive"))
      (node (ref "R21") (pin "2") (pinfunction "2_2") (pintype "passive"))
      (node (ref "R24") (pin "2") (pinfunction "2_2") (pintype "passive"))
      (node (ref "U$3") (pin "PIN$4") (pinfunction "+_PIN$4") (pintype "bidirectional"))
    )
    (net (code "150") (name "Net-(U$3--)") (class "Default")
      (node (ref "R17") (pin "1") (pinfunction "1_1") (pintype "passive"))
      (node (ref "R19") (pin "1") (pinfunction "1_1") (pintype "passive"))
      (node (ref "R20") (pin "2") (pinfunction "2_2") (pintype "passive"))
      (node (ref "R23") (pin "2") (pinfunction "2_2") (pintype "passive"))
      (node (ref "U$3") (pin "PIN$3") (pinfunction "-_PIN$3") (pintype "bidirectional"))
    )
    (net (code "151") (name "Net-(U$3-ILIM)") (class "Default")
      (node (ref "R27") (pin "1") (pinfunction "1_1") (pintype "passive"))
      (node (ref "U$3") (pin "PIN$8") (pinfunction "ILIM_PIN$8") (pintype "bidirectional"))
    )
    (net (code "152") (name "Net-(U$4-+)") (class "Default")
      (node (ref "R29") (pin "2") (pinfunction "2_2") (pintype "passive"))
      (node (ref "R30") (pin "2") (pinfunction "2_2") (pintype "passive"))
      (node (ref "U$4") (pin "PIN$4") (pinfunction "+_PIN$4") (pintype "bidirectional"))
    )
    (net (code "153") (name "Net-(U$4--)") (class "Default")
      (node (ref "R32") (pin "2") (pinfunction "2_2") (pintype "passive"))
      (node (ref "R33") (pin "1") (pinfunction "1_1") (pintype "passive"))
      (node (ref "U$4") (pin "PIN$3") (pinfunction "-_PIN$3") (pintype "bidirectional"))
    )
    (net (code "154") (name "Net-(U$4-ILIM)") (class "Default")
      (node (ref "R31") (pin "1") (pinfunction "1_1") (pintype "passive"))
      (node (ref "U$4") (pin "PIN$8") (pinfunction "ILIM_PIN$8") (pintype "bidirectional"))
    )
    (net (code "155") (name "Net-(U$5-+)") (class "Default")
      (node (ref "C122") (pin "2") (pinfunction "2_2") (pintype "passive"))
      (node (ref "C28") (pin "2") (pinfunction "2_2") (pintype "passive"))
      (node (ref "R185") (pin "1") (pinfunction "1_1") (pintype "passive"))
      (node (ref "R40") (pin "2") (pinfunction "2_2") (pintype "passive"))
      (node (ref "R43") (pin "2") (pinfunction "2_2") (pintype "passive"))
      (node (ref "U$5") (pin "PIN$4") (pinfunction "+_PIN$4") (pintype "bidirectional"))
    )
    (net (code "156") (name "Net-(U$5--)") (class "Default")
      (node (ref "R37") (pin "1") (pinfunction "1_1") (pintype "passive"))
      (node (ref "R38") (pin "1") (pinfunction "1_1") (pintype "passive"))
      (node (ref "R39") (pin "2") (pinfunction "2_2") (pintype "passive"))
      (node (ref "R42") (pin "2") (pinfunction "2_2") (pintype "passive"))
      (node (ref "U$5") (pin "PIN$3") (pinfunction "-_PIN$3") (pintype "bidirectional"))
    )
    (net (code "157") (name "Net-(U$5-ILIM)") (class "Default")
      (node (ref "R46") (pin "1") (pinfunction "1_1") (pintype "passive"))
      (node (ref "U$5") (pin "PIN$8") (pinfunction "ILIM_PIN$8") (pintype "bidirectional"))
    )
    (net (code "158") (name "Net-(U$6-+)") (class "Default")
      (node (ref "R48") (pin "2") (pinfunction "2_2") (pintype "passive"))
      (node (ref "R49") (pin "2") (pinfunction "2_2") (pintype "passive"))
      (node (ref "U$6") (pin "PIN$4") (pinfunction "+_PIN$4") (pintype "bidirectional"))
    )
    (net (code "159") (name "Net-(U$6--)") (class "Default")
      (node (ref "R51") (pin "2") (pinfunction "2_2") (pintype "passive"))
      (node (ref "R52") (pin "1") (pinfunction "1_1") (pintype "passive"))
      (node (ref "U$6") (pin "PIN$3") (pinfunction "-_PIN$3") (pintype "bidirectional"))
    )
    (net (code "160") (name "Net-(U$6-ILIM)") (class "Default")
      (node (ref "R50") (pin "1") (pinfunction "1_1") (pintype "passive"))
      (node (ref "U$6") (pin "PIN$8") (pinfunction "ILIM_PIN$8") (pintype "bidirectional"))
    )
    (net (code "161") (name "Net-(U$7-+)") (class "Default")
      (node (ref "C123") (pin "2") (pinfunction "2_2") (pintype "passive"))
      (node (ref "C39") (pin "2") (pinfunction "2_2") (pintype "passive"))
      (node (ref "R192") (pin "1") (pinfunction "1_1") (pintype "passive"))
      (node (ref "R59") (pin "2") (pinfunction "2_2") (pintype "passive"))
      (node (ref "R62") (pin "2") (pinfunction "2_2") (pintype "passive"))
      (node (ref "U$7") (pin "PIN$4") (pinfunction "+_PIN$4") (pintype "bidirectional"))
    )
    (net (code "162") (name "Net-(U$7--)") (class "Default")
      (node (ref "R56") (pin "1") (pinfunction "1_1") (pintype "passive"))
      (node (ref "R57") (pin "1") (pinfunction "1_1") (pintype "passive"))
      (node (ref "R58") (pin "2") (pinfunction "2_2") (pintype "passive"))
      (node (ref "R61") (pin "2") (pinfunction "2_2") (pintype "passive"))
      (node (ref "U$7") (pin "PIN$3") (pinfunction "-_PIN$3") (pintype "bidirectional"))
    )
    (net (code "163") (name "Net-(U$7-ILIM)") (class "Default")
      (node (ref "R65") (pin "1") (pinfunction "1_1") (pintype "passive"))
      (node (ref "U$7") (pin "PIN$8") (pinfunction "ILIM_PIN$8") (pintype "bidirectional"))
    )
    (net (code "164") (name "Net-(U$8-+)") (class "Default")
      (node (ref "R67") (pin "2") (pinfunction "2_2") (pintype "passive"))
      (node (ref "R68") (pin "2") (pinfunction "2_2") (pintype "passive"))
      (node (ref "U$8") (pin "PIN$4") (pinfunction "+_PIN$4") (pintype "bidirectional"))
    )
    (net (code "165") (name "Net-(U$8--)") (class "Default")
      (node (ref "R70") (pin "2") (pinfunction "2_2") (pintype "passive"))
      (node (ref "R71") (pin "1") (pinfunction "1_1") (pintype "passive"))
      (node (ref "U$8") (pin "PIN$3") (pinfunction "-_PIN$3") (pintype "bidirectional"))
    )
    (net (code "166") (name "Net-(U$8-ILIM)") (class "Default")
      (node (ref "R69") (pin "1") (pinfunction "1_1") (pintype "passive"))
      (node (ref "U$8") (pin "PIN$8") (pinfunction "ILIM_PIN$8") (pintype "bidirectional"))
    )
    (net (code "167") (name "Net-(U$9-+)") (class "Default")
      (node (ref "C124") (pin "2") (pinfunction "2_2") (pintype "passive"))
      (node (ref "C50") (pin "2") (pinfunction "2_2") (pintype "passive"))
      (node (ref "R188") (pin "1") (pinfunction "1_1") (pintype "passive"))
      (node (ref "R78") (pin "2") (pinfunction "2_2") (pintype "passive"))
      (node (ref "R81") (pin "2") (pinfunction "2_2") (pintype "passive"))
      (node (ref "U$9") (pin "PIN$4") (pinfunction "+_PIN$4") (pintype "bidirectional"))
    )
    (net (code "168") (name "Net-(U$9--)") (class "Default")
      (node (ref "R75") (pin "1") (pinfunction "1_1") (pintype "passive"))
      (node (ref "R76") (pin "1") (pinfunction "1_1") (pintype "passive"))
      (node (ref "R77") (pin "2") (pinfunction "2_2") (pintype "passive"))
      (node (ref "R80") (pin "2") (pinfunction "2_2") (pintype "passive"))
      (node (ref "U$9") (pin "PIN$3") (pinfunction "-_PIN$3") (pintype "bidirectional"))
    )
    (net (code "169") (name "Net-(U$9-ILIM)") (class "Default")
      (node (ref "R84") (pin "1") (pinfunction "1_1") (pintype "passive"))
      (node (ref "U$9") (pin "PIN$8") (pinfunction "ILIM_PIN$8") (pintype "bidirectional"))
    )
    (net (code "170") (name "Net-(U$10-+)") (class "Default")
      (node (ref "R86") (pin "2") (pinfunction "2_2") (pintype "passive"))
      (node (ref "R87") (pin "2") (pinfunction "2_2") (pintype "passive"))
      (node (ref "U$10") (pin "PIN$4") (pinfunction "+_PIN$4") (pintype "bidirectional"))
    )
    (net (code "171") (name "Net-(U$10--)") (class "Default")
      (node (ref "R89") (pin "2") (pinfunction "2_2") (pintype "passive"))
      (node (ref "R90") (pin "1") (pinfunction "1_1") (pintype "passive"))
      (node (ref "U$10") (pin "PIN$3") (pinfunction "-_PIN$3") (pintype "bidirectional"))
    )
    (net (code "172") (name "Net-(U$10-ILIM)") (class "Default")
      (node (ref "R88") (pin "1") (pinfunction "1_1") (pintype "passive"))
      (node (ref "U$10") (pin "PIN$8") (pinfunction "ILIM_PIN$8") (pintype "bidirectional"))
    )
    (net (code "173") (name "Net-(U$11-+)") (class "Default")
      (node (ref "C125") (pin "2") (pinfunction "2_2") (pintype "passive"))
      (node (ref "C61") (pin "2") (pinfunction "2_2") (pintype "passive"))
      (node (ref "R100") (pin "2") (pinfunction "2_2") (pintype "passive"))
      (node (ref "R189") (pin "1") (pinfunction "1_1") (pintype "passive"))
      (node (ref "R97") (pin "2") (pinfunction "2_2") (pintype "passive"))
      (node (ref "U$11") (pin "PIN$4") (pinfunction "+_PIN$4") (pintype "bidirectional"))
    )
    (net (code "174") (name "Net-(U$11--)") (class "Default")
      (node (ref "R94") (pin "1") (pinfunction "1_1") (pintype "passive"))
      (node (ref "R95") (pin "1") (pinfunction "1_1") (pintype "passive"))
      (node (ref "R96") (pin "2") (pinfunction "2_2") (pintype "passive"))
      (node (ref "R99") (pin "2") (pinfunction "2_2") (pintype "passive"))
      (node (ref "U$11") (pin "PIN$3") (pinfunction "-_PIN$3") (pintype "bidirectional"))
    )
    (net (code "175") (name "Net-(U$11-ILIM)") (class "Default")
      (node (ref "R103") (pin "1") (pinfunction "1_1") (pintype "passive"))
      (node (ref "U$11") (pin "PIN$8") (pinfunction "ILIM_PIN$8") (pintype "bidirectional"))
    )
    (net (code "176") (name "Net-(U$12-+)") (class "Default")
      (node (ref "R105") (pin "2") (pinfunction "2_2") (pintype "passive"))
      (node (ref "R106") (pin "2") (pinfunction "2_2") (pintype "passive"))
      (node (ref "U$12") (pin "PIN$4") (pinfunction "+_PIN$4") (pintype "bidirectional"))
    )
    (net (code "177") (name "Net-(U$12--)") (class "Default")
      (node (ref "R108") (pin "2") (pinfunction "2_2") (pintype "passive"))
      (node (ref "R109") (pin "1") (pinfunction "1_1") (pintype "passive"))
      (node (ref "U$12") (pin "PIN$3") (pinfunction "-_PIN$3") (pintype "bidirectional"))
    )
    (net (code "178") (name "Net-(U$12-ILIM)") (class "Default")
      (node (ref "R107") (pin "1") (pinfunction "1_1") (pintype "passive"))
      (node (ref "U$12") (pin "PIN$8") (pinfunction "ILIM_PIN$8") (pintype "bidirectional"))
    )
    (net (code "179") (name "Net-(U$13-+)") (class "Default")
      (node (ref "C126") (pin "2") (pinfunction "2_2") (pintype "passive"))
      (node (ref "C72") (pin "2") (pinfunction "2_2") (pintype "passive"))
      (node (ref "R116") (pin "2") (pinfunction "2_2") (pintype "passive"))
      (node (ref "R119") (pin "2") (pinfunction "2_2") (pintype "passive"))
      (node (ref "R191") (pin "1") (pinfunction "1_1") (pintype "passive"))
      (node (ref "U$13") (pin "PIN$4") (pinfunction "+_PIN$4") (pintype "bidirectional"))
    )
    (net (code "180") (name "Net-(U$13--)") (class "Default")
      (node (ref "R113") (pin "1") (pinfunction "1_1") (pintype "passive"))
      (node (ref "R114") (pin "1") (pinfunction "1_1") (pintype "passive"))
      (node (ref "R115") (pin "2") (pinfunction "2_2") (pintype "passive"))
      (node (ref "R118") (pin "2") (pinfunction "2_2") (pintype "passive"))
      (node (ref "U$13") (pin "PIN$3") (pinfunction "-_PIN$3") (pintype "bidirectional"))
    )
    (net (code "181") (name "Net-(U$13-ILIM)") (class "Default")
      (node (ref "R122") (pin "1") (pinfunction "1_1") (pintype "passive"))
      (node (ref "U$13") (pin "PIN$8") (pinfunction "ILIM_PIN$8") (pintype "bidirectional"))
    )
    (net (code "182") (name "Net-(U$14-+)") (class "Default")
      (node (ref "R124") (pin "2") (pinfunction "2_2") (pintype "passive"))
      (node (ref "R125") (pin "2") (pinfunction "2_2") (pintype "passive"))
      (node (ref "U$14") (pin "PIN$4") (pinfunction "+_PIN$4") (pintype "bidirectional"))
    )
    (net (code "183") (name "Net-(U$14--)") (class "Default")
      (node (ref "R127") (pin "2") (pinfunction "2_2") (pintype "passive"))
      (node (ref "R128") (pin "1") (pinfunction "1_1") (pintype "passive"))
      (node (ref "U$14") (pin "PIN$3") (pinfunction "-_PIN$3") (pintype "bidirectional"))
    )
    (net (code "184") (name "Net-(U$14-ILIM)") (class "Default")
      (node (ref "R126") (pin "1") (pinfunction "1_1") (pintype "passive"))
      (node (ref "U$14") (pin "PIN$8") (pinfunction "ILIM_PIN$8") (pintype "bidirectional"))
    )
    (net (code "185") (name "Net-(U$15-+)") (class "Default")
      (node (ref "C127") (pin "2") (pinfunction "2_2") (pintype "passive"))
      (node (ref "C83") (pin "2") (pinfunction "2_2") (pintype "passive"))
      (node (ref "R135") (pin "2") (pinfunction "2_2") (pintype "passive"))
      (node (ref "R149") (pin "2") (pinfunction "2_2") (pintype "passive"))
      (node (ref "R190") (pin "1") (pinfunction "1_1") (pintype "passive"))
      (node (ref "U$15") (pin "PIN$4") (pinfunction "+_PIN$4") (pintype "bidirectional"))
    )
    (net (code "186") (name "Net-(U$15--)") (class "Default")
      (node (ref "R132") (pin "1") (pinfunction "1_1") (pintype "passive"))
      (node (ref "R133") (pin "1") (pinfunction "1_1") (pintype "passive"))
      (node (ref "R134") (pin "2") (pinfunction "2_2") (pintype "passive"))
      (node (ref "R148") (pin "2") (pinfunction "2_2") (pintype "passive"))
      (node (ref "U$15") (pin "PIN$3") (pinfunction "-_PIN$3") (pintype "bidirectional"))
    )
    (net (code "187") (name "Net-(U$15-ILIM)") (class "Default")
      (node (ref "R152") (pin "1") (pinfunction "1_1") (pintype "passive"))
      (node (ref "U$15") (pin "PIN$8") (pinfunction "ILIM_PIN$8") (pintype "bidirectional"))
    )
    (net (code "188") (name "Net-(U$16-+)") (class "Default")
      (node (ref "R154") (pin "2") (pinfunction "2_2") (pintype "passive"))
      (node (ref "R165") (pin "2") (pinfunction "2_2") (pintype "passive"))
      (node (ref "U$16") (pin "PIN$4") (pinfunction "+_PIN$4") (pintype "bidirectional"))
    )
    (net (code "189") (name "Net-(U$16--)") (class "Default")
      (node (ref "R167") (pin "2") (pinfunction "2_2") (pintype "passive"))
      (node (ref "R168") (pin "1") (pinfunction "1_1") (pintype "passive"))
      (node (ref "U$16") (pin "PIN$3") (pinfunction "-_PIN$3") (pintype "bidirectional"))
    )
    (net (code "190") (name "Net-(U$16-ILIM)") (class "Default")
      (node (ref "R166") (pin "1") (pinfunction "1_1") (pintype "passive"))
      (node (ref "U$16") (pin "PIN$8") (pinfunction "ILIM_PIN$8") (pintype "bidirectional"))
    )
    (net (code "191") (name "Net-(U2-ROS)") (class "Default")
      (node (ref "R164") (pin "2") (pinfunction "2_2") (pintype "passive"))
      (node (ref "U2") (pin "5") (pinfunction "ROS_5") (pintype "input"))
    )
    (net (code "192") (name "Net-(U2-VIN+)") (class "Default")
      (node (ref "C1") (pin "2") (pinfunction "2_2") (pintype "passive"))
      (node (ref "R1") (pin "2") (pinfunction "2_2") (pintype "passive"))
      (node (ref "R11") (pin "1") (pinfunction "1_1") (pintype "passive"))
      (node (ref "R15") (pin "1") (pinfunction "1_1") (pintype "passive"))
      (node (ref "U$1") (pin "PIN$1") (pinfunction "OUT_PIN$1") (pintype "bidirectional"))
      (node (ref "U$1") (pin "PIN$2") (pinfunction "OUT_PIN$2") (pintype "bidirectional"))
      (node (ref "U2") (pin "2") (pinfunction "VIN+_2") (pintype "input"))
    )
    (net (code "193") (name "Net-(U3-ROS)") (class "Default")
      (node (ref "R36") (pin "2") (pinfunction "2_2") (pintype "passive"))
      (node (ref "U3") (pin "5") (pinfunction "ROS_5") (pintype "input"))
    )
    (net (code "194") (name "Net-(U3-VIN+)") (class "Default")
      (node (ref "C16") (pin "2") (pinfunction "2_2") (pintype "passive"))
      (node (ref "R17") (pin "2") (pinfunction "2_2") (pintype "passive"))
      (node (ref "R28") (pin "1") (pinfunction "1_1") (pintype "passive"))
      (node (ref "R32") (pin "1") (pinfunction "1_1") (pintype "passive"))
      (node (ref "U$3") (pin "PIN$1") (pinfunction "OUT_PIN$1") (pintype "bidirectional"))
      (node (ref "U$3") (pin "PIN$2") (pinfunction "OUT_PIN$2") (pintype "bidirectional"))
      (node (ref "U3") (pin "2") (pinfunction "VIN+_2") (pintype "input"))
    )
    (net (code "195") (name "Net-(U6-ROS)") (class "Default")
      (node (ref "R55") (pin "2") (pinfunction "2_2") (pintype "passive"))
      (node (ref "U6") (pin "5") (pinfunction "ROS_5") (pintype "input"))
    )
    (net (code "196") (name "Net-(U6-VIN+)") (class "Default")
      (node (ref "C27") (pin "2") (pinfunction "2_2") (pintype "passive"))
      (node (ref "R37") (pin "2") (pinfunction "2_2") (pintype "passive"))
      (node (ref "R47") (pin "1") (pinfunction "1_1") (pintype "passive"))
      (node (ref "R51") (pin "1") (pinfunction "1_1") (pintype "passive"))
      (node (ref "U$5") (pin "PIN$1") (pinfunction "OUT_PIN$1") (pintype "bidirectional"))
      (node (ref "U$5") (pin "PIN$2") (pinfunction "OUT_PIN$2") (pintype "bidirectional"))
      (node (ref "U6") (pin "2") (pinfunction "VIN+_2") (pintype "input"))
    )
    (net (code "197") (name "Net-(U8-ROS)") (class "Default")
      (node (ref "R74") (pin "2") (pinfunction "2_2") (pintype "passive"))
      (node (ref "U8") (pin "5") (pinfunction "ROS_5") (pintype "input"))
    )
    (net (code "198") (name "Net-(U8-VIN+)") (class "Default")
      (node (ref "C38") (pin "2") (pinfunction "2_2") (pintype "passive"))
      (node (ref "R56") (pin "2") (pinfunction "2_2") (pintype "passive"))
      (node (ref "R66") (pin "1") (pinfunction "1_1") (pintype "passive"))
      (node (ref "R70") (pin "1") (pinfunction "1_1") (pintype "passive"))
      (node (ref "U$7") (pin "PIN$1") (pinfunction "OUT_PIN$1") (pintype "bidirectional"))
      (node (ref "U$7") (pin "PIN$2") (pinfunction "OUT_PIN$2") (pintype "bidirectional"))
      (node (ref "U8") (pin "2") (pinfunction "VIN+_2") (pintype "input"))
    )
    (net (code "199") (name "Net-(U9-REFCOMP)") (class "Default")
      (node (ref "C86") (pin "1") (pinfunction "1_1") (pintype "passive"))
      (node (ref "U9") (pin "4") (pinfunction "REFCOMP_4") (pintype "passive"))
    )
    (net (code "200") (name "Net-(U9-VOUTA)") (class "Default")
      (node (ref "R158") (pin "1") (pinfunction "1_1") (pintype "passive"))
      (node (ref "U9") (pin "2") (pinfunction "VOUTA_2") (pintype "output"))
    )
    (net (code "201") (name "Net-(U9-VOUTB)") (class "Default")
      (node (ref "R157") (pin "1") (pinfunction "1_1") (pintype "passive"))
      (node (ref "U9") (pin "3") (pinfunction "VOUTB_3") (pintype "output"))
    )
    (net (code "202") (name "Net-(U9-VOUTC)") (class "Default")
      (node (ref "R156") (pin "1") (pinfunction "1_1") (pintype "passive"))
      (node (ref "U9") (pin "5") (pinfunction "VOUTC_5") (pintype "output"))
    )
    (net (code "203") (name "Net-(U9-VOUTD)") (class "Default")
      (node (ref "R155") (pin "1") (pinfunction "1_1") (pintype "passive"))
      (node (ref "U9") (pin "6") (pinfunction "VOUTD_6") (pintype "output"))
    )
    (net (code "204") (name "Net-(U9-VOUTE)") (class "Default")
      (node (ref "R162") (pin "1") (pinfunction "1_1") (pintype "passive"))
      (node (ref "U9") (pin "15") (pinfunction "VOUTE_15") (pintype "output"))
    )
    (net (code "205") (name "Net-(U9-VOUTF)") (class "Default")
      (node (ref "R161") (pin "1") (pinfunction "1_1") (pintype "passive"))
      (node (ref "U9") (pin "16") (pinfunction "VOUTF_16") (pintype "output"))
    )
    (net (code "206") (name "Net-(U9-VOUTG)") (class "Default")
      (node (ref "R160") (pin "1") (pinfunction "1_1") (pintype "passive"))
      (node (ref "U9") (pin "17") (pinfunction "VOUTG_17") (pintype "output"))
    )
    (net (code "207") (name "Net-(U9-VOUTH)") (class "Default")
      (node (ref "R159") (pin "1") (pinfunction "1_1") (pintype "passive"))
      (node (ref "U9") (pin "18") (pinfunction "VOUTH_18") (pintype "output"))
    )
    (net (code "208") (name "Net-(U9-~{CLR})") (class "Default")
      (node (ref "R163") (pin "2") (pinfunction "2_2") (pintype "passive"))
      (node (ref "R184") (pin "2") (pinfunction "2_2") (pintype "passive"))
      (node (ref "U9") (pin "13") (pinfunction "~{CLR}_13") (pintype "input"))
    )
    (net (code "209") (name "Net-(U10-REFCOMP)") (class "Default")
      (node (ref "C87") (pin "1") (pinfunction "1_1") (pintype "passive"))
      (node (ref "C95") (pin "1") (pinfunction "1_1") (pintype "passive"))
      (node (ref "U10") (pin "9") (pinfunction "REFCOMP_9") (pintype "output"))
    )
    (net (code "210") (name "Net-(U10-VREF)") (class "Default")
      (node (ref "C88") (pin "1") (pinfunction "1_1") (pintype "passive"))
      (node (ref "C96") (pin "1") (pinfunction "1_1") (pintype "passive"))
      (node (ref "U10") (pin "10") (pinfunction "VREF_10") (pintype "output"))
    )
    (net (code "211") (name "Net-(U13-ROS)") (class "Default")
      (node (ref "R93") (pin "2") (pinfunction "2_2") (pintype "passive"))
      (node (ref "U13") (pin "5") (pinfunction "ROS_5") (pintype "input"))
    )
    (net (code "212") (name "Net-(U13-VIN+)") (class "Default")
      (node (ref "C49") (pin "2") (pinfunction "2_2") (pintype "passive"))
      (node (ref "R75") (pin "2") (pinfunction "2_2") (pintype "passive"))
      (node (ref "R85") (pin "1") (pinfunction "1_1") (pintype "passive"))
      (node (ref "R89") (pin "1") (pinfunction "1_1") (pintype "passive"))
      (node (ref "U$9") (pin "PIN$1") (pinfunction "OUT_PIN$1") (pintype "bidirectional"))
      (node (ref "U$9") (pin "PIN$2") (pinfunction "OUT_PIN$2") (pintype "bidirectional"))
      (node (ref "U13") (pin "2") (pinfunction "VIN+_2") (pintype "input"))
    )
    (net (code "213") (name "Net-(U15-ROS)") (class "Default")
      (node (ref "R112") (pin "2") (pinfunction "2_2") (pintype "passive"))
      (node (ref "U15") (pin "5") (pinfunction "ROS_5") (pintype "input"))
    )
    (net (code "214") (name "Net-(U15-VIN+)") (class "Default")
      (node (ref "C60") (pin "2") (pinfunction "2_2") (pintype "passive"))
      (node (ref "R104") (pin "1") (pinfunction "1_1") (pintype "passive"))
      (node (ref "R108") (pin "1") (pinfunction "1_1") (pintype "passive"))
      (node (ref "R94") (pin "2") (pinfunction "2_2") (pintype "passive"))
      (node (ref "U$11") (pin "PIN$1") (pinfunction "OUT_PIN$1") (pintype "bidirectional"))
      (node (ref "U$11") (pin "PIN$2") (pinfunction "OUT_PIN$2") (pintype "bidirectional"))
      (node (ref "U15") (pin "2") (pinfunction "VIN+_2") (pintype "input"))
    )
    (net (code "215") (name "Net-(U17-ROS)") (class "Default")
      (node (ref "R131") (pin "2") (pinfunction "2_2") (pintype "passive"))
      (node (ref "U17") (pin "5") (pinfunction "ROS_5") (pintype "input"))
    )
    (net (code "216") (name "Net-(U17-VIN+)") (class "Default")
      (node (ref "C71") (pin "2") (pinfunction "2_2") (pintype "passive"))
      (node (ref "R113") (pin "2") (pinfunction "2_2") (pintype "passive"))
      (node (ref "R123") (pin "1") (pinfunction "1_1") (pintype "passive"))
      (node (ref "R127") (pin "1") (pinfunction "1_1") (pintype "passive"))
      (node (ref "U$13") (pin "PIN$1") (pinfunction "OUT_PIN$1") (pintype "bidirectional"))
      (node (ref "U$13") (pin "PIN$2") (pinfunction "OUT_PIN$2") (pintype "bidirectional"))
      (node (ref "U17") (pin "2") (pinfunction "VIN+_2") (pintype "input"))
    )
    (net (code "217") (name "Net-(U19-ROS)") (class "Default")
      (node (ref "R171") (pin "2") (pinfunction "2_2") (pintype "passive"))
      (node (ref "U19") (pin "5") (pinfunction "ROS_5") (pintype "input"))
    )
    (net (code "218") (name "Net-(U19-VIN+)") (class "Default")
      (node (ref "C82") (pin "2") (pinfunction "2_2") (pintype "passive"))
      (node (ref "R132") (pin "2") (pinfunction "2_2") (pintype "passive"))
      (node (ref "R153") (pin "1") (pinfunction "1_1") (pintype "passive"))
      (node (ref "R167") (pin "1") (pinfunction "1_1") (pintype "passive"))
      (node (ref "U$15") (pin "PIN$1") (pinfunction "OUT_PIN$1") (pintype "bidirectional"))
      (node (ref "U$15") (pin "PIN$2") (pinfunction "OUT_PIN$2") (pintype "bidirectional"))
      (node (ref "U19") (pin "2") (pinfunction "VIN+_2") (pintype "input"))
    )
    (net (code "219") (name "SCK_MS") (class "Default")
      (node (ref "IC6") (pin "8") (pinfunction "A4_8") (pintype "input"))
      (node (ref "R175") (pin "1") (pinfunction "1_1") (pintype "passive"))
      (node (ref "U026") (pin "11") (pinfunction "OUT1_11") (pintype "bidirectional"))
      (node (ref "U10") (pin "12") (pinfunction "SCK_12") (pintype "input"))
      (node (ref "U9") (pin "10") (pinfunction "SCK_10") (pintype "input"))
    )
    (net (code "220") (name "SCK_MS_A") (class "Default")
      (node (ref "R172") (pin "1") (pinfunction "1_1") (pintype "passive"))
      (node (ref "U021") (pin "6") (pinfunction "INB1_6") (pintype "bidirectional"))
      (node (ref "X002") (pin "5") (pinfunction "5_5") (pintype "passive"))
    )
    (net (code "221") (name "SCK_MS_B") (class "Default")
      (node (ref "R172") (pin "2") (pinfunction "2_2") (pintype "passive"))
      (node (ref "U021") (pin "5") (pinfunction "INB2_5") (pintype "bidirectional"))
      (node (ref "X002") (pin "4") (pinfunction "4_4") (pintype "passive"))
    )
    (net (code "222") (name "SCK_MS_I") (class "Default")
      (node (ref "R180") (pin "1") (pinfunction "1_1") (pintype "passive"))
      (node (ref "U021") (pin "3") (pinfunction "OUTB_3") (pintype "bidirectional"))
      (node (ref "U043") (pin "2") (pinfunction "C_2") (pintype "passive"))
    )
    (net (code "223") (name "SCK_MS_II") (class "Default")
      (node (ref "R180") (pin "2") (pinfunction "2_2") (pintype "passive"))
      (node (ref "U026") (pin "6") (pinfunction "CATH1_6") (pintype "bidirectional"))
      (node (ref "U043") (pin "1") (pinfunction "A_1") (pintype "passive"))
    )
    (net (code "224") (name "SCK_SM") (class "Default")
      (node (ref "IC6") (pin "12") (pinfunction "Y4_12") (pintype "tri_state"))
      (node (ref "R182") (pin "2") (pinfunction "2_2") (pintype "passive"))
      (node (ref "U045") (pin "2") (pinfunction "C_2") (pintype "passive"))
    )
    (net (code "225") (name "SCK_SM_A") (class "Default")
      (node (ref "U011") (pin "8") (pinfunction "OUTA1_8") (pintype "bidirectional"))
      (node (ref "X002") (pin "6") (pinfunction "6_6") (pintype "passive"))
    )
    (net (code "226") (name "SCK_SM_B") (class "Default")
      (node (ref "U011") (pin "7") (pinfunction "OUTA2_7") (pintype "bidirectional"))
      (node (ref "X002") (pin "3") (pinfunction "3_3") (pintype "passive"))
    )
    (net (code "227") (name "SCK_SM_I") (class "Default")
      (node (ref "R174") (pin "1") (pinfunction "1_1") (pintype "passive"))
      (node (ref "U011") (pin "2") (pinfunction "INA_2") (pintype "bidirectional"))
      (node (ref "U026") (pin "3") (pinfunction "OUT3_3") (pintype "bidirectional"))
    )
    (net (code "228") (name "SCK_SM_II") (class "Default")
      (node (ref "R182") (pin "1") (pinfunction "1_1") (pintype "passive"))
      (node (ref "U026") (pin "14") (pinfunction "AN3_14") (pintype "bidirectional"))
      (node (ref "U045") (pin "1") (pinfunction "A_1") (pintype "passive"))
    )
    (net (code "229") (name "VCC") (class "Default")
      (node (ref "C100") (pin "1") (pinfunction "1_1") (pintype "passive"))
      (node (ref "C11") (pin "+") (pinfunction "+_+") (pintype "passive"))
      (node (ref "C110") (pin "1") (pinfunction "1_1") (pintype "passive"))
      (node (ref "C111") (pin "1") (pinfunction "1_1") (pintype "passive"))
      (node (ref "C112") (pin "1") (pinfunction "1_1") (pintype "passive"))
      (node (ref "C113") (pin "1") (pinfunction "1_1") (pintype "passive"))
      (node (ref "C114") (pin "1") (pinfunction "1_1") (pintype "passive"))
      (node (ref "C115") (pin "1") (pinfunction "1_1") (pintype "passive"))
      (node (ref "C12") (pin "+") (pinfunction "+_+") (pintype "passive"))
      (node (ref "C13") (pin "+") (pinfunction "+_+") (pintype "passive"))
      (node (ref "C14") (pin "+") (pinfunction "+_+") (pintype "passive"))
      (node (ref "C19") (pin "1") (pinfunction "1_1") (pintype "passive"))
      (node (ref "C20") (pin "1") (pinfunction "1_1") (pintype "passive"))
      (node (ref "C21") (pin "1") (pinfunction "1_1") (pintype "passive"))
      (node (ref "C22") (pin "1") (pinfunction "1_1") (pintype "passive"))
      (node (ref "C23") (pin "1") (pinfunction "1_1") (pintype "passive"))
      (node (ref "C24") (pin "1") (pinfunction "1_1") (pintype "passive"))
      (node (ref "C30") (pin "1") (pinfunction "1_1") (pintype "passive"))
      (node (ref "C31") (pin "1") (pinfunction "1_1") (pintype "passive"))
      (node (ref "C32") (pin "1") (pinfunction "1_1") (pintype "passive"))
      (node (ref "C33") (pin "1") (pinfunction "1_1") (pintype "passive"))
      (node (ref "C34") (pin "1") (pinfunction "1_1") (pintype "passive"))
      (node (ref "C35") (pin "1") (pinfunction "1_1") (pintype "passive"))
      (node (ref "C4") (pin "1") (pinfunction "1_1") (pintype "passive"))
      (node (ref "C41") (pin "1") (pinfunction "1_1") (pintype "passive"))
      (node (ref "C42") (pin "1") (pinfunction "1_1") (pintype "passive"))
      (node (ref "C43") (pin "1") (pinfunction "1_1") (pintype "passive"))
      (node (ref "C44") (pin "1") (pinfunction "1_1") (pintype "passive"))
      (node (ref "C45") (pin "1") (pinfunction "1_1") (pintype "passive"))
      (node (ref "C46") (pin "1") (pinfunction "1_1") (pintype "passive"))
      (node (ref "C5") (pin "1") (pinfunction "1_1") (pintype "passive"))
      (node (ref "C52") (pin "1") (pinfunction "1_1") (pintype "passive"))
      (node (ref "C53") (pin "1") (pinfunction "1_1") (pintype "passive"))
      (node (ref "C54") (pin "1") (pinfunction "1_1") (pintype "passive"))
      (node (ref "C55") (pin "1") (pinfunction "1_1") (pintype "passive"))
      (node (ref "C56") (pin "1") (pinfunction "1_1") (pintype "passive"))
      (node (ref "C57") (pin "1") (pinfunction "1_1") (pintype "passive"))
      (node (ref "C6") (pin "1") (pinfunction "1_1") (pintype "passive"))
      (node (ref "C63") (pin "1") (pinfunction "1_1") (pintype "passive"))
      (node (ref "C64") (pin "1") (pinfunction "1_1") (pintype "passive"))
      (node (ref "C65") (pin "1") (pinfunction "1_1") (pintype "passive"))
      (node (ref "C66") (pin "1") (pinfunction "1_1") (pintype "passive"))
      (node (ref "C67") (pin "1") (pinfunction "1_1") (pintype "passive"))
      (node (ref "C68") (pin "1") (pinfunction "1_1") (pintype "passive"))
      (node (ref "C7") (pin "1") (pinfunction "1_1") (pintype "passive"))
      (node (ref "C74") (pin "1") (pinfunction "1_1") (pintype "passive"))
      (node (ref "C75") (pin "1") (pinfunction "1_1") (pintype "passive"))
      (node (ref "C76") (pin "1") (pinfunction "1_1") (pintype "passive"))
      (node (ref "C77") (pin "1") (pinfunction "1_1") (pintype "passive"))
      (node (ref "C78") (pin "1") (pinfunction "1_1") (pintype "passive"))
      (node (ref "C79") (pin "1") (pinfunction "1_1") (pintype "passive"))
      (node (ref "C8") (pin "1") (pinfunction "1_1") (pintype "passive"))
      (node (ref "C9") (pin "1") (pinfunction "1_1") (pintype "passive"))
      (node (ref "IC1") (pin "1") (pinfunction "VI_1") (pintype "input"))
      (node (ref "LED1") (pin "A") (pinfunction "A_A") (pintype "passive"))
      (node (ref "R105") (pin "1") (pinfunction "1_1") (pintype "passive"))
      (node (ref "R12") (pin "1") (pinfunction "1_1") (pintype "passive"))
      (node (ref "R124") (pin "1") (pinfunction "1_1") (pintype "passive"))
      (node (ref "R154") (pin "1") (pinfunction "1_1") (pintype "passive"))
      (node (ref "R29") (pin "1") (pinfunction "1_1") (pintype "passive"))
      (node (ref "R48") (pin "1") (pinfunction "1_1") (pintype "passive"))
      (node (ref "R67") (pin "1") (pinfunction "1_1") (pintype "passive"))
      (node (ref "R86") (pin "1") (pinfunction "1_1") (pintype "passive"))
      (node (ref "U$1") (pin "PIN$10") (pinfunction "V+_PIN$10") (pintype "bidirectional"))
      (node (ref "U$1") (pin "PIN$11") (pinfunction "V+_PIN$11") (pintype "bidirectional"))
      (node (ref "U$10") (pin "PIN$10") (pinfunction "V+_PIN$10") (pintype "bidirectional"))
      (node (ref "U$10") (pin "PIN$11") (pinfunction "V+_PIN$11") (pintype "bidirectional"))
      (node (ref "U$11") (pin "PIN$10") (pinfunction "V+_PIN$10") (pintype "bidirectional"))
      (node (ref "U$11") (pin "PIN$11") (pinfunction "V+_PIN$11") (pintype "bidirectional"))
      (node (ref "U$12") (pin "PIN$10") (pinfunction "V+_PIN$10") (pintype "bidirectional"))
      (node (ref "U$12") (pin "PIN$11") (pinfunction "V+_PIN$11") (pintype "bidirectional"))
      (node (ref "U$13") (pin "PIN$10") (pinfunction "V+_PIN$10") (pintype "bidirectional"))
      (node (ref "U$13") (pin "PIN$11") (pinfunction "V+_PIN$11") (pintype "bidirectional"))
      (node (ref "U$14") (pin "PIN$10") (pinfunction "V+_PIN$10") (pintype "bidirectional"))
      (node (ref "U$14") (pin "PIN$11") (pinfunction "V+_PIN$11") (pintype "bidirectional"))
      (node (ref "U$15") (pin "PIN$10") (pinfunction "V+_PIN$10") (pintype "bidirectional"))
      (node (ref "U$15") (pin "PIN$11") (pinfunction "V+_PIN$11") (pintype "bidirectional"))
      (node (ref "U$16") (pin "PIN$10") (pinfunction "V+_PIN$10") (pintype "bidirectional"))
      (node (ref "U$16") (pin "PIN$11") (pinfunction "V+_PIN$11") (pintype "bidirectional"))
      (node (ref "U$2") (pin "PIN$10") (pinfunction "V+_PIN$10") (pintype "bidirectional"))
      (node (ref "U$2") (pin "PIN$11") (pinfunction "V+_PIN$11") (pintype "bidirectional"))
      (node (ref "U$3") (pin "PIN$10") (pinfunction "V+_PIN$10") (pintype "bidirectional"))
      (node (ref "U$3") (pin "PIN$11") (pinfunction "V+_PIN$11") (pintype "bidirectional"))
      (node (ref "U$4") (pin "PIN$10") (pinfunction "V+_PIN$10") (pintype "bidirectional"))
      (node (ref "U$4") (pin "PIN$11") (pinfunction "V+_PIN$11") (pintype "bidirectional"))
      (node (ref "U$5") (pin "PIN$10") (pinfunction "V+_PIN$10") (pintype "bidirectional"))
      (node (ref "U$5") (pin "PIN$11") (pinfunction "V+_PIN$11") (pintype "bidirectional"))
      (node (ref "U$6") (pin "PIN$10") (pinfunction "V+_PIN$10") (pintype "bidirectional"))
      (node (ref "U$6") (pin "PIN$11") (pinfunction "V+_PIN$11") (pintype "bidirectional"))
      (node (ref "U$7") (pin "PIN$10") (pinfunction "V+_PIN$10") (pintype "bidirectional"))
      (node (ref "U$7") (pin "PIN$11") (pinfunction "V+_PIN$11") (pintype "bidirectional"))
      (node (ref "U$8") (pin "PIN$10") (pinfunction "V+_PIN$10") (pintype "bidirectional"))
      (node (ref "U$8") (pin "PIN$11") (pinfunction "V+_PIN$11") (pintype "bidirectional"))
      (node (ref "U$9") (pin "PIN$10") (pinfunction "V+_PIN$10") (pintype "bidirectional"))
      (node (ref "U$9") (pin "PIN$11") (pinfunction "V+_PIN$11") (pintype "bidirectional"))
      (node (ref "U031") (pin "P$2") (pinfunction "2_P$2") (pintype "passive"))
    )
    (net (code "230") (name "unconnected-(IC4A-Y4-Pad11)") (class "Default")
      (node (ref "IC4") (pin "11") (pinfunction "Y4_11") (pintype "output"))
    )
    (net (code "231") (name "unconnected-(IC4A-Y5-Pad10)") (class "Default")
      (node (ref "IC4") (pin "10") (pinfunction "Y5_10") (pintype "output"))
    )
    (net (code "232") (name "unconnected-(IC4A-Y6-Pad9)") (class "Default")
      (node (ref "IC4") (pin "9") (pinfunction "Y6_9") (pintype "output"))
    )
    (net (code "233") (name "unconnected-(IC4A-Y7-Pad7)") (class "Default")
      (node (ref "IC4") (pin "7") (pinfunction "Y7_7") (pintype "output"))
    )
    (net (code "234") (name "unconnected-(IC6B-A1-Pad11)") (class "Default")
      (node (ref "IC6") (pin "11") (pinfunction "A1_11") (pintype "input"))
    )
    (net (code "235") (name "unconnected-(IC6B-A2-Pad13)") (class "Default")
      (node (ref "IC6") (pin "13") (pinfunction "A2_13") (pintype "input"))
    )
    (net (code "236") (name "unconnected-(IC6B-A3-Pad15)") (class "Default")
      (node (ref "IC6") (pin "15") (pinfunction "A3_15") (pintype "input"))
    )
    (net (code "237") (name "unconnected-(IC6B-Y1-Pad9)") (class "Default")
      (node (ref "IC6") (pin "9") (pinfunction "Y1_9") (pintype "tri_state"))
    )
    (net (code "238") (name "unconnected-(IC6B-Y2-Pad7)") (class "Default")
      (node (ref "IC6") (pin "7") (pinfunction "Y2_7") (pintype "tri_state"))
    )
    (net (code "239") (name "unconnected-(IC6B-Y3-Pad5)") (class "Default")
      (node (ref "IC6") (pin "5") (pinfunction "Y3_5") (pintype "tri_state"))
    )
    (net (code "240") (name "unconnected-(U001-INB1-Pad6)") (class "Default")
      (node (ref "U001") (pin "6") (pinfunction "INB1_6") (pintype "bidirectional"))
    )
    (net (code "241") (name "unconnected-(U001-INB2-Pad5)") (class "Default")
      (node (ref "U001") (pin "5") (pinfunction "INB2_5") (pintype "bidirectional"))
    )
    (net (code "242") (name "unconnected-(U001-OUTB-Pad3)") (class "Default")
      (node (ref "U001") (pin "3") (pinfunction "OUTB_3") (pintype "bidirectional"))
    )
    (net (code "243") (name "unconnected-(U2-NC-Pad7)") (class "Default")
      (node (ref "U2") (pin "7") (pinfunction "NC_7") (pintype "no_connect"))
    )
    (net (code "244") (name "unconnected-(U3-NC-Pad7)") (class "Default")
      (node (ref "U3") (pin "7") (pinfunction "NC_7") (pintype "no_connect"))
    )
    (net (code "245") (name "unconnected-(U6-NC-Pad7)") (class "Default")
      (node (ref "U6") (pin "7") (pinfunction "NC_7") (pintype "no_connect"))
    )
    (net (code "246") (name "unconnected-(U8-NC-Pad7)") (class "Default")
      (node (ref "U8") (pin "7") (pinfunction "NC_7") (pintype "no_connect"))
    )
    (net (code "247") (name "unconnected-(U9-SDO-Pad12)") (class "Default")
      (node (ref "U9") (pin "12") (pinfunction "SDO_12") (pintype "output"))
    )
    (net (code "248") (name "unconnected-(U13-NC-Pad7)") (class "Default")
      (node (ref "U13") (pin "7") (pinfunction "NC_7") (pintype "no_connect"))
    )
    (net (code "249") (name "unconnected-(U15-NC-Pad7)") (class "Default")
      (node (ref "U15") (pin "7") (pinfunction "NC_7") (pintype "no_connect"))
    )
    (net (code "250") (name "unconnected-(U17-NC-Pad7)") (class "Default")
      (node (ref "U17") (pin "7") (pinfunction "NC_7") (pintype "no_connect"))
    )
    (net (code "251") (name "unconnected-(U19-NC-Pad7)") (class "Default")
      (node (ref "U19") (pin "7") (pinfunction "NC_7") (pintype "no_connect"))
    )
    (net (code "252") (name "unconnected-(U025-AN4-Pad7)") (class "Default")
      (node (ref "U025") (pin "7") (pinfunction "AN4_7") (pintype "bidirectional"))
    )
    (net (code "253") (name "unconnected-(U025-CATH4-Pad8)") (class "Default")
      (node (ref "U025") (pin "8") (pinfunction "CATH4_8") (pintype "bidirectional"))
    )
    (net (code "254") (name "unconnected-(U025-OUT4-Pad11)") (class "Default")
      (node (ref "U025") (pin "11") (pinfunction "OUT4_11") (pintype "bidirectional"))
    )
  )
)
